# design.net
KiCad netlist of a schematic drawn in EasyEDA Pro
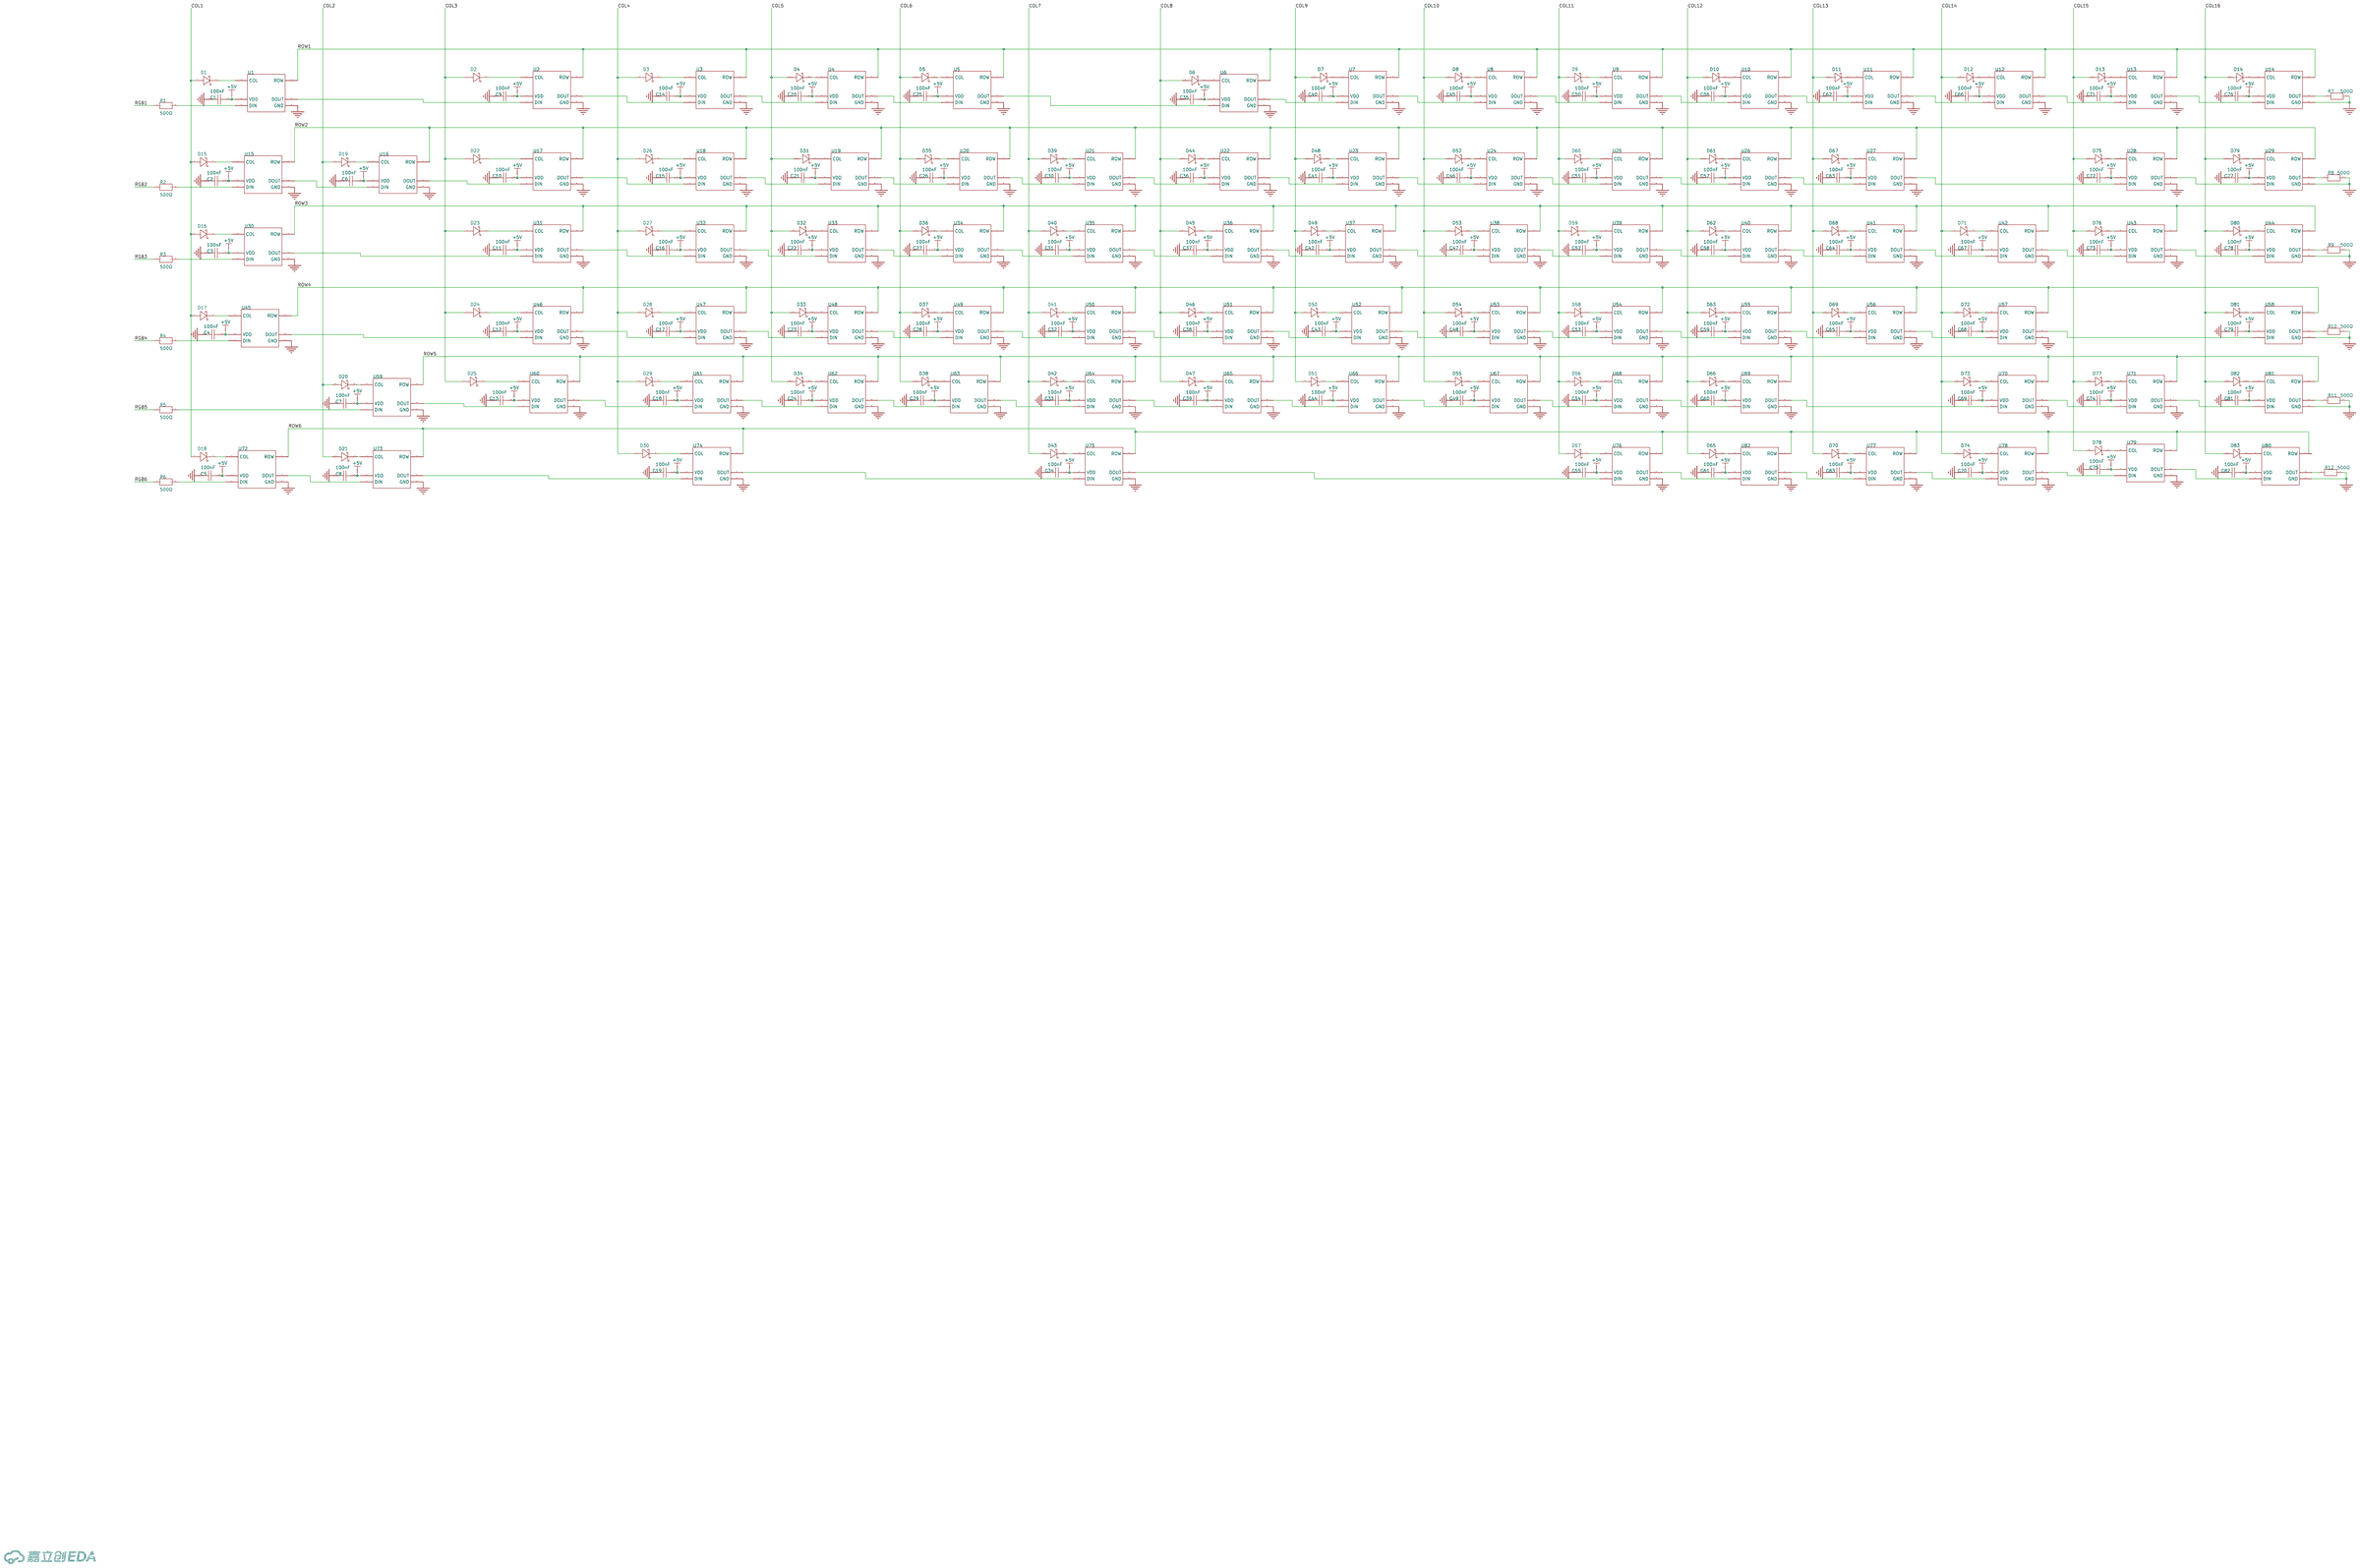
[diagram p0: 键盘按键]
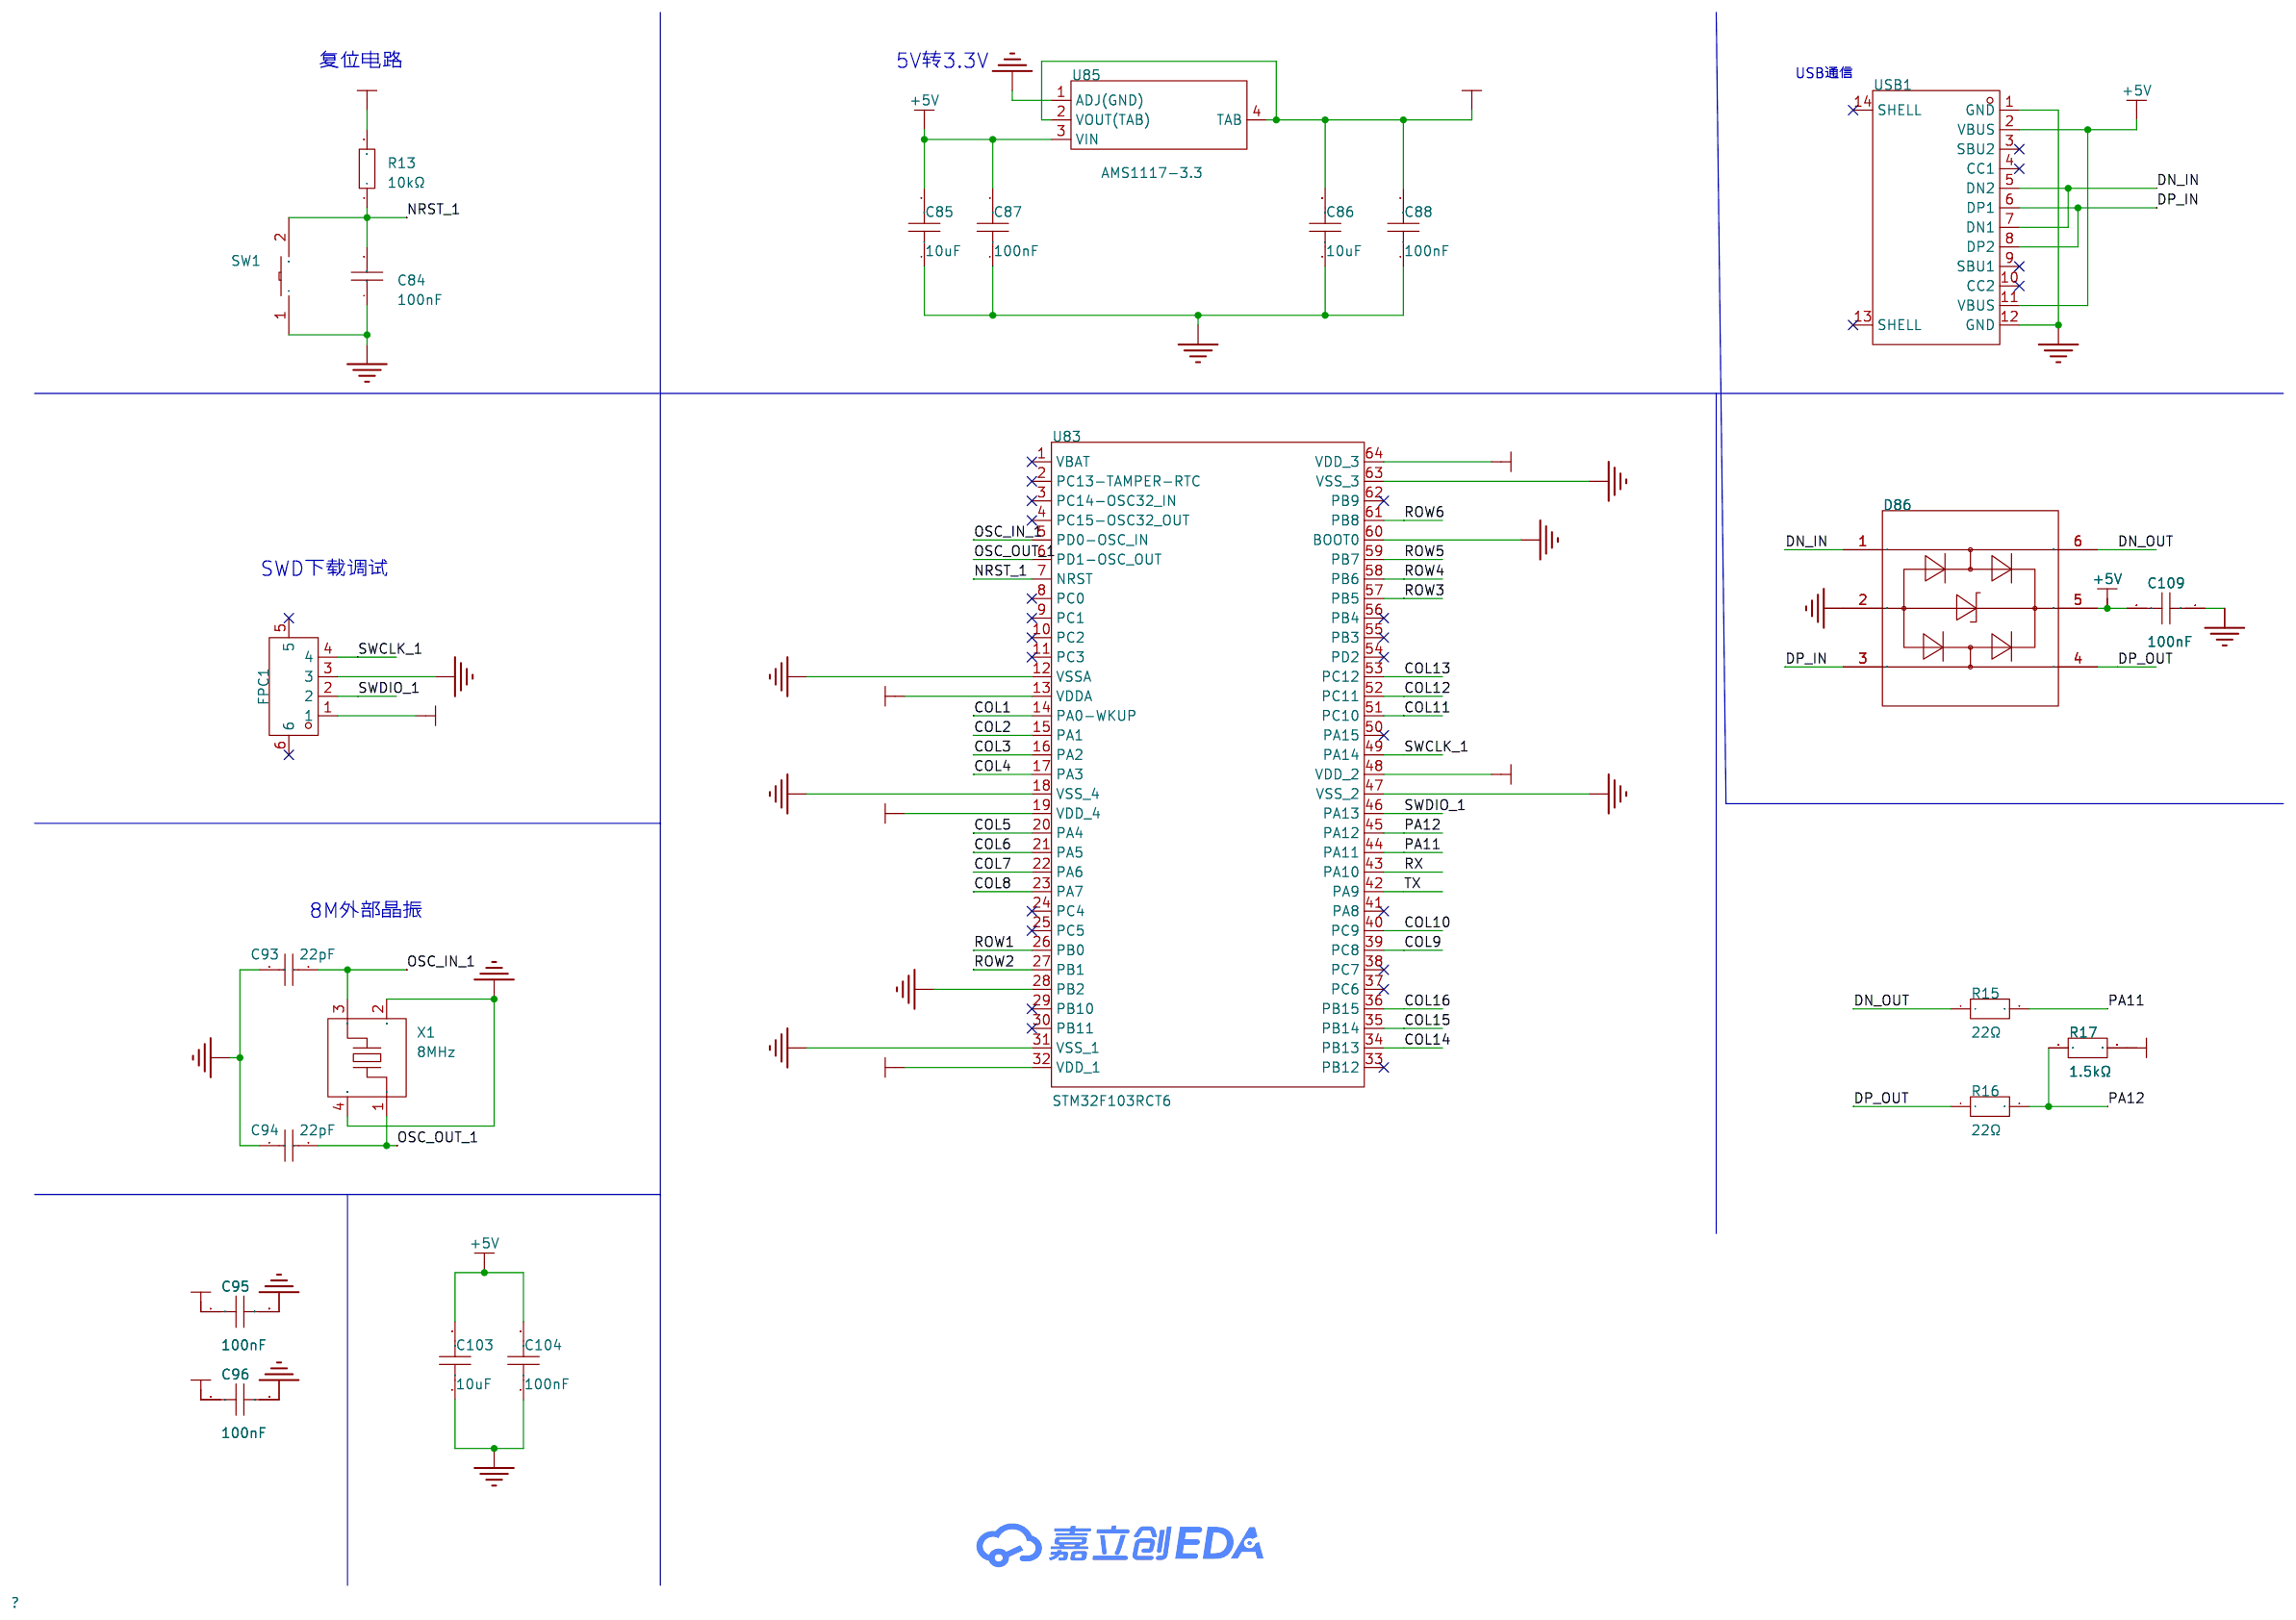
[diagram p1: 键盘主控]
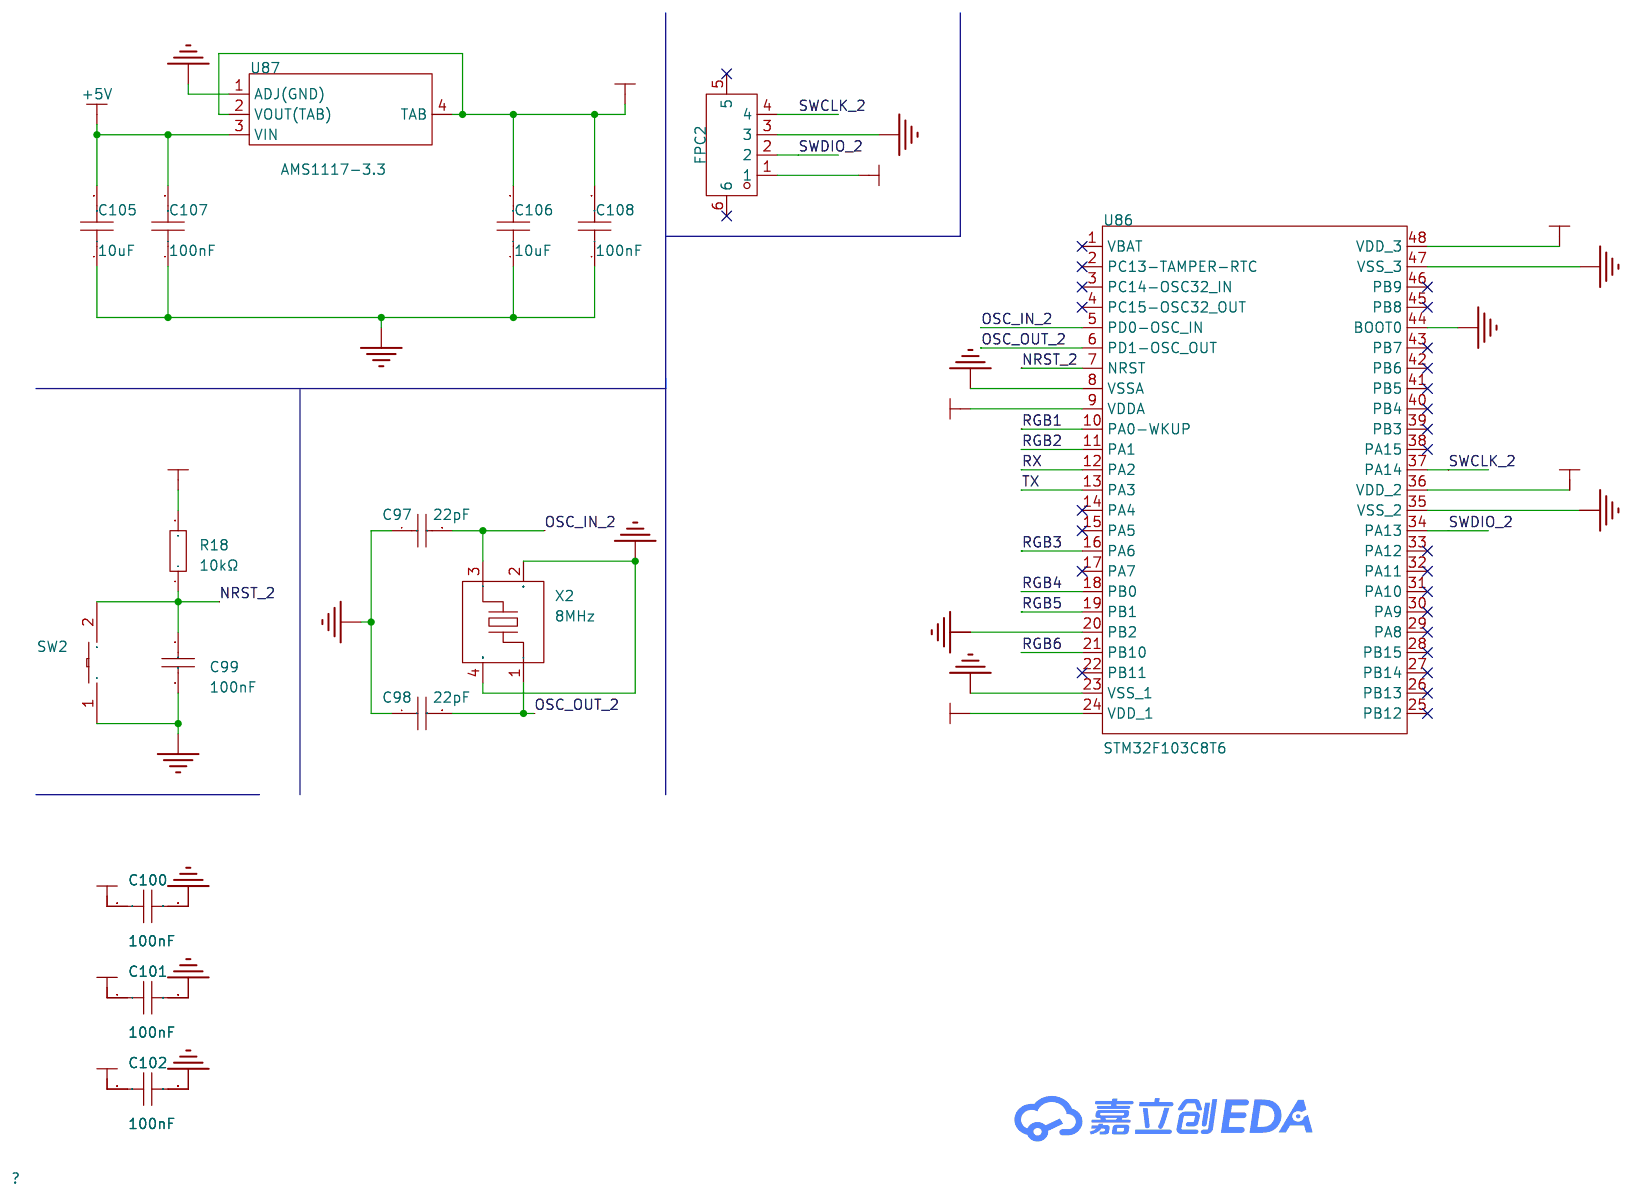
[diagram p2: 灯光主控]

(export (version "E")
  (design (tool "Eeschema 10.0.6"))
  (components
    (comp (ref "C1")
      (value "100nF")
      (footprint "easyedapro:C0805")
      (description "容值:100nF;精度:±10%;额定电压:50V;温度系数:X7R;")
      (fields
        (field (name "Manufacturer Part") "CC0805KRX7R9BB104")
        (field (name "Manufacturer") "YAGEO(国巨)")
      )
      (libsource (lib "easyedapro") (part "CC0805KRX7R9BB104"))
    )
    (comp (ref "C2")
      (value "100nF")
      (footprint "easyedapro:C0805")
      (description "容值:100nF;精度:±10%;额定电压:50V;温度系数:X7R;")
      (fields
        (field (name "Manufacturer Part") "CC0805KRX7R9BB104")
        (field (name "Manufacturer") "YAGEO(国巨)")
      )
      (libsource (lib "easyedapro") (part "CC0805KRX7R9BB104"))
    )
    (comp (ref "C3")
      (value "100nF")
      (footprint "easyedapro:C0805")
      (description "容值:100nF;精度:±10%;额定电压:50V;温度系数:X7R;")
      (fields
        (field (name "Manufacturer Part") "CC0805KRX7R9BB104")
        (field (name "Manufacturer") "YAGEO(国巨)")
      )
      (libsource (lib "easyedapro") (part "CC0805KRX7R9BB104"))
    )
    (comp (ref "C4")
      (value "100nF")
      (footprint "easyedapro:C0805")
      (description "容值:100nF;精度:±10%;额定电压:50V;温度系数:X7R;")
      (fields
        (field (name "Manufacturer Part") "CC0805KRX7R9BB104")
        (field (name "Manufacturer") "YAGEO(国巨)")
      )
      (libsource (lib "easyedapro") (part "CC0805KRX7R9BB104"))
    )
    (comp (ref "C5")
      (value "100nF")
      (footprint "easyedapro:C0805")
      (description "容值:100nF;精度:±10%;额定电压:50V;温度系数:X7R;")
      (fields
        (field (name "Manufacturer Part") "CC0805KRX7R9BB104")
        (field (name "Manufacturer") "YAGEO(国巨)")
      )
      (libsource (lib "easyedapro") (part "CC0805KRX7R9BB104"))
    )
    (comp (ref "C6")
      (value "100nF")
      (footprint "easyedapro:C0805")
      (description "容值:100nF;精度:±10%;额定电压:50V;温度系数:X7R;")
      (fields
        (field (name "Manufacturer Part") "CC0805KRX7R9BB104")
        (field (name "Manufacturer") "YAGEO(国巨)")
      )
      (libsource (lib "easyedapro") (part "CC0805KRX7R9BB104"))
    )
    (comp (ref "C7")
      (value "100nF")
      (footprint "easyedapro:C0805")
      (description "容值:100nF;精度:±10%;额定电压:50V;温度系数:X7R;")
      (fields
        (field (name "Manufacturer Part") "CC0805KRX7R9BB104")
        (field (name "Manufacturer") "YAGEO(国巨)")
      )
      (libsource (lib "easyedapro") (part "CC0805KRX7R9BB104"))
    )
    (comp (ref "C8")
      (value "100nF")
      (footprint "easyedapro:C0805")
      (description "容值:100nF;精度:±10%;额定电压:50V;温度系数:X7R;")
      (fields
        (field (name "Manufacturer Part") "CC0805KRX7R9BB104")
        (field (name "Manufacturer") "YAGEO(国巨)")
      )
      (libsource (lib "easyedapro") (part "CC0805KRX7R9BB104"))
    )
    (comp (ref "C9")
      (value "100nF")
      (footprint "easyedapro:C0805")
      (description "容值:100nF;精度:±10%;额定电压:50V;温度系数:X7R;")
      (fields
        (field (name "Manufacturer Part") "CC0805KRX7R9BB104")
        (field (name "Manufacturer") "YAGEO(国巨)")
      )
      (libsource (lib "easyedapro") (part "CC0805KRX7R9BB104"))
    )
    (comp (ref "C10")
      (value "100nF")
      (footprint "easyedapro:C0805")
      (description "容值:100nF;精度:±10%;额定电压:50V;温度系数:X7R;")
      (fields
        (field (name "Manufacturer Part") "CC0805KRX7R9BB104")
        (field (name "Manufacturer") "YAGEO(国巨)")
      )
      (libsource (lib "easyedapro") (part "CC0805KRX7R9BB104"))
    )
    (comp (ref "C11")
      (value "100nF")
      (footprint "easyedapro:C0805")
      (description "容值:100nF;精度:±10%;额定电压:50V;温度系数:X7R;")
      (fields
        (field (name "Manufacturer Part") "CC0805KRX7R9BB104")
        (field (name "Manufacturer") "YAGEO(国巨)")
      )
      (libsource (lib "easyedapro") (part "CC0805KRX7R9BB104"))
    )
    (comp (ref "C12")
      (value "100nF")
      (footprint "easyedapro:C0805")
      (description "容值:100nF;精度:±10%;额定电压:50V;温度系数:X7R;")
      (fields
        (field (name "Manufacturer Part") "CC0805KRX7R9BB104")
        (field (name "Manufacturer") "YAGEO(国巨)")
      )
      (libsource (lib "easyedapro") (part "CC0805KRX7R9BB104"))
    )
    (comp (ref "C13")
      (value "100nF")
      (footprint "easyedapro:C0805")
      (description "容值:100nF;精度:±10%;额定电压:50V;温度系数:X7R;")
      (fields
        (field (name "Manufacturer Part") "CC0805KRX7R9BB104")
        (field (name "Manufacturer") "YAGEO(国巨)")
      )
      (libsource (lib "easyedapro") (part "CC0805KRX7R9BB104"))
    )
    (comp (ref "C14")
      (value "100nF")
      (footprint "easyedapro:C0805")
      (description "容值:100nF;精度:±10%;额定电压:50V;温度系数:X7R;")
      (fields
        (field (name "Manufacturer Part") "CC0805KRX7R9BB104")
        (field (name "Manufacturer") "YAGEO(国巨)")
      )
      (libsource (lib "easyedapro") (part "CC0805KRX7R9BB104"))
    )
    (comp (ref "C15")
      (value "100nF")
      (footprint "easyedapro:C0805")
      (description "容值:100nF;精度:±10%;额定电压:50V;温度系数:X7R;")
      (fields
        (field (name "Manufacturer Part") "CC0805KRX7R9BB104")
        (field (name "Manufacturer") "YAGEO(国巨)")
      )
      (libsource (lib "easyedapro") (part "CC0805KRX7R9BB104"))
    )
    (comp (ref "C16")
      (value "100nF")
      (footprint "easyedapro:C0805")
      (description "容值:100nF;精度:±10%;额定电压:50V;温度系数:X7R;")
      (fields
        (field (name "Manufacturer Part") "CC0805KRX7R9BB104")
        (field (name "Manufacturer") "YAGEO(国巨)")
      )
      (libsource (lib "easyedapro") (part "CC0805KRX7R9BB104"))
    )
    (comp (ref "C17")
      (value "100nF")
      (footprint "easyedapro:C0805")
      (description "容值:100nF;精度:±10%;额定电压:50V;温度系数:X7R;")
      (fields
        (field (name "Manufacturer Part") "CC0805KRX7R9BB104")
        (field (name "Manufacturer") "YAGEO(国巨)")
      )
      (libsource (lib "easyedapro") (part "CC0805KRX7R9BB104"))
    )
    (comp (ref "C18")
      (value "100nF")
      (footprint "easyedapro:C0805")
      (description "容值:100nF;精度:±10%;额定电压:50V;温度系数:X7R;")
      (fields
        (field (name "Manufacturer Part") "CC0805KRX7R9BB104")
        (field (name "Manufacturer") "YAGEO(国巨)")
      )
      (libsource (lib "easyedapro") (part "CC0805KRX7R9BB104"))
    )
    (comp (ref "C19")
      (value "100nF")
      (footprint "easyedapro:C0805")
      (description "容值:100nF;精度:±10%;额定电压:50V;温度系数:X7R;")
      (fields
        (field (name "Manufacturer Part") "CC0805KRX7R9BB104")
        (field (name "Manufacturer") "YAGEO(国巨)")
      )
      (libsource (lib "easyedapro") (part "CC0805KRX7R9BB104"))
    )
    (comp (ref "C20")
      (value "100nF")
      (footprint "easyedapro:C0805")
      (description "容值:100nF;精度:±10%;额定电压:50V;温度系数:X7R;")
      (fields
        (field (name "Manufacturer Part") "CC0805KRX7R9BB104")
        (field (name "Manufacturer") "YAGEO(国巨)")
      )
      (libsource (lib "easyedapro") (part "CC0805KRX7R9BB104"))
    )
    (comp (ref "C21")
      (value "100nF")
      (footprint "easyedapro:C0805")
      (description "容值:100nF;精度:±10%;额定电压:50V;温度系数:X7R;")
      (fields
        (field (name "Manufacturer Part") "CC0805KRX7R9BB104")
        (field (name "Manufacturer") "YAGEO(国巨)")
      )
      (libsource (lib "easyedapro") (part "CC0805KRX7R9BB104"))
    )
    (comp (ref "C22")
      (value "100nF")
      (footprint "easyedapro:C0805")
      (description "容值:100nF;精度:±10%;额定电压:50V;温度系数:X7R;")
      (fields
        (field (name "Manufacturer Part") "CC0805KRX7R9BB104")
        (field (name "Manufacturer") "YAGEO(国巨)")
      )
      (libsource (lib "easyedapro") (part "CC0805KRX7R9BB104"))
    )
    (comp (ref "C23")
      (value "100nF")
      (footprint "easyedapro:C0805")
      (description "容值:100nF;精度:±10%;额定电压:50V;温度系数:X7R;")
      (fields
        (field (name "Manufacturer Part") "CC0805KRX7R9BB104")
        (field (name "Manufacturer") "YAGEO(国巨)")
      )
      (libsource (lib "easyedapro") (part "CC0805KRX7R9BB104"))
    )
    (comp (ref "C24")
      (value "100nF")
      (footprint "easyedapro:C0805")
      (description "容值:100nF;精度:±10%;额定电压:50V;温度系数:X7R;")
      (fields
        (field (name "Manufacturer Part") "CC0805KRX7R9BB104")
        (field (name "Manufacturer") "YAGEO(国巨)")
      )
      (libsource (lib "easyedapro") (part "CC0805KRX7R9BB104"))
    )
    (comp (ref "C25")
      (value "100nF")
      (footprint "easyedapro:C0805")
      (description "容值:100nF;精度:±10%;额定电压:50V;温度系数:X7R;")
      (fields
        (field (name "Manufacturer Part") "CC0805KRX7R9BB104")
        (field (name "Manufacturer") "YAGEO(国巨)")
      )
      (libsource (lib "easyedapro") (part "CC0805KRX7R9BB104"))
    )
    (comp (ref "C26")
      (value "100nF")
      (footprint "easyedapro:C0805")
      (description "容值:100nF;精度:±10%;额定电压:50V;温度系数:X7R;")
      (fields
        (field (name "Manufacturer Part") "CC0805KRX7R9BB104")
        (field (name "Manufacturer") "YAGEO(国巨)")
      )
      (libsource (lib "easyedapro") (part "CC0805KRX7R9BB104"))
    )
    (comp (ref "C27")
      (value "100nF")
      (footprint "easyedapro:C0805")
      (description "容值:100nF;精度:±10%;额定电压:50V;温度系数:X7R;")
      (fields
        (field (name "Manufacturer Part") "CC0805KRX7R9BB104")
        (field (name "Manufacturer") "YAGEO(国巨)")
      )
      (libsource (lib "easyedapro") (part "CC0805KRX7R9BB104"))
    )
    (comp (ref "C28")
      (value "100nF")
      (footprint "easyedapro:C0805")
      (description "容值:100nF;精度:±10%;额定电压:50V;温度系数:X7R;")
      (fields
        (field (name "Manufacturer Part") "CC0805KRX7R9BB104")
        (field (name "Manufacturer") "YAGEO(国巨)")
      )
      (libsource (lib "easyedapro") (part "CC0805KRX7R9BB104"))
    )
    (comp (ref "C29")
      (value "100nF")
      (footprint "easyedapro:C0805")
      (description "容值:100nF;精度:±10%;额定电压:50V;温度系数:X7R;")
      (fields
        (field (name "Manufacturer Part") "CC0805KRX7R9BB104")
        (field (name "Manufacturer") "YAGEO(国巨)")
      )
      (libsource (lib "easyedapro") (part "CC0805KRX7R9BB104"))
    )
    (comp (ref "C30")
      (value "100nF")
      (footprint "easyedapro:C0805")
      (description "容值:100nF;精度:±10%;额定电压:50V;温度系数:X7R;")
      (fields
        (field (name "Manufacturer Part") "CC0805KRX7R9BB104")
        (field (name "Manufacturer") "YAGEO(国巨)")
      )
      (libsource (lib "easyedapro") (part "CC0805KRX7R9BB104"))
    )
    (comp (ref "C31")
      (value "100nF")
      (footprint "easyedapro:C0805")
      (description "容值:100nF;精度:±10%;额定电压:50V;温度系数:X7R;")
      (fields
        (field (name "Manufacturer Part") "CC0805KRX7R9BB104")
        (field (name "Manufacturer") "YAGEO(国巨)")
      )
      (libsource (lib "easyedapro") (part "CC0805KRX7R9BB104"))
    )
    (comp (ref "C32")
      (value "100nF")
      (footprint "easyedapro:C0805")
      (description "容值:100nF;精度:±10%;额定电压:50V;温度系数:X7R;")
      (fields
        (field (name "Manufacturer Part") "CC0805KRX7R9BB104")
        (field (name "Manufacturer") "YAGEO(国巨)")
      )
      (libsource (lib "easyedapro") (part "CC0805KRX7R9BB104"))
    )
    (comp (ref "C33")
      (value "100nF")
      (footprint "easyedapro:C0805")
      (description "容值:100nF;精度:±10%;额定电压:50V;温度系数:X7R;")
      (fields
        (field (name "Manufacturer Part") "CC0805KRX7R9BB104")
        (field (name "Manufacturer") "YAGEO(国巨)")
      )
      (libsource (lib "easyedapro") (part "CC0805KRX7R9BB104"))
    )
    (comp (ref "C34")
      (value "100nF")
      (footprint "easyedapro:C0805")
      (description "容值:100nF;精度:±10%;额定电压:50V;温度系数:X7R;")
      (fields
        (field (name "Manufacturer Part") "CC0805KRX7R9BB104")
        (field (name "Manufacturer") "YAGEO(国巨)")
      )
      (libsource (lib "easyedapro") (part "CC0805KRX7R9BB104"))
    )
    (comp (ref "C35")
      (value "100nF")
      (footprint "easyedapro:C0805")
      (description "容值:100nF;精度:±10%;额定电压:50V;温度系数:X7R;")
      (fields
        (field (name "Manufacturer Part") "CC0805KRX7R9BB104")
        (field (name "Manufacturer") "YAGEO(国巨)")
      )
      (libsource (lib "easyedapro") (part "CC0805KRX7R9BB104"))
    )
    (comp (ref "C36")
      (value "100nF")
      (footprint "easyedapro:C0805")
      (description "容值:100nF;精度:±10%;额定电压:50V;温度系数:X7R;")
      (fields
        (field (name "Manufacturer Part") "CC0805KRX7R9BB104")
        (field (name "Manufacturer") "YAGEO(国巨)")
      )
      (libsource (lib "easyedapro") (part "CC0805KRX7R9BB104"))
    )
    (comp (ref "C37")
      (value "100nF")
      (footprint "easyedapro:C0805")
      (description "容值:100nF;精度:±10%;额定电压:50V;温度系数:X7R;")
      (fields
        (field (name "Manufacturer Part") "CC0805KRX7R9BB104")
        (field (name "Manufacturer") "YAGEO(国巨)")
      )
      (libsource (lib "easyedapro") (part "CC0805KRX7R9BB104"))
    )
    (comp (ref "C38")
      (value "100nF")
      (footprint "easyedapro:C0805")
      (description "容值:100nF;精度:±10%;额定电压:50V;温度系数:X7R;")
      (fields
        (field (name "Manufacturer Part") "CC0805KRX7R9BB104")
        (field (name "Manufacturer") "YAGEO(国巨)")
      )
      (libsource (lib "easyedapro") (part "CC0805KRX7R9BB104"))
    )
    (comp (ref "C39")
      (value "100nF")
      (footprint "easyedapro:C0805")
      (description "容值:100nF;精度:±10%;额定电压:50V;温度系数:X7R;")
      (fields
        (field (name "Manufacturer Part") "CC0805KRX7R9BB104")
        (field (name "Manufacturer") "YAGEO(国巨)")
      )
      (libsource (lib "easyedapro") (part "CC0805KRX7R9BB104"))
    )
    (comp (ref "C40")
      (value "100nF")
      (footprint "easyedapro:C0805")
      (description "容值:100nF;精度:±10%;额定电压:50V;温度系数:X7R;")
      (fields
        (field (name "Manufacturer Part") "CC0805KRX7R9BB104")
        (field (name "Manufacturer") "YAGEO(国巨)")
      )
      (libsource (lib "easyedapro") (part "CC0805KRX7R9BB104"))
    )
    (comp (ref "C41")
      (value "100nF")
      (footprint "easyedapro:C0805")
      (description "容值:100nF;精度:±10%;额定电压:50V;温度系数:X7R;")
      (fields
        (field (name "Manufacturer Part") "CC0805KRX7R9BB104")
        (field (name "Manufacturer") "YAGEO(国巨)")
      )
      (libsource (lib "easyedapro") (part "CC0805KRX7R9BB104"))
    )
    (comp (ref "C42")
      (value "100nF")
      (footprint "easyedapro:C0805")
      (description "容值:100nF;精度:±10%;额定电压:50V;温度系数:X7R;")
      (fields
        (field (name "Manufacturer Part") "CC0805KRX7R9BB104")
        (field (name "Manufacturer") "YAGEO(国巨)")
      )
      (libsource (lib "easyedapro") (part "CC0805KRX7R9BB104"))
    )
    (comp (ref "C43")
      (value "100nF")
      (footprint "easyedapro:C0805")
      (description "容值:100nF;精度:±10%;额定电压:50V;温度系数:X7R;")
      (fields
        (field (name "Manufacturer Part") "CC0805KRX7R9BB104")
        (field (name "Manufacturer") "YAGEO(国巨)")
      )
      (libsource (lib "easyedapro") (part "CC0805KRX7R9BB104"))
    )
    (comp (ref "C44")
      (value "100nF")
      (footprint "easyedapro:C0805")
      (description "容值:100nF;精度:±10%;额定电压:50V;温度系数:X7R;")
      (fields
        (field (name "Manufacturer Part") "CC0805KRX7R9BB104")
        (field (name "Manufacturer") "YAGEO(国巨)")
      )
      (libsource (lib "easyedapro") (part "CC0805KRX7R9BB104"))
    )
    (comp (ref "C45")
      (value "100nF")
      (footprint "easyedapro:C0805")
      (description "容值:100nF;精度:±10%;额定电压:50V;温度系数:X7R;")
      (fields
        (field (name "Manufacturer Part") "CC0805KRX7R9BB104")
        (field (name "Manufacturer") "YAGEO(国巨)")
      )
      (libsource (lib "easyedapro") (part "CC0805KRX7R9BB104"))
    )
    (comp (ref "C46")
      (value "100nF")
      (footprint "easyedapro:C0805")
      (description "容值:100nF;精度:±10%;额定电压:50V;温度系数:X7R;")
      (fields
        (field (name "Manufacturer Part") "CC0805KRX7R9BB104")
        (field (name "Manufacturer") "YAGEO(国巨)")
      )
      (libsource (lib "easyedapro") (part "CC0805KRX7R9BB104"))
    )
    (comp (ref "C47")
      (value "100nF")
      (footprint "easyedapro:C0805")
      (description "容值:100nF;精度:±10%;额定电压:50V;温度系数:X7R;")
      (fields
        (field (name "Manufacturer Part") "CC0805KRX7R9BB104")
        (field (name "Manufacturer") "YAGEO(国巨)")
      )
      (libsource (lib "easyedapro") (part "CC0805KRX7R9BB104"))
    )
    (comp (ref "C48")
      (value "100nF")
      (footprint "easyedapro:C0805")
      (description "容值:100nF;精度:±10%;额定电压:50V;温度系数:X7R;")
      (fields
        (field (name "Manufacturer Part") "CC0805KRX7R9BB104")
        (field (name "Manufacturer") "YAGEO(国巨)")
      )
      (libsource (lib "easyedapro") (part "CC0805KRX7R9BB104"))
    )
    (comp (ref "C49")
      (value "100nF")
      (footprint "easyedapro:C0805")
      (description "容值:100nF;精度:±10%;额定电压:50V;温度系数:X7R;")
      (fields
        (field (name "Manufacturer Part") "CC0805KRX7R9BB104")
        (field (name "Manufacturer") "YAGEO(国巨)")
      )
      (libsource (lib "easyedapro") (part "CC0805KRX7R9BB104"))
    )
    (comp (ref "C50")
      (value "100nF")
      (footprint "easyedapro:C0805")
      (description "容值:100nF;精度:±10%;额定电压:50V;温度系数:X7R;")
      (fields
        (field (name "Manufacturer Part") "CC0805KRX7R9BB104")
        (field (name "Manufacturer") "YAGEO(国巨)")
      )
      (libsource (lib "easyedapro") (part "CC0805KRX7R9BB104"))
    )
    (comp (ref "C51")
      (value "100nF")
      (footprint "easyedapro:C0805")
      (description "容值:100nF;精度:±10%;额定电压:50V;温度系数:X7R;")
      (fields
        (field (name "Manufacturer Part") "CC0805KRX7R9BB104")
        (field (name "Manufacturer") "YAGEO(国巨)")
      )
      (libsource (lib "easyedapro") (part "CC0805KRX7R9BB104"))
    )
    (comp (ref "C52")
      (value "100nF")
      (footprint "easyedapro:C0805")
      (description "容值:100nF;精度:±10%;额定电压:50V;温度系数:X7R;")
      (fields
        (field (name "Manufacturer Part") "CC0805KRX7R9BB104")
        (field (name "Manufacturer") "YAGEO(国巨)")
      )
      (libsource (lib "easyedapro") (part "CC0805KRX7R9BB104"))
    )
    (comp (ref "C53")
      (value "100nF")
      (footprint "easyedapro:C0805")
      (description "容值:100nF;精度:±10%;额定电压:50V;温度系数:X7R;")
      (fields
        (field (name "Manufacturer Part") "CC0805KRX7R9BB104")
        (field (name "Manufacturer") "YAGEO(国巨)")
      )
      (libsource (lib "easyedapro") (part "CC0805KRX7R9BB104"))
    )
    (comp (ref "C54")
      (value "100nF")
      (footprint "easyedapro:C0805")
      (description "容值:100nF;精度:±10%;额定电压:50V;温度系数:X7R;")
      (fields
        (field (name "Manufacturer Part") "CC0805KRX7R9BB104")
        (field (name "Manufacturer") "YAGEO(国巨)")
      )
      (libsource (lib "easyedapro") (part "CC0805KRX7R9BB104"))
    )
    (comp (ref "C55")
      (value "100nF")
      (footprint "easyedapro:C0805")
      (description "容值:100nF;精度:±10%;额定电压:50V;温度系数:X7R;")
      (fields
        (field (name "Manufacturer Part") "CC0805KRX7R9BB104")
        (field (name "Manufacturer") "YAGEO(国巨)")
      )
      (libsource (lib "easyedapro") (part "CC0805KRX7R9BB104"))
    )
    (comp (ref "C56")
      (value "100nF")
      (footprint "easyedapro:C0805")
      (description "容值:100nF;精度:±10%;额定电压:50V;温度系数:X7R;")
      (fields
        (field (name "Manufacturer Part") "CC0805KRX7R9BB104")
        (field (name "Manufacturer") "YAGEO(国巨)")
      )
      (libsource (lib "easyedapro") (part "CC0805KRX7R9BB104"))
    )
    (comp (ref "C57")
      (value "100nF")
      (footprint "easyedapro:C0805")
      (description "容值:100nF;精度:±10%;额定电压:50V;温度系数:X7R;")
      (fields
        (field (name "Manufacturer Part") "CC0805KRX7R9BB104")
        (field (name "Manufacturer") "YAGEO(国巨)")
      )
      (libsource (lib "easyedapro") (part "CC0805KRX7R9BB104"))
    )
    (comp (ref "C58")
      (value "100nF")
      (footprint "easyedapro:C0805")
      (description "容值:100nF;精度:±10%;额定电压:50V;温度系数:X7R;")
      (fields
        (field (name "Manufacturer Part") "CC0805KRX7R9BB104")
        (field (name "Manufacturer") "YAGEO(国巨)")
      )
      (libsource (lib "easyedapro") (part "CC0805KRX7R9BB104"))
    )
    (comp (ref "C59")
      (value "100nF")
      (footprint "easyedapro:C0805")
      (description "容值:100nF;精度:±10%;额定电压:50V;温度系数:X7R;")
      (fields
        (field (name "Manufacturer Part") "CC0805KRX7R9BB104")
        (field (name "Manufacturer") "YAGEO(国巨)")
      )
      (libsource (lib "easyedapro") (part "CC0805KRX7R9BB104"))
    )
    (comp (ref "C60")
      (value "100nF")
      (footprint "easyedapro:C0805")
      (description "容值:100nF;精度:±10%;额定电压:50V;温度系数:X7R;")
      (fields
        (field (name "Manufacturer Part") "CC0805KRX7R9BB104")
        (field (name "Manufacturer") "YAGEO(国巨)")
      )
      (libsource (lib "easyedapro") (part "CC0805KRX7R9BB104"))
    )
    (comp (ref "C61")
      (value "100nF")
      (footprint "easyedapro:C0805")
      (description "容值:100nF;精度:±10%;额定电压:50V;温度系数:X7R;")
      (fields
        (field (name "Manufacturer Part") "CC0805KRX7R9BB104")
        (field (name "Manufacturer") "YAGEO(国巨)")
      )
      (libsource (lib "easyedapro") (part "CC0805KRX7R9BB104"))
    )
    (comp (ref "C62")
      (value "100nF")
      (footprint "easyedapro:C0805")
      (description "容值:100nF;精度:±10%;额定电压:50V;温度系数:X7R;")
      (fields
        (field (name "Manufacturer Part") "CC0805KRX7R9BB104")
        (field (name "Manufacturer") "YAGEO(国巨)")
      )
      (libsource (lib "easyedapro") (part "CC0805KRX7R9BB104"))
    )
    (comp (ref "C63")
      (value "100nF")
      (footprint "easyedapro:C0805")
      (description "容值:100nF;精度:±10%;额定电压:50V;温度系数:X7R;")
      (fields
        (field (name "Manufacturer Part") "CC0805KRX7R9BB104")
        (field (name "Manufacturer") "YAGEO(国巨)")
      )
      (libsource (lib "easyedapro") (part "CC0805KRX7R9BB104"))
    )
    (comp (ref "C64")
      (value "100nF")
      (footprint "easyedapro:C0805")
      (description "容值:100nF;精度:±10%;额定电压:50V;温度系数:X7R;")
      (fields
        (field (name "Manufacturer Part") "CC0805KRX7R9BB104")
        (field (name "Manufacturer") "YAGEO(国巨)")
      )
      (libsource (lib "easyedapro") (part "CC0805KRX7R9BB104"))
    )
    (comp (ref "C65")
      (value "100nF")
      (footprint "easyedapro:C0805")
      (description "容值:100nF;精度:±10%;额定电压:50V;温度系数:X7R;")
      (fields
        (field (name "Manufacturer Part") "CC0805KRX7R9BB104")
        (field (name "Manufacturer") "YAGEO(国巨)")
      )
      (libsource (lib "easyedapro") (part "CC0805KRX7R9BB104"))
    )
    (comp (ref "C66")
      (value "100nF")
      (footprint "easyedapro:C0805")
      (description "容值:100nF;精度:±10%;额定电压:50V;温度系数:X7R;")
      (fields
        (field (name "Manufacturer Part") "CC0805KRX7R9BB104")
        (field (name "Manufacturer") "YAGEO(国巨)")
      )
      (libsource (lib "easyedapro") (part "CC0805KRX7R9BB104"))
    )
    (comp (ref "C67")
      (value "100nF")
      (footprint "easyedapro:C0805")
      (description "容值:100nF;精度:±10%;额定电压:50V;温度系数:X7R;")
      (fields
        (field (name "Manufacturer Part") "CC0805KRX7R9BB104")
        (field (name "Manufacturer") "YAGEO(国巨)")
      )
      (libsource (lib "easyedapro") (part "CC0805KRX7R9BB104"))
    )
    (comp (ref "C68")
      (value "100nF")
      (footprint "easyedapro:C0805")
      (description "容值:100nF;精度:±10%;额定电压:50V;温度系数:X7R;")
      (fields
        (field (name "Manufacturer Part") "CC0805KRX7R9BB104")
        (field (name "Manufacturer") "YAGEO(国巨)")
      )
      (libsource (lib "easyedapro") (part "CC0805KRX7R9BB104"))
    )
    (comp (ref "C69")
      (value "100nF")
      (footprint "easyedapro:C0805")
      (description "容值:100nF;精度:±10%;额定电压:50V;温度系数:X7R;")
      (fields
        (field (name "Manufacturer Part") "CC0805KRX7R9BB104")
        (field (name "Manufacturer") "YAGEO(国巨)")
      )
      (libsource (lib "easyedapro") (part "CC0805KRX7R9BB104"))
    )
    (comp (ref "C70")
      (value "100nF")
      (footprint "easyedapro:C0805")
      (description "容值:100nF;精度:±10%;额定电压:50V;温度系数:X7R;")
      (fields
        (field (name "Manufacturer Part") "CC0805KRX7R9BB104")
        (field (name "Manufacturer") "YAGEO(国巨)")
      )
      (libsource (lib "easyedapro") (part "CC0805KRX7R9BB104"))
    )
    (comp (ref "C71")
      (value "100nF")
      (footprint "easyedapro:C0805")
      (description "容值:100nF;精度:±10%;额定电压:50V;温度系数:X7R;")
      (fields
        (field (name "Manufacturer Part") "CC0805KRX7R9BB104")
        (field (name "Manufacturer") "YAGEO(国巨)")
      )
      (libsource (lib "easyedapro") (part "CC0805KRX7R9BB104"))
    )
    (comp (ref "C72")
      (value "100nF")
      (footprint "easyedapro:C0805")
      (description "容值:100nF;精度:±10%;额定电压:50V;温度系数:X7R;")
      (fields
        (field (name "Manufacturer Part") "CC0805KRX7R9BB104")
        (field (name "Manufacturer") "YAGEO(国巨)")
      )
      (libsource (lib "easyedapro") (part "CC0805KRX7R9BB104"))
    )
    (comp (ref "C73")
      (value "100nF")
      (footprint "easyedapro:C0805")
      (description "容值:100nF;精度:±10%;额定电压:50V;温度系数:X7R;")
      (fields
        (field (name "Manufacturer Part") "CC0805KRX7R9BB104")
        (field (name "Manufacturer") "YAGEO(国巨)")
      )
      (libsource (lib "easyedapro") (part "CC0805KRX7R9BB104"))
    )
    (comp (ref "C74")
      (value "100nF")
      (footprint "easyedapro:C0805")
      (description "容值:100nF;精度:±10%;额定电压:50V;温度系数:X7R;")
      (fields
        (field (name "Manufacturer Part") "CC0805KRX7R9BB104")
        (field (name "Manufacturer") "YAGEO(国巨)")
      )
      (libsource (lib "easyedapro") (part "CC0805KRX7R9BB104"))
    )
    (comp (ref "C75")
      (value "100nF")
      (footprint "easyedapro:C0805")
      (description "容值:100nF;精度:±10%;额定电压:50V;温度系数:X7R;")
      (fields
        (field (name "Manufacturer Part") "CC0805KRX7R9BB104")
        (field (name "Manufacturer") "YAGEO(国巨)")
      )
      (libsource (lib "easyedapro") (part "CC0805KRX7R9BB104"))
    )
    (comp (ref "C76")
      (value "100nF")
      (footprint "easyedapro:C0805")
      (description "容值:100nF;精度:±10%;额定电压:50V;温度系数:X7R;")
      (fields
        (field (name "Manufacturer Part") "CC0805KRX7R9BB104")
        (field (name "Manufacturer") "YAGEO(国巨)")
      )
      (libsource (lib "easyedapro") (part "CC0805KRX7R9BB104"))
    )
    (comp (ref "C77")
      (value "100nF")
      (footprint "easyedapro:C0805")
      (description "容值:100nF;精度:±10%;额定电压:50V;温度系数:X7R;")
      (fields
        (field (name "Manufacturer Part") "CC0805KRX7R9BB104")
        (field (name "Manufacturer") "YAGEO(国巨)")
      )
      (libsource (lib "easyedapro") (part "CC0805KRX7R9BB104"))
    )
    (comp (ref "C78")
      (value "100nF")
      (footprint "easyedapro:C0805")
      (description "容值:100nF;精度:±10%;额定电压:50V;温度系数:X7R;")
      (fields
        (field (name "Manufacturer Part") "CC0805KRX7R9BB104")
        (field (name "Manufacturer") "YAGEO(国巨)")
      )
      (libsource (lib "easyedapro") (part "CC0805KRX7R9BB104"))
    )
    (comp (ref "C79")
      (value "100nF")
      (footprint "easyedapro:C0805")
      (description "容值:100nF;精度:±10%;额定电压:50V;温度系数:X7R;")
      (fields
        (field (name "Manufacturer Part") "CC0805KRX7R9BB104")
        (field (name "Manufacturer") "YAGEO(国巨)")
      )
      (libsource (lib "easyedapro") (part "CC0805KRX7R9BB104"))
    )
    (comp (ref "C81")
      (value "100nF")
      (footprint "easyedapro:C0805")
      (description "容值:100nF;精度:±10%;额定电压:50V;温度系数:X7R;")
      (fields
        (field (name "Manufacturer Part") "CC0805KRX7R9BB104")
        (field (name "Manufacturer") "YAGEO(国巨)")
      )
      (libsource (lib "easyedapro") (part "CC0805KRX7R9BB104"))
    )
    (comp (ref "C82")
      (value "100nF")
      (footprint "easyedapro:C0805")
      (description "容值:100nF;精度:±10%;额定电压:50V;温度系数:X7R;")
      (fields
        (field (name "Manufacturer Part") "CC0805KRX7R9BB104")
        (field (name "Manufacturer") "YAGEO(国巨)")
      )
      (libsource (lib "easyedapro") (part "CC0805KRX7R9BB104"))
    )
    (comp (ref "C83")
      (value "100nF")
      (footprint "easyedapro:C0805")
      (description "容值:100nF;精度:±10%;额定电压:50V;温度系数:X7R;")
      (fields
        (field (name "Manufacturer Part") "CC0805KRX7R9BB104")
        (field (name "Manufacturer") "YAGEO(国巨)")
      )
      (libsource (lib "easyedapro") (part "CC0805KRX7R9BB104"))
    )
    (comp (ref "D1")
      (value "1N4148W")
      (footprint "easyedapro:SOD-123_L2.7-W1.6-LS3.7-FD")
      (description "二极管配置:独立式;正向压降(Vf):1.25V@150mA;直流反向耐压(Vr):100V;整流电流:150mA;反向恢复时间(Trr):4ns;")
      (fields (field (name "Manufacturer") "R+O(宏嘉诚)"))
      (libsource (lib "easyedapro") (part "1N4148W_C7420318"))
    )
    (comp (ref "D2")
      (value "1N4148W")
      (footprint "easyedapro:SOD-123_L2.7-W1.6-LS3.7-FD")
      (description "二极管配置:独立式;正向压降(Vf):1.25V@150mA;直流反向耐压(Vr):100V;整流电流:150mA;反向恢复时间(Trr):4ns;")
      (fields (field (name "Manufacturer") "R+O(宏嘉诚)"))
      (libsource (lib "easyedapro") (part "1N4148W_C7420318"))
    )
    (comp (ref "D3")
      (value "1N4148W")
      (footprint "easyedapro:SOD-123_L2.7-W1.6-LS3.7-FD")
      (description "二极管配置:独立式;正向压降(Vf):1.25V@150mA;直流反向耐压(Vr):100V;整流电流:150mA;反向恢复时间(Trr):4ns;")
      (fields (field (name "Manufacturer") "R+O(宏嘉诚)"))
      (libsource (lib "easyedapro") (part "1N4148W_C7420318"))
    )
    (comp (ref "D4")
      (value "1N4148W")
      (footprint "easyedapro:SOD-123_L2.7-W1.6-LS3.7-FD")
      (description "二极管配置:独立式;正向压降(Vf):1.25V@150mA;直流反向耐压(Vr):100V;整流电流:150mA;反向恢复时间(Trr):4ns;")
      (fields (field (name "Manufacturer") "R+O(宏嘉诚)"))
      (libsource (lib "easyedapro") (part "1N4148W_C7420318"))
    )
    (comp (ref "D5")
      (value "1N4148W")
      (footprint "easyedapro:SOD-123_L2.7-W1.6-LS3.7-FD")
      (description "二极管配置:独立式;正向压降(Vf):1.25V@150mA;直流反向耐压(Vr):100V;整流电流:150mA;反向恢复时间(Trr):4ns;")
      (fields (field (name "Manufacturer") "R+O(宏嘉诚)"))
      (libsource (lib "easyedapro") (part "1N4148W_C7420318"))
    )
    (comp (ref "D6")
      (value "1N4148W")
      (footprint "easyedapro:SOD-123_L2.7-W1.6-LS3.7-FD")
      (description "二极管配置:独立式;正向压降(Vf):1.25V@150mA;直流反向耐压(Vr):100V;整流电流:150mA;反向恢复时间(Trr):4ns;")
      (fields (field (name "Manufacturer") "R+O(宏嘉诚)"))
      (libsource (lib "easyedapro") (part "1N4148W_C7420318"))
    )
    (comp (ref "D7")
      (value "1N4148W")
      (footprint "easyedapro:SOD-123_L2.7-W1.6-LS3.7-FD")
      (description "二极管配置:独立式;正向压降(Vf):1.25V@150mA;直流反向耐压(Vr):100V;整流电流:150mA;反向恢复时间(Trr):4ns;")
      (fields (field (name "Manufacturer") "R+O(宏嘉诚)"))
      (libsource (lib "easyedapro") (part "1N4148W_C7420318"))
    )
    (comp (ref "D8")
      (value "1N4148W")
      (footprint "easyedapro:SOD-123_L2.7-W1.6-LS3.7-FD")
      (description "二极管配置:独立式;正向压降(Vf):1.25V@150mA;直流反向耐压(Vr):100V;整流电流:150mA;反向恢复时间(Trr):4ns;")
      (fields (field (name "Manufacturer") "R+O(宏嘉诚)"))
      (libsource (lib "easyedapro") (part "1N4148W_C7420318"))
    )
    (comp (ref "D9")
      (value "1N4148W")
      (footprint "easyedapro:SOD-123_L2.7-W1.6-LS3.7-FD")
      (description "二极管配置:独立式;正向压降(Vf):1.25V@150mA;直流反向耐压(Vr):100V;整流电流:150mA;反向恢复时间(Trr):4ns;")
      (fields (field (name "Manufacturer") "R+O(宏嘉诚)"))
      (libsource (lib "easyedapro") (part "1N4148W_C7420318"))
    )
    (comp (ref "D10")
      (value "1N4148W")
      (footprint "easyedapro:SOD-123_L2.7-W1.6-LS3.7-FD")
      (description "二极管配置:独立式;正向压降(Vf):1.25V@150mA;直流反向耐压(Vr):100V;整流电流:150mA;反向恢复时间(Trr):4ns;")
      (fields (field (name "Manufacturer") "R+O(宏嘉诚)"))
      (libsource (lib "easyedapro") (part "1N4148W_C7420318"))
    )
    (comp (ref "D11")
      (value "1N4148W")
      (footprint "easyedapro:SOD-123_L2.7-W1.6-LS3.7-FD")
      (description "二极管配置:独立式;正向压降(Vf):1.25V@150mA;直流反向耐压(Vr):100V;整流电流:150mA;反向恢复时间(Trr):4ns;")
      (fields (field (name "Manufacturer") "R+O(宏嘉诚)"))
      (libsource (lib "easyedapro") (part "1N4148W_C7420318"))
    )
    (comp (ref "D12")
      (value "1N4148W")
      (footprint "easyedapro:SOD-123_L2.7-W1.6-LS3.7-FD")
      (description "二极管配置:独立式;正向压降(Vf):1.25V@150mA;直流反向耐压(Vr):100V;整流电流:150mA;反向恢复时间(Trr):4ns;")
      (fields (field (name "Manufacturer") "R+O(宏嘉诚)"))
      (libsource (lib "easyedapro") (part "1N4148W_C7420318"))
    )
    (comp (ref "D13")
      (value "1N4148W")
      (footprint "easyedapro:SOD-123_L2.7-W1.6-LS3.7-FD")
      (description "二极管配置:独立式;正向压降(Vf):1.25V@150mA;直流反向耐压(Vr):100V;整流电流:150mA;反向恢复时间(Trr):4ns;")
      (fields (field (name "Manufacturer") "R+O(宏嘉诚)"))
      (libsource (lib "easyedapro") (part "1N4148W_C7420318"))
    )
    (comp (ref "D14")
      (value "1N4148W")
      (footprint "easyedapro:SOD-123_L2.7-W1.6-LS3.7-FD")
      (description "二极管配置:独立式;正向压降(Vf):1.25V@150mA;直流反向耐压(Vr):100V;整流电流:150mA;反向恢复时间(Trr):4ns;")
      (fields (field (name "Manufacturer") "R+O(宏嘉诚)"))
      (libsource (lib "easyedapro") (part "1N4148W_C7420318"))
    )
    (comp (ref "D15")
      (value "1N4148W")
      (footprint "easyedapro:SOD-123_L2.7-W1.6-LS3.7-FD")
      (description "二极管配置:独立式;正向压降(Vf):1.25V@150mA;直流反向耐压(Vr):100V;整流电流:150mA;反向恢复时间(Trr):4ns;")
      (fields (field (name "Manufacturer") "R+O(宏嘉诚)"))
      (libsource (lib "easyedapro") (part "1N4148W_C7420318"))
    )
    (comp (ref "D16")
      (value "1N4148W")
      (footprint "easyedapro:SOD-123_L2.7-W1.6-LS3.7-FD")
      (description "二极管配置:独立式;正向压降(Vf):1.25V@150mA;直流反向耐压(Vr):100V;整流电流:150mA;反向恢复时间(Trr):4ns;")
      (fields (field (name "Manufacturer") "R+O(宏嘉诚)"))
      (libsource (lib "easyedapro") (part "1N4148W_C7420318"))
    )
    (comp (ref "D17")
      (value "1N4148W")
      (footprint "easyedapro:SOD-123_L2.7-W1.6-LS3.7-FD")
      (description "二极管配置:独立式;正向压降(Vf):1.25V@150mA;直流反向耐压(Vr):100V;整流电流:150mA;反向恢复时间(Trr):4ns;")
      (fields (field (name "Manufacturer") "R+O(宏嘉诚)"))
      (libsource (lib "easyedapro") (part "1N4148W_C7420318"))
    )
    (comp (ref "D18")
      (value "1N4148W")
      (footprint "easyedapro:SOD-123_L2.7-W1.6-LS3.7-FD")
      (description "二极管配置:独立式;正向压降(Vf):1.25V@150mA;直流反向耐压(Vr):100V;整流电流:150mA;反向恢复时间(Trr):4ns;")
      (fields (field (name "Manufacturer") "R+O(宏嘉诚)"))
      (libsource (lib "easyedapro") (part "1N4148W_C7420318"))
    )
    (comp (ref "D19")
      (value "1N4148W")
      (footprint "easyedapro:SOD-123_L2.7-W1.6-LS3.7-FD")
      (description "二极管配置:独立式;正向压降(Vf):1.25V@150mA;直流反向耐压(Vr):100V;整流电流:150mA;反向恢复时间(Trr):4ns;")
      (fields (field (name "Manufacturer") "R+O(宏嘉诚)"))
      (libsource (lib "easyedapro") (part "1N4148W_C7420318"))
    )
    (comp (ref "D20")
      (value "1N4148W")
      (footprint "easyedapro:SOD-123_L2.7-W1.6-LS3.7-FD")
      (description "二极管配置:独立式;正向压降(Vf):1.25V@150mA;直流反向耐压(Vr):100V;整流电流:150mA;反向恢复时间(Trr):4ns;")
      (fields (field (name "Manufacturer") "R+O(宏嘉诚)"))
      (libsource (lib "easyedapro") (part "1N4148W_C7420318"))
    )
    (comp (ref "D21")
      (value "1N4148W")
      (footprint "easyedapro:SOD-123_L2.7-W1.6-LS3.7-FD")
      (description "二极管配置:独立式;正向压降(Vf):1.25V@150mA;直流反向耐压(Vr):100V;整流电流:150mA;反向恢复时间(Trr):4ns;")
      (fields (field (name "Manufacturer") "R+O(宏嘉诚)"))
      (libsource (lib "easyedapro") (part "1N4148W_C7420318"))
    )
    (comp (ref "D22")
      (value "1N4148W")
      (footprint "easyedapro:SOD-123_L2.7-W1.6-LS3.7-FD")
      (description "二极管配置:独立式;正向压降(Vf):1.25V@150mA;直流反向耐压(Vr):100V;整流电流:150mA;反向恢复时间(Trr):4ns;")
      (fields (field (name "Manufacturer") "R+O(宏嘉诚)"))
      (libsource (lib "easyedapro") (part "1N4148W_C7420318"))
    )
    (comp (ref "D23")
      (value "1N4148W")
      (footprint "easyedapro:SOD-123_L2.7-W1.6-LS3.7-FD")
      (description "二极管配置:独立式;正向压降(Vf):1.25V@150mA;直流反向耐压(Vr):100V;整流电流:150mA;反向恢复时间(Trr):4ns;")
      (fields (field (name "Manufacturer") "R+O(宏嘉诚)"))
      (libsource (lib "easyedapro") (part "1N4148W_C7420318"))
    )
    (comp (ref "D24")
      (value "1N4148W")
      (footprint "easyedapro:SOD-123_L2.7-W1.6-LS3.7-FD")
      (description "二极管配置:独立式;正向压降(Vf):1.25V@150mA;直流反向耐压(Vr):100V;整流电流:150mA;反向恢复时间(Trr):4ns;")
      (fields (field (name "Manufacturer") "R+O(宏嘉诚)"))
      (libsource (lib "easyedapro") (part "1N4148W_C7420318"))
    )
    (comp (ref "D25")
      (value "1N4148W")
      (footprint "easyedapro:SOD-123_L2.7-W1.6-LS3.7-FD")
      (description "二极管配置:独立式;正向压降(Vf):1.25V@150mA;直流反向耐压(Vr):100V;整流电流:150mA;反向恢复时间(Trr):4ns;")
      (fields (field (name "Manufacturer") "R+O(宏嘉诚)"))
      (libsource (lib "easyedapro") (part "1N4148W_C7420318"))
    )
    (comp (ref "D26")
      (value "1N4148W")
      (footprint "easyedapro:SOD-123_L2.7-W1.6-LS3.7-FD")
      (description "二极管配置:独立式;正向压降(Vf):1.25V@150mA;直流反向耐压(Vr):100V;整流电流:150mA;反向恢复时间(Trr):4ns;")
      (fields (field (name "Manufacturer") "R+O(宏嘉诚)"))
      (libsource (lib "easyedapro") (part "1N4148W_C7420318"))
    )
    (comp (ref "D27")
      (value "1N4148W")
      (footprint "easyedapro:SOD-123_L2.7-W1.6-LS3.7-FD")
      (description "二极管配置:独立式;正向压降(Vf):1.25V@150mA;直流反向耐压(Vr):100V;整流电流:150mA;反向恢复时间(Trr):4ns;")
      (fields (field (name "Manufacturer") "R+O(宏嘉诚)"))
      (libsource (lib "easyedapro") (part "1N4148W_C7420318"))
    )
    (comp (ref "D28")
      (value "1N4148W")
      (footprint "easyedapro:SOD-123_L2.7-W1.6-LS3.7-FD")
      (description "二极管配置:独立式;正向压降(Vf):1.25V@150mA;直流反向耐压(Vr):100V;整流电流:150mA;反向恢复时间(Trr):4ns;")
      (fields (field (name "Manufacturer") "R+O(宏嘉诚)"))
      (libsource (lib "easyedapro") (part "1N4148W_C7420318"))
    )
    (comp (ref "D29")
      (value "1N4148W")
      (footprint "easyedapro:SOD-123_L2.7-W1.6-LS3.7-FD")
      (description "二极管配置:独立式;正向压降(Vf):1.25V@150mA;直流反向耐压(Vr):100V;整流电流:150mA;反向恢复时间(Trr):4ns;")
      (fields (field (name "Manufacturer") "R+O(宏嘉诚)"))
      (libsource (lib "easyedapro") (part "1N4148W_C7420318"))
    )
    (comp (ref "D30")
      (value "1N4148W")
      (footprint "easyedapro:SOD-123_L2.7-W1.6-LS3.7-FD")
      (description "二极管配置:独立式;正向压降(Vf):1.25V@150mA;直流反向耐压(Vr):100V;整流电流:150mA;反向恢复时间(Trr):4ns;")
      (fields (field (name "Manufacturer") "R+O(宏嘉诚)"))
      (libsource (lib "easyedapro") (part "1N4148W_C7420318"))
    )
    (comp (ref "D31")
      (value "1N4148W")
      (footprint "easyedapro:SOD-123_L2.7-W1.6-LS3.7-FD")
      (description "二极管配置:独立式;正向压降(Vf):1.25V@150mA;直流反向耐压(Vr):100V;整流电流:150mA;反向恢复时间(Trr):4ns;")
      (fields (field (name "Manufacturer") "R+O(宏嘉诚)"))
      (libsource (lib "easyedapro") (part "1N4148W_C7420318"))
    )
    (comp (ref "D32")
      (value "1N4148W")
      (footprint "easyedapro:SOD-123_L2.7-W1.6-LS3.7-FD")
      (description "二极管配置:独立式;正向压降(Vf):1.25V@150mA;直流反向耐压(Vr):100V;整流电流:150mA;反向恢复时间(Trr):4ns;")
      (fields (field (name "Manufacturer") "R+O(宏嘉诚)"))
      (libsource (lib "easyedapro") (part "1N4148W_C7420318"))
    )
    (comp (ref "D33")
      (value "1N4148W")
      (footprint "easyedapro:SOD-123_L2.7-W1.6-LS3.7-FD")
      (description "二极管配置:独立式;正向压降(Vf):1.25V@150mA;直流反向耐压(Vr):100V;整流电流:150mA;反向恢复时间(Trr):4ns;")
      (fields (field (name "Manufacturer") "R+O(宏嘉诚)"))
      (libsource (lib "easyedapro") (part "1N4148W_C7420318"))
    )
    (comp (ref "D34")
      (value "1N4148W")
      (footprint "easyedapro:SOD-123_L2.7-W1.6-LS3.7-FD")
      (description "二极管配置:独立式;正向压降(Vf):1.25V@150mA;直流反向耐压(Vr):100V;整流电流:150mA;反向恢复时间(Trr):4ns;")
      (fields (field (name "Manufacturer") "R+O(宏嘉诚)"))
      (libsource (lib "easyedapro") (part "1N4148W_C7420318"))
    )
    (comp (ref "D35")
      (value "1N4148W")
      (footprint "easyedapro:SOD-123_L2.7-W1.6-LS3.7-FD")
      (description "二极管配置:独立式;正向压降(Vf):1.25V@150mA;直流反向耐压(Vr):100V;整流电流:150mA;反向恢复时间(Trr):4ns;")
      (fields (field (name "Manufacturer") "R+O(宏嘉诚)"))
      (libsource (lib "easyedapro") (part "1N4148W_C7420318"))
    )
    (comp (ref "D36")
      (value "1N4148W")
      (footprint "easyedapro:SOD-123_L2.7-W1.6-LS3.7-FD")
      (description "二极管配置:独立式;正向压降(Vf):1.25V@150mA;直流反向耐压(Vr):100V;整流电流:150mA;反向恢复时间(Trr):4ns;")
      (fields (field (name "Manufacturer") "R+O(宏嘉诚)"))
      (libsource (lib "easyedapro") (part "1N4148W_C7420318"))
    )
    (comp (ref "D37")
      (value "1N4148W")
      (footprint "easyedapro:SOD-123_L2.7-W1.6-LS3.7-FD")
      (description "二极管配置:独立式;正向压降(Vf):1.25V@150mA;直流反向耐压(Vr):100V;整流电流:150mA;反向恢复时间(Trr):4ns;")
      (fields (field (name "Manufacturer") "R+O(宏嘉诚)"))
      (libsource (lib "easyedapro") (part "1N4148W_C7420318"))
    )
    (comp (ref "D38")
      (value "1N4148W")
      (footprint "easyedapro:SOD-123_L2.7-W1.6-LS3.7-FD")
      (description "二极管配置:独立式;正向压降(Vf):1.25V@150mA;直流反向耐压(Vr):100V;整流电流:150mA;反向恢复时间(Trr):4ns;")
      (fields (field (name "Manufacturer") "R+O(宏嘉诚)"))
      (libsource (lib "easyedapro") (part "1N4148W_C7420318"))
    )
    (comp (ref "D39")
      (value "1N4148W")
      (footprint "easyedapro:SOD-123_L2.7-W1.6-LS3.7-FD")
      (description "二极管配置:独立式;正向压降(Vf):1.25V@150mA;直流反向耐压(Vr):100V;整流电流:150mA;反向恢复时间(Trr):4ns;")
      (fields (field (name "Manufacturer") "R+O(宏嘉诚)"))
      (libsource (lib "easyedapro") (part "1N4148W_C7420318"))
    )
    (comp (ref "D40")
      (value "1N4148W")
      (footprint "easyedapro:SOD-123_L2.7-W1.6-LS3.7-FD")
      (description "二极管配置:独立式;正向压降(Vf):1.25V@150mA;直流反向耐压(Vr):100V;整流电流:150mA;反向恢复时间(Trr):4ns;")
      (fields (field (name "Manufacturer") "R+O(宏嘉诚)"))
      (libsource (lib "easyedapro") (part "1N4148W_C7420318"))
    )
    (comp (ref "D41")
      (value "1N4148W")
      (footprint "easyedapro:SOD-123_L2.7-W1.6-LS3.7-FD")
      (description "二极管配置:独立式;正向压降(Vf):1.25V@150mA;直流反向耐压(Vr):100V;整流电流:150mA;反向恢复时间(Trr):4ns;")
      (fields (field (name "Manufacturer") "R+O(宏嘉诚)"))
      (libsource (lib "easyedapro") (part "1N4148W_C7420318"))
    )
    (comp (ref "D42")
      (value "1N4148W")
      (footprint "easyedapro:SOD-123_L2.7-W1.6-LS3.7-FD")
      (description "二极管配置:独立式;正向压降(Vf):1.25V@150mA;直流反向耐压(Vr):100V;整流电流:150mA;反向恢复时间(Trr):4ns;")
      (fields (field (name "Manufacturer") "R+O(宏嘉诚)"))
      (libsource (lib "easyedapro") (part "1N4148W_C7420318"))
    )
    (comp (ref "D43")
      (value "1N4148W")
      (footprint "easyedapro:SOD-123_L2.7-W1.6-LS3.7-FD")
      (description "二极管配置:独立式;正向压降(Vf):1.25V@150mA;直流反向耐压(Vr):100V;整流电流:150mA;反向恢复时间(Trr):4ns;")
      (fields (field (name "Manufacturer") "R+O(宏嘉诚)"))
      (libsource (lib "easyedapro") (part "1N4148W_C7420318"))
    )
    (comp (ref "D44")
      (value "1N4148W")
      (footprint "easyedapro:SOD-123_L2.7-W1.6-LS3.7-FD")
      (description "二极管配置:独立式;正向压降(Vf):1.25V@150mA;直流反向耐压(Vr):100V;整流电流:150mA;反向恢复时间(Trr):4ns;")
      (fields (field (name "Manufacturer") "R+O(宏嘉诚)"))
      (libsource (lib "easyedapro") (part "1N4148W_C7420318"))
    )
    (comp (ref "D45")
      (value "1N4148W")
      (footprint "easyedapro:SOD-123_L2.7-W1.6-LS3.7-FD")
      (description "二极管配置:独立式;正向压降(Vf):1.25V@150mA;直流反向耐压(Vr):100V;整流电流:150mA;反向恢复时间(Trr):4ns;")
      (fields (field (name "Manufacturer") "R+O(宏嘉诚)"))
      (libsource (lib "easyedapro") (part "1N4148W_C7420318"))
    )
    (comp (ref "D46")
      (value "1N4148W")
      (footprint "easyedapro:SOD-123_L2.7-W1.6-LS3.7-FD")
      (description "二极管配置:独立式;正向压降(Vf):1.25V@150mA;直流反向耐压(Vr):100V;整流电流:150mA;反向恢复时间(Trr):4ns;")
      (fields (field (name "Manufacturer") "R+O(宏嘉诚)"))
      (libsource (lib "easyedapro") (part "1N4148W_C7420318"))
    )
    (comp (ref "D47")
      (value "1N4148W")
      (footprint "easyedapro:SOD-123_L2.7-W1.6-LS3.7-FD")
      (description "二极管配置:独立式;正向压降(Vf):1.25V@150mA;直流反向耐压(Vr):100V;整流电流:150mA;反向恢复时间(Trr):4ns;")
      (fields (field (name "Manufacturer") "R+O(宏嘉诚)"))
      (libsource (lib "easyedapro") (part "1N4148W_C7420318"))
    )
    (comp (ref "D48")
      (value "1N4148W")
      (footprint "easyedapro:SOD-123_L2.7-W1.6-LS3.7-FD")
      (description "二极管配置:独立式;正向压降(Vf):1.25V@150mA;直流反向耐压(Vr):100V;整流电流:150mA;反向恢复时间(Trr):4ns;")
      (fields (field (name "Manufacturer") "R+O(宏嘉诚)"))
      (libsource (lib "easyedapro") (part "1N4148W_C7420318"))
    )
    (comp (ref "D49")
      (value "1N4148W")
      (footprint "easyedapro:SOD-123_L2.7-W1.6-LS3.7-FD")
      (description "二极管配置:独立式;正向压降(Vf):1.25V@150mA;直流反向耐压(Vr):100V;整流电流:150mA;反向恢复时间(Trr):4ns;")
      (fields (field (name "Manufacturer") "R+O(宏嘉诚)"))
      (libsource (lib "easyedapro") (part "1N4148W_C7420318"))
    )
    (comp (ref "D50")
      (value "1N4148W")
      (footprint "easyedapro:SOD-123_L2.7-W1.6-LS3.7-FD")
      (description "二极管配置:独立式;正向压降(Vf):1.25V@150mA;直流反向耐压(Vr):100V;整流电流:150mA;反向恢复时间(Trr):4ns;")
      (fields (field (name "Manufacturer") "R+O(宏嘉诚)"))
      (libsource (lib "easyedapro") (part "1N4148W_C7420318"))
    )
    (comp (ref "D51")
      (value "1N4148W")
      (footprint "easyedapro:SOD-123_L2.7-W1.6-LS3.7-FD")
      (description "二极管配置:独立式;正向压降(Vf):1.25V@150mA;直流反向耐压(Vr):100V;整流电流:150mA;反向恢复时间(Trr):4ns;")
      (fields (field (name "Manufacturer") "R+O(宏嘉诚)"))
      (libsource (lib "easyedapro") (part "1N4148W_C7420318"))
    )
    (comp (ref "D52")
      (value "1N4148W")
      (footprint "easyedapro:SOD-123_L2.7-W1.6-LS3.7-FD")
      (description "二极管配置:独立式;正向压降(Vf):1.25V@150mA;直流反向耐压(Vr):100V;整流电流:150mA;反向恢复时间(Trr):4ns;")
      (fields (field (name "Manufacturer") "R+O(宏嘉诚)"))
      (libsource (lib "easyedapro") (part "1N4148W_C7420318"))
    )
    (comp (ref "D53")
      (value "1N4148W")
      (footprint "easyedapro:SOD-123_L2.7-W1.6-LS3.7-FD")
      (description "二极管配置:独立式;正向压降(Vf):1.25V@150mA;直流反向耐压(Vr):100V;整流电流:150mA;反向恢复时间(Trr):4ns;")
      (fields (field (name "Manufacturer") "R+O(宏嘉诚)"))
      (libsource (lib "easyedapro") (part "1N4148W_C7420318"))
    )
    (comp (ref "D54")
      (value "1N4148W")
      (footprint "easyedapro:SOD-123_L2.7-W1.6-LS3.7-FD")
      (description "二极管配置:独立式;正向压降(Vf):1.25V@150mA;直流反向耐压(Vr):100V;整流电流:150mA;反向恢复时间(Trr):4ns;")
      (fields (field (name "Manufacturer") "R+O(宏嘉诚)"))
      (libsource (lib "easyedapro") (part "1N4148W_C7420318"))
    )
    (comp (ref "D55")
      (value "1N4148W")
      (footprint "easyedapro:SOD-123_L2.7-W1.6-LS3.7-FD")
      (description "二极管配置:独立式;正向压降(Vf):1.25V@150mA;直流反向耐压(Vr):100V;整流电流:150mA;反向恢复时间(Trr):4ns;")
      (fields (field (name "Manufacturer") "R+O(宏嘉诚)"))
      (libsource (lib "easyedapro") (part "1N4148W_C7420318"))
    )
    (comp (ref "D56")
      (value "1N4148W")
      (footprint "easyedapro:SOD-123_L2.7-W1.6-LS3.7-FD")
      (description "二极管配置:独立式;正向压降(Vf):1.25V@150mA;直流反向耐压(Vr):100V;整流电流:150mA;反向恢复时间(Trr):4ns;")
      (fields (field (name "Manufacturer") "R+O(宏嘉诚)"))
      (libsource (lib "easyedapro") (part "1N4148W_C7420318"))
    )
    (comp (ref "D57")
      (value "1N4148W")
      (footprint "easyedapro:SOD-123_L2.7-W1.6-LS3.7-FD")
      (description "二极管配置:独立式;正向压降(Vf):1.25V@150mA;直流反向耐压(Vr):100V;整流电流:150mA;反向恢复时间(Trr):4ns;")
      (fields (field (name "Manufacturer") "R+O(宏嘉诚)"))
      (libsource (lib "easyedapro") (part "1N4148W_C7420318"))
    )
    (comp (ref "D58")
      (value "1N4148W")
      (footprint "easyedapro:SOD-123_L2.7-W1.6-LS3.7-FD")
      (description "二极管配置:独立式;正向压降(Vf):1.25V@150mA;直流反向耐压(Vr):100V;整流电流:150mA;反向恢复时间(Trr):4ns;")
      (fields (field (name "Manufacturer") "R+O(宏嘉诚)"))
      (libsource (lib "easyedapro") (part "1N4148W_C7420318"))
    )
    (comp (ref "D59")
      (value "1N4148W")
      (footprint "easyedapro:SOD-123_L2.7-W1.6-LS3.7-FD")
      (description "二极管配置:独立式;正向压降(Vf):1.25V@150mA;直流反向耐压(Vr):100V;整流电流:150mA;反向恢复时间(Trr):4ns;")
      (fields (field (name "Manufacturer") "R+O(宏嘉诚)"))
      (libsource (lib "easyedapro") (part "1N4148W_C7420318"))
    )
    (comp (ref "D60")
      (value "1N4148W")
      (footprint "easyedapro:SOD-123_L2.7-W1.6-LS3.7-FD")
      (description "二极管配置:独立式;正向压降(Vf):1.25V@150mA;直流反向耐压(Vr):100V;整流电流:150mA;反向恢复时间(Trr):4ns;")
      (fields (field (name "Manufacturer") "R+O(宏嘉诚)"))
      (libsource (lib "easyedapro") (part "1N4148W_C7420318"))
    )
    (comp (ref "D61")
      (value "1N4148W")
      (footprint "easyedapro:SOD-123_L2.7-W1.6-LS3.7-FD")
      (description "二极管配置:独立式;正向压降(Vf):1.25V@150mA;直流反向耐压(Vr):100V;整流电流:150mA;反向恢复时间(Trr):4ns;")
      (fields (field (name "Manufacturer") "R+O(宏嘉诚)"))
      (libsource (lib "easyedapro") (part "1N4148W_C7420318"))
    )
    (comp (ref "D62")
      (value "1N4148W")
      (footprint "easyedapro:SOD-123_L2.7-W1.6-LS3.7-FD")
      (description "二极管配置:独立式;正向压降(Vf):1.25V@150mA;直流反向耐压(Vr):100V;整流电流:150mA;反向恢复时间(Trr):4ns;")
      (fields (field (name "Manufacturer") "R+O(宏嘉诚)"))
      (libsource (lib "easyedapro") (part "1N4148W_C7420318"))
    )
    (comp (ref "D63")
      (value "1N4148W")
      (footprint "easyedapro:SOD-123_L2.7-W1.6-LS3.7-FD")
      (description "二极管配置:独立式;正向压降(Vf):1.25V@150mA;直流反向耐压(Vr):100V;整流电流:150mA;反向恢复时间(Trr):4ns;")
      (fields (field (name "Manufacturer") "R+O(宏嘉诚)"))
      (libsource (lib "easyedapro") (part "1N4148W_C7420318"))
    )
    (comp (ref "D65")
      (value "1N4148W")
      (footprint "easyedapro:SOD-123_L2.7-W1.6-LS3.7-FD")
      (description "二极管配置:独立式;正向压降(Vf):1.25V@150mA;直流反向耐压(Vr):100V;整流电流:150mA;反向恢复时间(Trr):4ns;")
      (fields (field (name "Manufacturer") "R+O(宏嘉诚)"))
      (libsource (lib "easyedapro") (part "1N4148W_C7420318"))
    )
    (comp (ref "D66")
      (value "1N4148W")
      (footprint "easyedapro:SOD-123_L2.7-W1.6-LS3.7-FD")
      (description "二极管配置:独立式;正向压降(Vf):1.25V@150mA;直流反向耐压(Vr):100V;整流电流:150mA;反向恢复时间(Trr):4ns;")
      (fields (field (name "Manufacturer") "R+O(宏嘉诚)"))
      (libsource (lib "easyedapro") (part "1N4148W_C7420318"))
    )
    (comp (ref "D67")
      (value "1N4148W")
      (footprint "easyedapro:SOD-123_L2.7-W1.6-LS3.7-FD")
      (description "二极管配置:独立式;正向压降(Vf):1.25V@150mA;直流反向耐压(Vr):100V;整流电流:150mA;反向恢复时间(Trr):4ns;")
      (fields (field (name "Manufacturer") "R+O(宏嘉诚)"))
      (libsource (lib "easyedapro") (part "1N4148W_C7420318"))
    )
    (comp (ref "D68")
      (value "1N4148W")
      (footprint "easyedapro:SOD-123_L2.7-W1.6-LS3.7-FD")
      (description "二极管配置:独立式;正向压降(Vf):1.25V@150mA;直流反向耐压(Vr):100V;整流电流:150mA;反向恢复时间(Trr):4ns;")
      (fields (field (name "Manufacturer") "R+O(宏嘉诚)"))
      (libsource (lib "easyedapro") (part "1N4148W_C7420318"))
    )
    (comp (ref "D69")
      (value "1N4148W")
      (footprint "easyedapro:SOD-123_L2.7-W1.6-LS3.7-FD")
      (description "二极管配置:独立式;正向压降(Vf):1.25V@150mA;直流反向耐压(Vr):100V;整流电流:150mA;反向恢复时间(Trr):4ns;")
      (fields (field (name "Manufacturer") "R+O(宏嘉诚)"))
      (libsource (lib "easyedapro") (part "1N4148W_C7420318"))
    )
    (comp (ref "D70")
      (value "1N4148W")
      (footprint "easyedapro:SOD-123_L2.7-W1.6-LS3.7-FD")
      (description "二极管配置:独立式;正向压降(Vf):1.25V@150mA;直流反向耐压(Vr):100V;整流电流:150mA;反向恢复时间(Trr):4ns;")
      (fields (field (name "Manufacturer") "R+O(宏嘉诚)"))
      (libsource (lib "easyedapro") (part "1N4148W_C7420318"))
    )
    (comp (ref "D71")
      (value "1N4148W")
      (footprint "easyedapro:SOD-123_L2.7-W1.6-LS3.7-FD")
      (description "二极管配置:独立式;正向压降(Vf):1.25V@150mA;直流反向耐压(Vr):100V;整流电流:150mA;反向恢复时间(Trr):4ns;")
      (fields (field (name "Manufacturer") "R+O(宏嘉诚)"))
      (libsource (lib "easyedapro") (part "1N4148W_C7420318"))
    )
    (comp (ref "D72")
      (value "1N4148W")
      (footprint "easyedapro:SOD-123_L2.7-W1.6-LS3.7-FD")
      (description "二极管配置:独立式;正向压降(Vf):1.25V@150mA;直流反向耐压(Vr):100V;整流电流:150mA;反向恢复时间(Trr):4ns;")
      (fields (field (name "Manufacturer") "R+O(宏嘉诚)"))
      (libsource (lib "easyedapro") (part "1N4148W_C7420318"))
    )
    (comp (ref "D73")
      (value "1N4148W")
      (footprint "easyedapro:SOD-123_L2.7-W1.6-LS3.7-FD")
      (description "二极管配置:独立式;正向压降(Vf):1.25V@150mA;直流反向耐压(Vr):100V;整流电流:150mA;反向恢复时间(Trr):4ns;")
      (fields (field (name "Manufacturer") "R+O(宏嘉诚)"))
      (libsource (lib "easyedapro") (part "1N4148W_C7420318"))
    )
    (comp (ref "D74")
      (value "1N4148W")
      (footprint "easyedapro:SOD-123_L2.7-W1.6-LS3.7-FD")
      (description "二极管配置:独立式;正向压降(Vf):1.25V@150mA;直流反向耐压(Vr):100V;整流电流:150mA;反向恢复时间(Trr):4ns;")
      (fields (field (name "Manufacturer") "R+O(宏嘉诚)"))
      (libsource (lib "easyedapro") (part "1N4148W_C7420318"))
    )
    (comp (ref "D75")
      (value "1N4148W")
      (footprint "easyedapro:SOD-123_L2.7-W1.6-LS3.7-FD")
      (description "二极管配置:独立式;正向压降(Vf):1.25V@150mA;直流反向耐压(Vr):100V;整流电流:150mA;反向恢复时间(Trr):4ns;")
      (fields (field (name "Manufacturer") "R+O(宏嘉诚)"))
      (libsource (lib "easyedapro") (part "1N4148W_C7420318"))
    )
    (comp (ref "D76")
      (value "1N4148W")
      (footprint "easyedapro:SOD-123_L2.7-W1.6-LS3.7-FD")
      (description "二极管配置:独立式;正向压降(Vf):1.25V@150mA;直流反向耐压(Vr):100V;整流电流:150mA;反向恢复时间(Trr):4ns;")
      (fields (field (name "Manufacturer") "R+O(宏嘉诚)"))
      (libsource (lib "easyedapro") (part "1N4148W_C7420318"))
    )
    (comp (ref "D77")
      (value "1N4148W")
      (footprint "easyedapro:SOD-123_L2.7-W1.6-LS3.7-FD")
      (description "二极管配置:独立式;正向压降(Vf):1.25V@150mA;直流反向耐压(Vr):100V;整流电流:150mA;反向恢复时间(Trr):4ns;")
      (fields (field (name "Manufacturer") "R+O(宏嘉诚)"))
      (libsource (lib "easyedapro") (part "1N4148W_C7420318"))
    )
    (comp (ref "D78")
      (value "1N4148W")
      (footprint "easyedapro:SOD-123_L2.7-W1.6-LS3.7-FD")
      (description "二极管配置:独立式;正向压降(Vf):1.25V@150mA;直流反向耐压(Vr):100V;整流电流:150mA;反向恢复时间(Trr):4ns;")
      (fields (field (name "Manufacturer") "R+O(宏嘉诚)"))
      (libsource (lib "easyedapro") (part "1N4148W_C7420318"))
    )
    (comp (ref "D79")
      (value "1N4148W")
      (footprint "easyedapro:SOD-123_L2.7-W1.6-LS3.7-FD")
      (description "二极管配置:独立式;正向压降(Vf):1.25V@150mA;直流反向耐压(Vr):100V;整流电流:150mA;反向恢复时间(Trr):4ns;")
      (fields (field (name "Manufacturer") "R+O(宏嘉诚)"))
      (libsource (lib "easyedapro") (part "1N4148W_C7420318"))
    )
    (comp (ref "D80")
      (value "1N4148W")
      (footprint "easyedapro:SOD-123_L2.7-W1.6-LS3.7-FD")
      (description "二极管配置:独立式;正向压降(Vf):1.25V@150mA;直流反向耐压(Vr):100V;整流电流:150mA;反向恢复时间(Trr):4ns;")
      (fields (field (name "Manufacturer") "R+O(宏嘉诚)"))
      (libsource (lib "easyedapro") (part "1N4148W_C7420318"))
    )
    (comp (ref "D81")
      (value "1N4148W")
      (footprint "easyedapro:SOD-123_L2.7-W1.6-LS3.7-FD")
      (description "二极管配置:独立式;正向压降(Vf):1.25V@150mA;直流反向耐压(Vr):100V;整流电流:150mA;反向恢复时间(Trr):4ns;")
      (fields (field (name "Manufacturer") "R+O(宏嘉诚)"))
      (libsource (lib "easyedapro") (part "1N4148W_C7420318"))
    )
    (comp (ref "D82")
      (value "1N4148W")
      (footprint "easyedapro:SOD-123_L2.7-W1.6-LS3.7-FD")
      (description "二极管配置:独立式;正向压降(Vf):1.25V@150mA;直流反向耐压(Vr):100V;整流电流:150mA;反向恢复时间(Trr):4ns;")
      (fields (field (name "Manufacturer") "R+O(宏嘉诚)"))
      (libsource (lib "easyedapro") (part "1N4148W_C7420318"))
    )
    (comp (ref "D83")
      (value "1N4148W")
      (footprint "easyedapro:SOD-123_L2.7-W1.6-LS3.7-FD")
      (description "二极管配置:独立式;正向压降(Vf):1.25V@150mA;直流反向耐压(Vr):100V;整流电流:150mA;反向恢复时间(Trr):4ns;")
      (fields (field (name "Manufacturer") "R+O(宏嘉诚)"))
      (libsource (lib "easyedapro") (part "1N4148W_C7420318"))
    )
    (comp (ref "R1")
      (value "500Ω")
      (footprint "easyedapro:R0805")
      (description "电阻类型:薄膜电阻;阻值:500Ω;精度:±0.1%;功率:125mW;工作电压:150V;温度系数:±25ppm/°C;")
      (fields (field (name "Manufacturer Part") "ARG05BTC5000") (field (name "Manufacturer") "Viking(光颉)"))
      (libsource (lib "easyedapro") (part "ARG05BTC5000"))
    )
    (comp (ref "R2")
      (value "500Ω")
      (footprint "easyedapro:R0805")
      (description "电阻类型:薄膜电阻;阻值:500Ω;精度:±0.1%;功率:125mW;工作电压:150V;温度系数:±25ppm/°C;")
      (fields (field (name "Manufacturer Part") "ARG05BTC5000") (field (name "Manufacturer") "Viking(光颉)"))
      (libsource (lib "easyedapro") (part "ARG05BTC5000"))
    )
    (comp (ref "R3")
      (value "500Ω")
      (footprint "easyedapro:R0805")
      (description "电阻类型:薄膜电阻;阻值:500Ω;精度:±0.1%;功率:125mW;工作电压:150V;温度系数:±25ppm/°C;")
      (fields (field (name "Manufacturer Part") "ARG05BTC5000") (field (name "Manufacturer") "Viking(光颉)"))
      (libsource (lib "easyedapro") (part "ARG05BTC5000"))
    )
    (comp (ref "R4")
      (value "500Ω")
      (footprint "easyedapro:R0805")
      (description "电阻类型:薄膜电阻;阻值:500Ω;精度:±0.1%;功率:125mW;工作电压:150V;温度系数:±25ppm/°C;")
      (fields (field (name "Manufacturer Part") "ARG05BTC5000") (field (name "Manufacturer") "Viking(光颉)"))
      (libsource (lib "easyedapro") (part "ARG05BTC5000"))
    )
    (comp (ref "R5")
      (value "500Ω")
      (footprint "easyedapro:R0805")
      (description "电阻类型:薄膜电阻;阻值:500Ω;精度:±0.1%;功率:125mW;工作电压:150V;温度系数:±25ppm/°C;")
      (fields (field (name "Manufacturer Part") "ARG05BTC5000") (field (name "Manufacturer") "Viking(光颉)"))
      (libsource (lib "easyedapro") (part "ARG05BTC5000"))
    )
    (comp (ref "R6")
      (value "500Ω")
      (footprint "easyedapro:R0805")
      (description "电阻类型:薄膜电阻;阻值:500Ω;精度:±0.1%;功率:125mW;工作电压:150V;温度系数:±25ppm/°C;")
      (fields (field (name "Manufacturer Part") "ARG05BTC5000") (field (name "Manufacturer") "Viking(光颉)"))
      (libsource (lib "easyedapro") (part "ARG05BTC5000"))
    )
    (comp (ref "R7")
      (value "500Ω")
      (footprint "easyedapro:R0805")
      (description "电阻类型:薄膜电阻;阻值:500Ω;精度:±0.1%;功率:125mW;工作电压:150V;温度系数:±25ppm/°C;")
      (fields (field (name "Manufacturer Part") "ARG05BTC5000") (field (name "Manufacturer") "Viking(光颉)"))
      (libsource (lib "easyedapro") (part "ARG05BTC5000"))
    )
    (comp (ref "R8")
      (value "500Ω")
      (footprint "easyedapro:R0805")
      (description "电阻类型:薄膜电阻;阻值:500Ω;精度:±0.1%;功率:125mW;工作电压:150V;温度系数:±25ppm/°C;")
      (fields (field (name "Manufacturer Part") "ARG05BTC5000") (field (name "Manufacturer") "Viking(光颉)"))
      (libsource (lib "easyedapro") (part "ARG05BTC5000"))
    )
    (comp (ref "R9")
      (value "500Ω")
      (footprint "easyedapro:R0805")
      (description "电阻类型:薄膜电阻;阻值:500Ω;精度:±0.1%;功率:125mW;工作电压:150V;温度系数:±25ppm/°C;")
      (fields (field (name "Manufacturer Part") "ARG05BTC5000") (field (name "Manufacturer") "Viking(光颉)"))
      (libsource (lib "easyedapro") (part "ARG05BTC5000"))
    )
    (comp (ref "R10")
      (value "500Ω")
      (footprint "easyedapro:R0805")
      (description "电阻类型:薄膜电阻;阻值:500Ω;精度:±0.1%;功率:125mW;工作电压:150V;温度系数:±25ppm/°C;")
      (fields (field (name "Manufacturer Part") "ARG05BTC5000") (field (name "Manufacturer") "Viking(光颉)"))
      (libsource (lib "easyedapro") (part "ARG05BTC5000"))
    )
    (comp (ref "R11")
      (value "500Ω")
      (footprint "easyedapro:R0805")
      (description "电阻类型:薄膜电阻;阻值:500Ω;精度:±0.1%;功率:125mW;工作电压:150V;温度系数:±25ppm/°C;")
      (fields (field (name "Manufacturer Part") "ARG05BTC5000") (field (name "Manufacturer") "Viking(光颉)"))
      (libsource (lib "easyedapro") (part "ARG05BTC5000"))
    )
    (comp (ref "R12")
      (value "500Ω")
      (footprint "easyedapro:R0805")
      (description "电阻类型:薄膜电阻;阻值:500Ω;精度:±0.1%;功率:125mW;工作电压:150V;温度系数:±25ppm/°C;")
      (fields (field (name "Manufacturer Part") "ARG05BTC5000") (field (name "Manufacturer") "Viking(光颉)"))
      (libsource (lib "easyedapro") (part "ARG05BTC5000"))
    )
    (comp (ref "U1")
      (value "~")
      (footprint "easyedapro:凯华rgb灯")
      (libsource (lib "easyedapro") (part "凯华rgb键轴"))
    )
    (comp (ref "U2")
      (value "~")
      (footprint "easyedapro:凯华rgb灯")
      (libsource (lib "easyedapro") (part "凯华rgb键轴"))
    )
    (comp (ref "U3")
      (value "~")
      (footprint "easyedapro:凯华rgb灯")
      (libsource (lib "easyedapro") (part "凯华rgb键轴"))
    )
    (comp (ref "U4")
      (value "~")
      (footprint "easyedapro:凯华rgb灯")
      (libsource (lib "easyedapro") (part "凯华rgb键轴"))
    )
    (comp (ref "U5")
      (value "~")
      (footprint "easyedapro:凯华rgb灯")
      (libsource (lib "easyedapro") (part "凯华rgb键轴"))
    )
    (comp (ref "U6")
      (value "~")
      (footprint "easyedapro:凯华rgb灯")
      (libsource (lib "easyedapro") (part "凯华rgb键轴"))
    )
    (comp (ref "U7")
      (value "~")
      (footprint "easyedapro:凯华rgb灯")
      (libsource (lib "easyedapro") (part "凯华rgb键轴"))
    )
    (comp (ref "U8")
      (value "~")
      (footprint "easyedapro:凯华rgb灯")
      (libsource (lib "easyedapro") (part "凯华rgb键轴"))
    )
    (comp (ref "U9")
      (value "~")
      (footprint "easyedapro:凯华rgb灯")
      (libsource (lib "easyedapro") (part "凯华rgb键轴"))
    )
    (comp (ref "U10")
      (value "~")
      (footprint "easyedapro:凯华rgb灯")
      (libsource (lib "easyedapro") (part "凯华rgb键轴"))
    )
    (comp (ref "U11")
      (value "~")
      (footprint "easyedapro:凯华rgb灯")
      (libsource (lib "easyedapro") (part "凯华rgb键轴"))
    )
    (comp (ref "U12")
      (value "~")
      (footprint "easyedapro:凯华rgb灯")
      (libsource (lib "easyedapro") (part "凯华rgb键轴"))
    )
    (comp (ref "U13")
      (value "~")
      (footprint "easyedapro:凯华rgb灯")
      (libsource (lib "easyedapro") (part "凯华rgb键轴"))
    )
    (comp (ref "U14")
      (value "~")
      (footprint "easyedapro:凯华rgb灯")
      (libsource (lib "easyedapro") (part "凯华rgb键轴"))
    )
    (comp (ref "U15")
      (value "~")
      (footprint "easyedapro:凯华rgb灯")
      (libsource (lib "easyedapro") (part "凯华rgb键轴"))
    )
    (comp (ref "U16")
      (value "~")
      (footprint "easyedapro:凯华rgb灯")
      (libsource (lib "easyedapro") (part "凯华rgb键轴"))
    )
    (comp (ref "U17")
      (value "~")
      (footprint "easyedapro:凯华rgb灯")
      (libsource (lib "easyedapro") (part "凯华rgb键轴"))
    )
    (comp (ref "U18")
      (value "~")
      (footprint "easyedapro:凯华rgb灯")
      (libsource (lib "easyedapro") (part "凯华rgb键轴"))
    )
    (comp (ref "U19")
      (value "~")
      (footprint "easyedapro:凯华rgb灯")
      (libsource (lib "easyedapro") (part "凯华rgb键轴"))
    )
    (comp (ref "U20")
      (value "~")
      (footprint "easyedapro:凯华rgb灯")
      (libsource (lib "easyedapro") (part "凯华rgb键轴"))
    )
    (comp (ref "U21")
      (value "~")
      (footprint "easyedapro:凯华rgb灯")
      (libsource (lib "easyedapro") (part "凯华rgb键轴"))
    )
    (comp (ref "U22")
      (value "~")
      (footprint "easyedapro:凯华rgb灯")
      (libsource (lib "easyedapro") (part "凯华rgb键轴"))
    )
    (comp (ref "U23")
      (value "~")
      (footprint "easyedapro:凯华rgb灯")
      (libsource (lib "easyedapro") (part "凯华rgb键轴"))
    )
    (comp (ref "U24")
      (value "~")
      (footprint "easyedapro:凯华rgb灯")
      (libsource (lib "easyedapro") (part "凯华rgb键轴"))
    )
    (comp (ref "U25")
      (value "~")
      (footprint "easyedapro:凯华rgb灯")
      (libsource (lib "easyedapro") (part "凯华rgb键轴"))
    )
    (comp (ref "U26")
      (value "~")
      (footprint "easyedapro:凯华rgb灯")
      (libsource (lib "easyedapro") (part "凯华rgb键轴"))
    )
    (comp (ref "U27")
      (value "~")
      (footprint "easyedapro:凯华rgb灯")
      (libsource (lib "easyedapro") (part "凯华rgb键轴"))
    )
    (comp (ref "U28")
      (value "~")
      (footprint "easyedapro:凯华rgb灯")
      (libsource (lib "easyedapro") (part "凯华rgb键轴"))
    )
    (comp (ref "U29")
      (value "~")
      (footprint "easyedapro:凯华rgb灯")
      (libsource (lib "easyedapro") (part "凯华rgb键轴"))
    )
    (comp (ref "U30")
      (value "~")
      (footprint "easyedapro:凯华rgb灯")
      (libsource (lib "easyedapro") (part "凯华rgb键轴"))
    )
    (comp (ref "U31")
      (value "~")
      (footprint "easyedapro:凯华rgb灯")
      (libsource (lib "easyedapro") (part "凯华rgb键轴"))
    )
    (comp (ref "U32")
      (value "~")
      (footprint "easyedapro:凯华rgb灯")
      (libsource (lib "easyedapro") (part "凯华rgb键轴"))
    )
    (comp (ref "U33")
      (value "~")
      (footprint "easyedapro:凯华rgb灯")
      (libsource (lib "easyedapro") (part "凯华rgb键轴"))
    )
    (comp (ref "U34")
      (value "~")
      (footprint "easyedapro:凯华rgb灯")
      (libsource (lib "easyedapro") (part "凯华rgb键轴"))
    )
    (comp (ref "U35")
      (value "~")
      (footprint "easyedapro:凯华rgb灯")
      (libsource (lib "easyedapro") (part "凯华rgb键轴"))
    )
    (comp (ref "U36")
      (value "~")
      (footprint "easyedapro:凯华rgb灯")
      (libsource (lib "easyedapro") (part "凯华rgb键轴"))
    )
    (comp (ref "U37")
      (value "~")
      (footprint "easyedapro:凯华rgb灯")
      (libsource (lib "easyedapro") (part "凯华rgb键轴"))
    )
    (comp (ref "U38")
      (value "~")
      (footprint "easyedapro:凯华rgb灯")
      (libsource (lib "easyedapro") (part "凯华rgb键轴"))
    )
    (comp (ref "U39")
      (value "~")
      (footprint "easyedapro:凯华rgb灯")
      (libsource (lib "easyedapro") (part "凯华rgb键轴"))
    )
    (comp (ref "U40")
      (value "~")
      (footprint "easyedapro:凯华rgb灯")
      (libsource (lib "easyedapro") (part "凯华rgb键轴"))
    )
    (comp (ref "U41")
      (value "~")
      (footprint "easyedapro:凯华rgb灯")
      (libsource (lib "easyedapro") (part "凯华rgb键轴"))
    )
    (comp (ref "U42")
      (value "~")
      (footprint "easyedapro:凯华rgb灯")
      (libsource (lib "easyedapro") (part "凯华rgb键轴"))
    )
    (comp (ref "U43")
      (value "~")
      (footprint "easyedapro:凯华rgb灯")
      (libsource (lib "easyedapro") (part "凯华rgb键轴"))
    )
    (comp (ref "U44")
      (value "~")
      (footprint "easyedapro:凯华rgb灯")
      (libsource (lib "easyedapro") (part "凯华rgb键轴"))
    )
    (comp (ref "U45")
      (value "~")
      (footprint "easyedapro:凯华rgb灯")
      (libsource (lib "easyedapro") (part "凯华rgb键轴"))
    )
    (comp (ref "U46")
      (value "~")
      (footprint "easyedapro:凯华rgb灯")
      (libsource (lib "easyedapro") (part "凯华rgb键轴"))
    )
    (comp (ref "U47")
      (value "~")
      (footprint "easyedapro:凯华rgb灯")
      (libsource (lib "easyedapro") (part "凯华rgb键轴"))
    )
    (comp (ref "U48")
      (value "~")
      (footprint "easyedapro:凯华rgb灯")
      (libsource (lib "easyedapro") (part "凯华rgb键轴"))
    )
    (comp (ref "U49")
      (value "~")
      (footprint "easyedapro:凯华rgb灯")
      (libsource (lib "easyedapro") (part "凯华rgb键轴"))
    )
    (comp (ref "U50")
      (value "~")
      (footprint "easyedapro:凯华rgb灯")
      (libsource (lib "easyedapro") (part "凯华rgb键轴"))
    )
    (comp (ref "U51")
      (value "~")
      (footprint "easyedapro:凯华rgb灯")
      (libsource (lib "easyedapro") (part "凯华rgb键轴"))
    )
    (comp (ref "U52")
      (value "~")
      (footprint "easyedapro:凯华rgb灯")
      (libsource (lib "easyedapro") (part "凯华rgb键轴"))
    )
    (comp (ref "U53")
      (value "~")
      (footprint "easyedapro:凯华rgb灯")
      (libsource (lib "easyedapro") (part "凯华rgb键轴"))
    )
    (comp (ref "U54")
      (value "~")
      (footprint "easyedapro:凯华rgb灯")
      (libsource (lib "easyedapro") (part "凯华rgb键轴"))
    )
    (comp (ref "U55")
      (value "~")
      (footprint "easyedapro:凯华rgb灯")
      (libsource (lib "easyedapro") (part "凯华rgb键轴"))
    )
    (comp (ref "U56")
      (value "~")
      (footprint "easyedapro:凯华rgb灯")
      (libsource (lib "easyedapro") (part "凯华rgb键轴"))
    )
    (comp (ref "U57")
      (value "~")
      (footprint "easyedapro:凯华rgb灯")
      (libsource (lib "easyedapro") (part "凯华rgb键轴"))
    )
    (comp (ref "U58")
      (value "~")
      (footprint "easyedapro:凯华rgb灯")
      (libsource (lib "easyedapro") (part "凯华rgb键轴"))
    )
    (comp (ref "U59")
      (value "~")
      (footprint "easyedapro:凯华rgb灯")
      (libsource (lib "easyedapro") (part "凯华rgb键轴"))
    )
    (comp (ref "U60")
      (value "~")
      (footprint "easyedapro:凯华rgb灯")
      (libsource (lib "easyedapro") (part "凯华rgb键轴"))
    )
    (comp (ref "U61")
      (value "~")
      (footprint "easyedapro:凯华rgb灯")
      (libsource (lib "easyedapro") (part "凯华rgb键轴"))
    )
    (comp (ref "U62")
      (value "~")
      (footprint "easyedapro:凯华rgb灯")
      (libsource (lib "easyedapro") (part "凯华rgb键轴"))
    )
    (comp (ref "U63")
      (value "~")
      (footprint "easyedapro:凯华rgb灯")
      (libsource (lib "easyedapro") (part "凯华rgb键轴"))
    )
    (comp (ref "U64")
      (value "~")
      (footprint "easyedapro:凯华rgb灯")
      (libsource (lib "easyedapro") (part "凯华rgb键轴"))
    )
    (comp (ref "U65")
      (value "~")
      (footprint "easyedapro:凯华rgb灯")
      (libsource (lib "easyedapro") (part "凯华rgb键轴"))
    )
    (comp (ref "U66")
      (value "~")
      (footprint "easyedapro:凯华rgb灯")
      (libsource (lib "easyedapro") (part "凯华rgb键轴"))
    )
    (comp (ref "U67")
      (value "~")
      (footprint "easyedapro:凯华rgb灯")
      (libsource (lib "easyedapro") (part "凯华rgb键轴"))
    )
    (comp (ref "U68")
      (value "~")
      (footprint "easyedapro:凯华rgb灯")
      (libsource (lib "easyedapro") (part "凯华rgb键轴"))
    )
    (comp (ref "U69")
      (value "~")
      (footprint "easyedapro:凯华rgb灯")
      (libsource (lib "easyedapro") (part "凯华rgb键轴"))
    )
    (comp (ref "U70")
      (value "~")
      (footprint "easyedapro:凯华rgb灯")
      (libsource (lib "easyedapro") (part "凯华rgb键轴"))
    )
    (comp (ref "U71")
      (value "~")
      (footprint "easyedapro:凯华rgb灯")
      (libsource (lib "easyedapro") (part "凯华rgb键轴"))
    )
    (comp (ref "U72")
      (value "~")
      (footprint "easyedapro:凯华rgb灯")
      (libsource (lib "easyedapro") (part "凯华rgb键轴"))
    )
    (comp (ref "U73")
      (value "~")
      (footprint "easyedapro:凯华rgb灯")
      (libsource (lib "easyedapro") (part "凯华rgb键轴"))
    )
    (comp (ref "U74")
      (value "~")
      (footprint "easyedapro:凯华rgb灯")
      (libsource (lib "easyedapro") (part "凯华rgb键轴"))
    )
    (comp (ref "U75")
      (value "~")
      (footprint "easyedapro:凯华rgb灯")
      (libsource (lib "easyedapro") (part "凯华rgb键轴"))
    )
    (comp (ref "U76")
      (value "~")
      (footprint "easyedapro:凯华rgb灯")
      (libsource (lib "easyedapro") (part "凯华rgb键轴"))
    )
    (comp (ref "U77")
      (value "~")
      (footprint "easyedapro:凯华rgb灯")
      (libsource (lib "easyedapro") (part "凯华rgb键轴"))
    )
    (comp (ref "U78")
      (value "~")
      (footprint "easyedapro:凯华rgb灯")
      (libsource (lib "easyedapro") (part "凯华rgb键轴"))
    )
    (comp (ref "U79")
      (value "~")
      (footprint "easyedapro:凯华rgb灯")
      (libsource (lib "easyedapro") (part "凯华rgb键轴"))
    )
    (comp (ref "U80")
      (value "~")
      (footprint "easyedapro:凯华rgb灯")
      (libsource (lib "easyedapro") (part "凯华rgb键轴"))
    )
    (comp (ref "U81")
      (value "~")
      (footprint "easyedapro:凯华rgb灯")
      (libsource (lib "easyedapro") (part "凯华rgb键轴"))
    )
    (comp (ref "U82")
      (value "~")
      (footprint "easyedapro:凯华rgb灯")
      (libsource (lib "easyedapro") (part "凯华rgb键轴"))
    )
    (comp (ref "C84")
      (value "100nF")
      (footprint "easyedapro:C0805")
      (description "容值:100nF;精度:±10%;额定电压:50V;温度系数:X7R;")
      (fields
        (field (name "Manufacturer Part") "CL21B104KBCNNNC")
        (field (name "Manufacturer") "SAMSUNG(三星)")
      )
      (libsource (lib "easyedapro") (part "CL21B104KBCNNNC"))
    )
    (comp (ref "C85")
      (value "10uF")
      (footprint "easyedapro:C0805")
      (description "容值:10uF;精度:±10%;额定电压:25V;温度系数:X5R;")
      (fields
        (field (name "Manufacturer Part") "CL21A106KAYNNNE")
        (field (name "Manufacturer") "SAMSUNG(三星)")
      )
      (libsource (lib "easyedapro") (part "CL21A106KAYNNNE"))
    )
    (comp (ref "C86")
      (value "10uF")
      (footprint "easyedapro:C0805")
      (description "容值:10uF;精度:±10%;额定电压:25V;温度系数:X5R;")
      (fields
        (field (name "Manufacturer Part") "CL21A106KAYNNNE")
        (field (name "Manufacturer") "SAMSUNG(三星)")
      )
      (libsource (lib "easyedapro") (part "CL21A106KAYNNNE"))
    )
    (comp (ref "C87")
      (value "100nF")
      (footprint "easyedapro:C0805")
      (description "容值:100nF;精度:±10%;额定电压:25V;温度系数:X7R;")
      (fields
        (field (name "Manufacturer Part") "CC0805KRX7R8BB104")
        (field (name "Manufacturer") "YAGEO(国巨)")
      )
      (libsource (lib "easyedapro") (part "CC0805KRX7R8BB104"))
    )
    (comp (ref "C88")
      (value "100nF")
      (footprint "easyedapro:C0805")
      (description "容值:100nF;精度:±10%;额定电压:25V;温度系数:X7R;")
      (fields
        (field (name "Manufacturer Part") "CC0805KRX7R8BB104")
        (field (name "Manufacturer") "YAGEO(国巨)")
      )
      (libsource (lib "easyedapro") (part "CC0805KRX7R8BB104"))
    )
    (comp (ref "C93")
      (value "22pF")
      (footprint "easyedapro:C0805")
      (description "容值:22pF;精度:±5%;额定电压:50V;温度系数:C0G;")
      (fields
        (field (name "Manufacturer Part") "CL21C220JBANNNC")
        (field (name "Manufacturer") "SAMSUNG(三星)")
      )
      (libsource (lib "easyedapro") (part "CL21C220JBANNNC"))
    )
    (comp (ref "C94")
      (value "22pF")
      (footprint "easyedapro:C0805")
      (description "容值:22pF;精度:±5%;额定电压:50V;温度系数:C0G;")
      (fields
        (field (name "Manufacturer Part") "CL21C220JBANNNC")
        (field (name "Manufacturer") "SAMSUNG(三星)")
      )
      (libsource (lib "easyedapro") (part "CL21C220JBANNNC"))
    )
    (comp (ref "C95")
      (value "100nF")
      (footprint "easyedapro:C0603")
      (description "容值:100nF;精度:±20%;温度系数:X7R;")
      (fields (field (name "Manufacturer Part") "C0603C104M4RACTU") (field (name "Manufacturer") "KEMET(基美)"))
      (libsource (lib "easyedapro") (part "C0603C104M4RACTU"))
    )
    (comp (ref "C96")
      (value "100nF")
      (footprint "easyedapro:C0603")
      (description "容值:100nF;精度:±20%;温度系数:X7R;")
      (fields (field (name "Manufacturer Part") "C0603C104M4RACTU") (field (name "Manufacturer") "KEMET(基美)"))
      (libsource (lib "easyedapro") (part "C0603C104M4RACTU"))
    )
    (comp (ref "C103")
      (value "10uF")
      (footprint "easyedapro:C0805")
      (description "容值:10uF;精度:±10%;额定电压:25V;温度系数:X5R;")
      (fields
        (field (name "Manufacturer Part") "CL21A106KAYNNNE")
        (field (name "Manufacturer") "SAMSUNG(三星)")
      )
      (libsource (lib "easyedapro") (part "CL21A106KAYNNNE"))
    )
    (comp (ref "C104")
      (value "100nF")
      (footprint "easyedapro:C0805")
      (description "容值:100nF;精度:±10%;额定电压:25V;温度系数:X7R;")
      (fields
        (field (name "Manufacturer Part") "CC0805KRX7R8BB104")
        (field (name "Manufacturer") "YAGEO(国巨)")
      )
      (libsource (lib "easyedapro") (part "CC0805KRX7R8BB104"))
    )
    (comp (ref "C109")
      (value "100nF")
      (footprint "easyedapro:C0805")
      (description "容值:100nF;精度:±10%;额定电压:25V;温度系数:X7R;")
      (fields
        (field (name "Manufacturer Part") "CC0805KRX7R8BB104")
        (field (name "Manufacturer") "YAGEO(国巨)")
      )
      (libsource (lib "easyedapro") (part "CC0805KRX7R8BB104"))
    )
    (comp (ref "D86")
      (value "USBLC6-2SC6")
      (footprint "easyedapro:SOT-23-6_L2.9-W1.6-P0.95-LS2.8-BL")
      (description "极性:单向;反向截止电压(Vrwm):5.25V;钳位电压:17V;峰值脉冲电流(Ipp):5A;击穿电压:6V;")
      (fields (field (name "Manufacturer") "ST(意法半导体)"))
      (libsource (lib "easyedapro") (part "USBLC6-2SC6"))
    )
    (comp (ref "FPC1")
      (value "XW05202-040R-00")
      (footprint "easyedapro:FPC-SMD_4P-P0.50_HCTL_XW05202-040R-00")
      (description "锁定特性:翻盖式;触点类型:下接;触点数量:4P;间距:0.5mm;安装类型:卧贴;工作温度范围:-25°C~+85°C;")
      (fields (field (name "Manufacturer") "HCTL(华灿天禄)"))
      (libsource (lib "easyedapro") (part "XW05202-040R-00"))
    )
    (comp (ref "R13")
      (value "10kΩ")
      (footprint "easyedapro:R0805")
      (description "电阻类型:厚膜电阻;阻值:10kΩ;精度:±1%;功率:125mW;工作电压:150V;温度系数:±100ppm/°C;")
      (fields (field (name "Manufacturer Part") "RC0805FR-0710KL") (field (name "Manufacturer") "YAGEO(国巨)"))
      (libsource (lib "easyedapro") (part "RC0805FR-0710KL"))
    )
    (comp (ref "R15")
      (value "22Ω")
      (footprint "easyedapro:R0603")
      (description "电阻类型:厚膜电阻;阻值:22Ω;精度:±1%;功率:250mW;工作电压:150V;温度系数:±200ppm/°C;")
      (fields (field (name "Manufacturer Part") "SR0603FR-7T22RL") (field (name "Manufacturer") "YAGEO(国巨)"))
      (libsource (lib "easyedapro") (part "SR0603FR-7T22RL"))
    )
    (comp (ref "R16")
      (value "22Ω")
      (footprint "easyedapro:R0603")
      (description "电阻类型:厚膜电阻;阻值:22Ω;精度:±1%;功率:250mW;工作电压:150V;温度系数:±200ppm/°C;")
      (fields (field (name "Manufacturer Part") "SR0603FR-7T22RL") (field (name "Manufacturer") "YAGEO(国巨)"))
      (libsource (lib "easyedapro") (part "SR0603FR-7T22RL"))
    )
    (comp (ref "R17")
      (value "1.5kΩ")
      (footprint "easyedapro:R0603")
      (description "电阻类型:厚膜电阻;阻值:1.5kΩ;精度:±5%;功率:100mW;工作电压:75V;")
      (fields (field (name "Manufacturer Part") "CL0603JN1K5P") (field (name "Manufacturer") "昶龙科技"))
      (libsource (lib "easyedapro") (part "CL0603JN1K5P"))
    )
    (comp (ref "SW1")
      (value "TS-1101-C-W")
      (footprint "easyedapro:SW-SMD_L6.0-W3.3-LS8.0")
      (fields (field (name "Manufacturer") "XKB Connectivity(中国星坤)"))
      (libsource (lib "easyedapro") (part "TS-1101-C-W"))
    )
    (comp (ref "U83")
      (value "STM32F103RCT6")
      (footprint "easyedapro:LQFP-64_L10.0-W10.0-P0.50-LS12.0-BL")
      (description "CPU内核:ARM-M3;CPU最大主频:72MHz;应用领域:-;")
      (fields (field (name "Manufacturer") "ST(意法半导体)"))
      (libsource (lib "easyedapro") (part "STM32F103RCT6"))
    )
    (comp (ref "U85")
      (value "AMS1117-3.3")
      (footprint "easyedapro:SOT-223-4_L6.5-W3.5-P2.30-LS7.0-BR")
      (description "输出类型:固定;工作电压:12V;输出电压:3.3V;输出电流:1A;电源纹波抑制比(PSRR):60dB@(120Hz);输出极性:正极;")
      (fields (field (name "Manufacturer") "UMW(友台半导体)"))
      (libsource (lib "easyedapro") (part "AMS1117-3.3_C347222"))
    )
    (comp (ref "USB1")
      (value "TYPE-C 16PIN 2MD(073)")
      (footprint "easyedapro:USB-C-SMD_TYPE-C-6PIN-2MD-073")
      (description "连接器类型:Type-C;协议标准:-;公母:母;安装方式:卧贴;触点数量:16P;端口数量:1;额定电流 - 电源:3A;工作温度:-25°C~+85°C;")
      (fields (field (name "Manufacturer") "SHOU HAN(首韩)"))
      (libsource (lib "easyedapro") (part "TYPE-C 16PIN 2MD(073)"))
    )
    (comp (ref "X1")
      (value "8MHz")
      (footprint "easyedapro:CRYSTAL-SMD_4P-L3.2-W2.5-BL")
      (description "晶振类型:贴片晶振;频率:8MHz;常温频差:±10ppm;负载电容:20pF;频率稳定度:±20ppm;")
      (fields
        (field (name "Manufacturer Part") "XL2EL89CSI-KPIYLC-8M")
        (field (name "Manufacturer") "YXC(扬兴晶振)")
      )
      (libsource (lib "easyedapro") (part "XL2EL89CSI-KPIYLC-8M"))
    )
    (comp (ref "C97")
      (value "22pF")
      (footprint "easyedapro:C0805")
      (description "容值:22pF;精度:±5%;额定电压:50V;温度系数:C0G;")
      (fields
        (field (name "Manufacturer Part") "CL21C220JBANNNC")
        (field (name "Manufacturer") "SAMSUNG(三星)")
      )
      (libsource (lib "easyedapro") (part "CL21C220JBANNNC"))
    )
    (comp (ref "C98")
      (value "22pF")
      (footprint "easyedapro:C0805")
      (description "容值:22pF;精度:±5%;额定电压:50V;温度系数:C0G;")
      (fields
        (field (name "Manufacturer Part") "CL21C220JBANNNC")
        (field (name "Manufacturer") "SAMSUNG(三星)")
      )
      (libsource (lib "easyedapro") (part "CL21C220JBANNNC"))
    )
    (comp (ref "C99")
      (value "100nF")
      (footprint "easyedapro:C0805")
      (description "容值:100nF;精度:±10%;额定电压:50V;温度系数:X7R;")
      (fields
        (field (name "Manufacturer Part") "CL21B104KBCNNNC")
        (field (name "Manufacturer") "SAMSUNG(三星)")
      )
      (libsource (lib "easyedapro") (part "CL21B104KBCNNNC"))
    )
    (comp (ref "C100")
      (value "100nF")
      (footprint "easyedapro:C0603")
      (description "容值:100nF;精度:±20%;温度系数:X7R;")
      (fields (field (name "Manufacturer Part") "C0603C104M4RACTU") (field (name "Manufacturer") "KEMET(基美)"))
      (libsource (lib "easyedapro") (part "C0603C104M4RACTU"))
    )
    (comp (ref "C101")
      (value "100nF")
      (footprint "easyedapro:C0603")
      (description "容值:100nF;精度:±20%;温度系数:X7R;")
      (fields (field (name "Manufacturer Part") "C0603C104M4RACTU") (field (name "Manufacturer") "KEMET(基美)"))
      (libsource (lib "easyedapro") (part "C0603C104M4RACTU"))
    )
    (comp (ref "C102")
      (value "100nF")
      (footprint "easyedapro:C0603")
      (description "容值:100nF;精度:±20%;温度系数:X7R;")
      (fields (field (name "Manufacturer Part") "C0603C104M4RACTU") (field (name "Manufacturer") "KEMET(基美)"))
      (libsource (lib "easyedapro") (part "C0603C104M4RACTU"))
    )
    (comp (ref "C105")
      (value "10uF")
      (footprint "easyedapro:C0805")
      (description "容值:10uF;精度:±10%;额定电压:25V;温度系数:X5R;")
      (fields
        (field (name "Manufacturer Part") "CL21A106KAYNNNE")
        (field (name "Manufacturer") "SAMSUNG(三星)")
      )
      (libsource (lib "easyedapro") (part "CL21A106KAYNNNE"))
    )
    (comp (ref "C106")
      (value "10uF")
      (footprint "easyedapro:C0805")
      (description "容值:10uF;精度:±10%;额定电压:25V;温度系数:X5R;")
      (fields
        (field (name "Manufacturer Part") "CL21A106KAYNNNE")
        (field (name "Manufacturer") "SAMSUNG(三星)")
      )
      (libsource (lib "easyedapro") (part "CL21A106KAYNNNE"))
    )
    (comp (ref "C107")
      (value "100nF")
      (footprint "easyedapro:C0805")
      (description "容值:100nF;精度:±10%;额定电压:25V;温度系数:X7R;")
      (fields
        (field (name "Manufacturer Part") "CC0805KRX7R8BB104")
        (field (name "Manufacturer") "YAGEO(国巨)")
      )
      (libsource (lib "easyedapro") (part "CC0805KRX7R8BB104"))
    )
    (comp (ref "C108")
      (value "100nF")
      (footprint "easyedapro:C0805")
      (description "容值:100nF;精度:±10%;额定电压:25V;温度系数:X7R;")
      (fields
        (field (name "Manufacturer Part") "CC0805KRX7R8BB104")
        (field (name "Manufacturer") "YAGEO(国巨)")
      )
      (libsource (lib "easyedapro") (part "CC0805KRX7R8BB104"))
    )
    (comp (ref "FPC2")
      (value "XW05202-040R-00")
      (footprint "easyedapro:FPC-SMD_4P-P0.50_HCTL_XW05202-040R-00")
      (description "锁定特性:翻盖式;触点类型:下接;触点数量:4P;间距:0.5mm;安装类型:卧贴;工作温度范围:-25°C~+85°C;")
      (fields (field (name "Manufacturer") "HCTL(华灿天禄)"))
      (libsource (lib "easyedapro") (part "XW05202-040R-00"))
    )
    (comp (ref "R18")
      (value "10kΩ")
      (footprint "easyedapro:R0805")
      (description "电阻类型:厚膜电阻;阻值:10kΩ;精度:±1%;功率:125mW;工作电压:150V;温度系数:±100ppm/°C;")
      (fields (field (name "Manufacturer Part") "RC0805FR-0710KL") (field (name "Manufacturer") "YAGEO(国巨)"))
      (libsource (lib "easyedapro") (part "RC0805FR-0710KL"))
    )
    (comp (ref "SW2")
      (value "TS-1101-C-W")
      (footprint "easyedapro:SW-SMD_L6.0-W3.3-LS8.0")
      (fields (field (name "Manufacturer") "XKB Connectivity(中国星坤)"))
      (libsource (lib "easyedapro") (part "TS-1101-C-W"))
    )
    (comp (ref "U86")
      (value "STM32F103C8T6")
      (footprint "easyedapro:LQFP-48_L7.0-W7.0-P0.50-LS9.0-BL")
      (description "CPU内核:ARM-M3;CPU最大主频:72MHz;应用领域:-;")
      (fields (field (name "Manufacturer") "ST(意法半导体)"))
      (libsource (lib "easyedapro") (part "STM32F103C8T6"))
    )
    (comp (ref "U87")
      (value "AMS1117-3.3")
      (footprint "easyedapro:SOT-223-4_L6.5-W3.5-P2.30-LS7.0-BR")
      (description "输出类型:固定;工作电压:12V;输出电压:3.3V;输出电流:1A;电源纹波抑制比(PSRR):60dB@(120Hz);输出极性:正极;")
      (fields (field (name "Manufacturer") "UMW(友台半导体)"))
      (libsource (lib "easyedapro") (part "AMS1117-3.3_C347222"))
    )
    (comp (ref "X2")
      (value "8MHz")
      (footprint "easyedapro:CRYSTAL-SMD_4P-L3.2-W2.5-BL")
      (description "晶振类型:贴片晶振;频率:8MHz;常温频差:±10ppm;负载电容:20pF;频率稳定度:±20ppm;")
      (fields
        (field (name "Manufacturer Part") "XL2EL89CSI-KPIYLC-8M")
        (field (name "Manufacturer") "YXC(扬兴晶振)")
      )
      (libsource (lib "easyedapro") (part "XL2EL89CSI-KPIYLC-8M"))
    )
  )
  (nets
    (net (code "1") (name "+5V") (class "Default")
      (node (ref "C1") (pin "2") (pinfunction "2_2") (pintype "unspecified"))
      (node (ref "C10") (pin "2") (pinfunction "2_2") (pintype "unspecified"))
      (node (ref "C103") (pin "2") (pinfunction "2_2") (pintype "unspecified"))
      (node (ref "C104") (pin "2") (pinfunction "2_2") (pintype "unspecified"))
      (node (ref "C105") (pin "2") (pinfunction "2_2") (pintype "unspecified"))
      (node (ref "C107") (pin "2") (pinfunction "2_2") (pintype "unspecified"))
      (node (ref "C109") (pin "2") (pinfunction "2_2") (pintype "unspecified"))
      (node (ref "C11") (pin "2") (pinfunction "2_2") (pintype "unspecified"))
      (node (ref "C12") (pin "2") (pinfunction "2_2") (pintype "unspecified"))
      (node (ref "C13") (pin "2") (pinfunction "2_2") (pintype "unspecified"))
      (node (ref "C14") (pin "2") (pinfunction "2_2") (pintype "unspecified"))
      (node (ref "C15") (pin "2") (pinfunction "2_2") (pintype "unspecified"))
      (node (ref "C16") (pin "2") (pinfunction "2_2") (pintype "unspecified"))
      (node (ref "C17") (pin "2") (pinfunction "2_2") (pintype "unspecified"))
      (node (ref "C18") (pin "2") (pinfunction "2_2") (pintype "unspecified"))
      (node (ref "C19") (pin "2") (pinfunction "2_2") (pintype "unspecified"))
      (node (ref "C2") (pin "2") (pinfunction "2_2") (pintype "unspecified"))
      (node (ref "C20") (pin "2") (pinfunction "2_2") (pintype "unspecified"))
      (node (ref "C21") (pin "2") (pinfunction "2_2") (pintype "unspecified"))
      (node (ref "C22") (pin "2") (pinfunction "2_2") (pintype "unspecified"))
      (node (ref "C23") (pin "2") (pinfunction "2_2") (pintype "unspecified"))
      (node (ref "C24") (pin "2") (pinfunction "2_2") (pintype "unspecified"))
      (node (ref "C25") (pin "2") (pinfunction "2_2") (pintype "unspecified"))
      (node (ref "C26") (pin "2") (pinfunction "2_2") (pintype "unspecified"))
      (node (ref "C27") (pin "2") (pinfunction "2_2") (pintype "unspecified"))
      (node (ref "C28") (pin "2") (pinfunction "2_2") (pintype "unspecified"))
      (node (ref "C29") (pin "2") (pinfunction "2_2") (pintype "unspecified"))
      (node (ref "C3") (pin "2") (pinfunction "2_2") (pintype "unspecified"))
      (node (ref "C30") (pin "2") (pinfunction "2_2") (pintype "unspecified"))
      (node (ref "C31") (pin "2") (pinfunction "2_2") (pintype "unspecified"))
      (node (ref "C32") (pin "2") (pinfunction "2_2") (pintype "unspecified"))
      (node (ref "C33") (pin "2") (pinfunction "2_2") (pintype "unspecified"))
      (node (ref "C34") (pin "2") (pinfunction "2_2") (pintype "unspecified"))
      (node (ref "C35") (pin "2") (pinfunction "2_2") (pintype "unspecified"))
      (node (ref "C36") (pin "2") (pinfunction "2_2") (pintype "unspecified"))
      (node (ref "C37") (pin "2") (pinfunction "2_2") (pintype "unspecified"))
      (node (ref "C38") (pin "2") (pinfunction "2_2") (pintype "unspecified"))
      (node (ref "C39") (pin "2") (pinfunction "2_2") (pintype "unspecified"))
      (node (ref "C4") (pin "2") (pinfunction "2_2") (pintype "unspecified"))
      (node (ref "C40") (pin "2") (pinfunction "2_2") (pintype "unspecified"))
      (node (ref "C41") (pin "2") (pinfunction "2_2") (pintype "unspecified"))
      (node (ref "C42") (pin "2") (pinfunction "2_2") (pintype "unspecified"))
      (node (ref "C43") (pin "2") (pinfunction "2_2") (pintype "unspecified"))
      (node (ref "C44") (pin "2") (pinfunction "2_2") (pintype "unspecified"))
      (node (ref "C45") (pin "2") (pinfunction "2_2") (pintype "unspecified"))
      (node (ref "C46") (pin "2") (pinfunction "2_2") (pintype "unspecified"))
      (node (ref "C47") (pin "2") (pinfunction "2_2") (pintype "unspecified"))
      (node (ref "C48") (pin "2") (pinfunction "2_2") (pintype "unspecified"))
      (node (ref "C49") (pin "2") (pinfunction "2_2") (pintype "unspecified"))
      (node (ref "C5") (pin "2") (pinfunction "2_2") (pintype "unspecified"))
      (node (ref "C50") (pin "2") (pinfunction "2_2") (pintype "unspecified"))
      (node (ref "C51") (pin "2") (pinfunction "2_2") (pintype "unspecified"))
      (node (ref "C52") (pin "2") (pinfunction "2_2") (pintype "unspecified"))
      (node (ref "C53") (pin "2") (pinfunction "2_2") (pintype "unspecified"))
      (node (ref "C54") (pin "2") (pinfunction "2_2") (pintype "unspecified"))
      (node (ref "C55") (pin "2") (pinfunction "2_2") (pintype "unspecified"))
      (node (ref "C56") (pin "2") (pinfunction "2_2") (pintype "unspecified"))
      (node (ref "C57") (pin "2") (pinfunction "2_2") (pintype "unspecified"))
      (node (ref "C58") (pin "2") (pinfunction "2_2") (pintype "unspecified"))
      (node (ref "C59") (pin "2") (pinfunction "2_2") (pintype "unspecified"))
      (node (ref "C6") (pin "2") (pinfunction "2_2") (pintype "unspecified"))
      (node (ref "C60") (pin "2") (pinfunction "2_2") (pintype "unspecified"))
      (node (ref "C61") (pin "2") (pinfunction "2_2") (pintype "unspecified"))
      (node (ref "C62") (pin "2") (pinfunction "2_2") (pintype "unspecified"))
      (node (ref "C63") (pin "2") (pinfunction "2_2") (pintype "unspecified"))
      (node (ref "C64") (pin "2") (pinfunction "2_2") (pintype "unspecified"))
      (node (ref "C65") (pin "2") (pinfunction "2_2") (pintype "unspecified"))
      (node (ref "C66") (pin "2") (pinfunction "2_2") (pintype "unspecified"))
      (node (ref "C67") (pin "2") (pinfunction "2_2") (pintype "unspecified"))
      (node (ref "C68") (pin "2") (pinfunction "2_2") (pintype "unspecified"))
      (node (ref "C69") (pin "2") (pinfunction "2_2") (pintype "unspecified"))
      (node (ref "C7") (pin "2") (pinfunction "2_2") (pintype "unspecified"))
      (node (ref "C70") (pin "2") (pinfunction "2_2") (pintype "unspecified"))
      (node (ref "C71") (pin "2") (pinfunction "2_2") (pintype "unspecified"))
      (node (ref "C72") (pin "2") (pinfunction "2_2") (pintype "unspecified"))
      (node (ref "C73") (pin "2") (pinfunction "2_2") (pintype "unspecified"))
      (node (ref "C74") (pin "2") (pinfunction "2_2") (pintype "unspecified"))
      (node (ref "C75") (pin "2") (pinfunction "2_2") (pintype "unspecified"))
      (node (ref "C76") (pin "2") (pinfunction "2_2") (pintype "unspecified"))
      (node (ref "C77") (pin "2") (pinfunction "2_2") (pintype "unspecified"))
      (node (ref "C78") (pin "2") (pinfunction "2_2") (pintype "unspecified"))
      (node (ref "C79") (pin "2") (pinfunction "2_2") (pintype "unspecified"))
      (node (ref "C8") (pin "2") (pinfunction "2_2") (pintype "unspecified"))
      (node (ref "C81") (pin "2") (pinfunction "2_2") (pintype "unspecified"))
      (node (ref "C82") (pin "2") (pinfunction "2_2") (pintype "unspecified"))
      (node (ref "C83") (pin "2") (pinfunction "2_2") (pintype "unspecified"))
      (node (ref "C85") (pin "2") (pinfunction "2_2") (pintype "unspecified"))
      (node (ref "C87") (pin "2") (pinfunction "2_2") (pintype "unspecified"))
      (node (ref "C9") (pin "2") (pinfunction "2_2") (pintype "unspecified"))
      (node (ref "D86") (pin "5") (pinfunction "5_5") (pintype "input"))
      (node (ref "U1") (pin "3") (pinfunction "VDD_3") (pintype "input"))
      (node (ref "U10") (pin "3") (pinfunction "VDD_3") (pintype "input"))
      (node (ref "U11") (pin "3") (pinfunction "VDD_3") (pintype "input"))
      (node (ref "U12") (pin "3") (pinfunction "VDD_3") (pintype "input"))
      (node (ref "U13") (pin "3") (pinfunction "VDD_3") (pintype "input"))
      (node (ref "U14") (pin "3") (pinfunction "VDD_3") (pintype "input"))
      (node (ref "U15") (pin "3") (pinfunction "VDD_3") (pintype "input"))
      (node (ref "U16") (pin "3") (pinfunction "VDD_3") (pintype "input"))
      (node (ref "U17") (pin "3") (pinfunction "VDD_3") (pintype "input"))
      (node (ref "U18") (pin "3") (pinfunction "VDD_3") (pintype "input"))
      (node (ref "U19") (pin "3") (pinfunction "VDD_3") (pintype "input"))
      (node (ref "U2") (pin "3") (pinfunction "VDD_3") (pintype "input"))
      (node (ref "U20") (pin "3") (pinfunction "VDD_3") (pintype "input"))
      (node (ref "U21") (pin "3") (pinfunction "VDD_3") (pintype "input"))
      (node (ref "U22") (pin "3") (pinfunction "VDD_3") (pintype "input"))
      (node (ref "U23") (pin "3") (pinfunction "VDD_3") (pintype "input"))
      (node (ref "U24") (pin "3") (pinfunction "VDD_3") (pintype "input"))
      (node (ref "U25") (pin "3") (pinfunction "VDD_3") (pintype "input"))
      (node (ref "U26") (pin "3") (pinfunction "VDD_3") (pintype "input"))
      (node (ref "U27") (pin "3") (pinfunction "VDD_3") (pintype "input"))
      (node (ref "U28") (pin "3") (pinfunction "VDD_3") (pintype "input"))
      (node (ref "U29") (pin "3") (pinfunction "VDD_3") (pintype "input"))
      (node (ref "U3") (pin "3") (pinfunction "VDD_3") (pintype "input"))
      (node (ref "U30") (pin "3") (pinfunction "VDD_3") (pintype "input"))
      (node (ref "U31") (pin "3") (pinfunction "VDD_3") (pintype "input"))
      (node (ref "U32") (pin "3") (pinfunction "VDD_3") (pintype "input"))
      (node (ref "U33") (pin "3") (pinfunction "VDD_3") (pintype "input"))
      (node (ref "U34") (pin "3") (pinfunction "VDD_3") (pintype "input"))
      (node (ref "U35") (pin "3") (pinfunction "VDD_3") (pintype "input"))
      (node (ref "U36") (pin "3") (pinfunction "VDD_3") (pintype "input"))
      (node (ref "U37") (pin "3") (pinfunction "VDD_3") (pintype "input"))
      (node (ref "U38") (pin "3") (pinfunction "VDD_3") (pintype "input"))
      (node (ref "U39") (pin "3") (pinfunction "VDD_3") (pintype "input"))
      (node (ref "U4") (pin "3") (pinfunction "VDD_3") (pintype "input"))
      (node (ref "U40") (pin "3") (pinfunction "VDD_3") (pintype "input"))
      (node (ref "U41") (pin "3") (pinfunction "VDD_3") (pintype "input"))
      (node (ref "U42") (pin "3") (pinfunction "VDD_3") (pintype "input"))
      (node (ref "U43") (pin "3") (pinfunction "VDD_3") (pintype "input"))
      (node (ref "U44") (pin "3") (pinfunction "VDD_3") (pintype "input"))
      (node (ref "U45") (pin "3") (pinfunction "VDD_3") (pintype "input"))
      (node (ref "U46") (pin "3") (pinfunction "VDD_3") (pintype "input"))
      (node (ref "U47") (pin "3") (pinfunction "VDD_3") (pintype "input"))
      (node (ref "U48") (pin "3") (pinfunction "VDD_3") (pintype "input"))
      (node (ref "U49") (pin "3") (pinfunction "VDD_3") (pintype "input"))
      (node (ref "U5") (pin "3") (pinfunction "VDD_3") (pintype "input"))
      (node (ref "U50") (pin "3") (pinfunction "VDD_3") (pintype "input"))
      (node (ref "U51") (pin "3") (pinfunction "VDD_3") (pintype "input"))
      (node (ref "U52") (pin "3") (pinfunction "VDD_3") (pintype "input"))
      (node (ref "U53") (pin "3") (pinfunction "VDD_3") (pintype "input"))
      (node (ref "U54") (pin "3") (pinfunction "VDD_3") (pintype "input"))
      (node (ref "U55") (pin "3") (pinfunction "VDD_3") (pintype "input"))
      (node (ref "U56") (pin "3") (pinfunction "VDD_3") (pintype "input"))
      (node (ref "U57") (pin "3") (pinfunction "VDD_3") (pintype "input"))
      (node (ref "U58") (pin "3") (pinfunction "VDD_3") (pintype "input"))
      (node (ref "U59") (pin "3") (pinfunction "VDD_3") (pintype "input"))
      (node (ref "U6") (pin "3") (pinfunction "VDD_3") (pintype "input"))
      (node (ref "U60") (pin "3") (pinfunction "VDD_3") (pintype "input"))
      (node (ref "U61") (pin "3") (pinfunction "VDD_3") (pintype "input"))
      (node (ref "U62") (pin "3") (pinfunction "VDD_3") (pintype "input"))
      (node (ref "U63") (pin "3") (pinfunction "VDD_3") (pintype "input"))
      (node (ref "U64") (pin "3") (pinfunction "VDD_3") (pintype "input"))
      (node (ref "U65") (pin "3") (pinfunction "VDD_3") (pintype "input"))
      (node (ref "U66") (pin "3") (pinfunction "VDD_3") (pintype "input"))
      (node (ref "U67") (pin "3") (pinfunction "VDD_3") (pintype "input"))
      (node (ref "U68") (pin "3") (pinfunction "VDD_3") (pintype "input"))
      (node (ref "U69") (pin "3") (pinfunction "VDD_3") (pintype "input"))
      (node (ref "U7") (pin "3") (pinfunction "VDD_3") (pintype "input"))
      (node (ref "U70") (pin "3") (pinfunction "VDD_3") (pintype "input"))
      (node (ref "U71") (pin "3") (pinfunction "VDD_3") (pintype "input"))
      (node (ref "U72") (pin "3") (pinfunction "VDD_3") (pintype "input"))
      (node (ref "U73") (pin "3") (pinfunction "VDD_3") (pintype "input"))
      (node (ref "U74") (pin "3") (pinfunction "VDD_3") (pintype "input"))
      (node (ref "U75") (pin "3") (pinfunction "VDD_3") (pintype "input"))
      (node (ref "U76") (pin "3") (pinfunction "VDD_3") (pintype "input"))
      (node (ref "U77") (pin "3") (pinfunction "VDD_3") (pintype "input"))
      (node (ref "U78") (pin "3") (pinfunction "VDD_3") (pintype "input"))
      (node (ref "U79") (pin "3") (pinfunction "VDD_3") (pintype "input"))
      (node (ref "U8") (pin "3") (pinfunction "VDD_3") (pintype "input"))
      (node (ref "U80") (pin "3") (pinfunction "VDD_3") (pintype "input"))
      (node (ref "U81") (pin "3") (pinfunction "VDD_3") (pintype "input"))
      (node (ref "U82") (pin "3") (pinfunction "VDD_3") (pintype "input"))
      (node (ref "U85") (pin "3") (pinfunction "VIN_3") (pintype "unspecified"))
      (node (ref "U87") (pin "3") (pinfunction "VIN_3") (pintype "unspecified"))
      (node (ref "U9") (pin "3") (pinfunction "VDD_3") (pintype "input"))
      (node (ref "USB1") (pin "11") (pinfunction "VBUS_11") (pintype "unspecified"))
      (node (ref "USB1") (pin "2") (pinfunction "VBUS_2") (pintype "unspecified"))
    )
    (net (code "2") (name "3V3_1") (class "Default")
      (node (ref "C86") (pin "2") (pinfunction "2_2") (pintype "unspecified"))
      (node (ref "C88") (pin "2") (pinfunction "2_2") (pintype "unspecified"))
      (node (ref "C95") (pin "1") (pinfunction "1_1") (pintype "unspecified"))
      (node (ref "C96") (pin "1") (pinfunction "1_1") (pintype "unspecified"))
      (node (ref "FPC1") (pin "1") (pinfunction "1_1") (pintype "unspecified"))
      (node (ref "R13") (pin "2") (pinfunction "2_2") (pintype "input"))
      (node (ref "R17") (pin "2") (pinfunction "2_2") (pintype "unspecified"))
      (node (ref "U83") (pin "13") (pinfunction "VDDA_13") (pintype "unspecified"))
      (node (ref "U83") (pin "19") (pinfunction "VDD_4_19") (pintype "unspecified"))
      (node (ref "U83") (pin "32") (pinfunction "VDD_1_32") (pintype "unspecified"))
      (node (ref "U83") (pin "48") (pinfunction "VDD_2_48") (pintype "unspecified"))
      (node (ref "U83") (pin "64") (pinfunction "VDD_3_64") (pintype "unspecified"))
      (node (ref "U85") (pin "2") (pinfunction "VOUT(TAB)_2") (pintype "unspecified"))
      (node (ref "U85") (pin "4") (pinfunction "TAB_4") (pintype "unspecified"))
    )
    (net (code "3") (name "3V3_2") (class "Default")
      (node (ref "C100") (pin "1") (pinfunction "1_1") (pintype "unspecified"))
      (node (ref "C101") (pin "1") (pinfunction "1_1") (pintype "unspecified"))
      (node (ref "C102") (pin "1") (pinfunction "1_1") (pintype "unspecified"))
      (node (ref "C106") (pin "2") (pinfunction "2_2") (pintype "unspecified"))
      (node (ref "C108") (pin "2") (pinfunction "2_2") (pintype "unspecified"))
      (node (ref "FPC2") (pin "1") (pinfunction "1_1") (pintype "unspecified"))
      (node (ref "R18") (pin "2") (pinfunction "2_2") (pintype "input"))
      (node (ref "U86") (pin "24") (pinfunction "VDD_1_24") (pintype "unspecified"))
      (node (ref "U86") (pin "36") (pinfunction "VDD_2_36") (pintype "unspecified"))
      (node (ref "U86") (pin "48") (pinfunction "VDD_3_48") (pintype "unspecified"))
      (node (ref "U86") (pin "9") (pinfunction "VDDA_9") (pintype "unspecified"))
      (node (ref "U87") (pin "2") (pinfunction "VOUT(TAB)_2") (pintype "unspecified"))
      (node (ref "U87") (pin "4") (pinfunction "TAB_4") (pintype "unspecified"))
    )
    (net (code "4") (name "COL1") (class "Default")
      (node (ref "D1") (pin "1") (pinfunction "A_1") (pintype "unspecified"))
      (node (ref "D15") (pin "1") (pinfunction "A_1") (pintype "unspecified"))
      (node (ref "D16") (pin "1") (pinfunction "A_1") (pintype "unspecified"))
      (node (ref "D17") (pin "1") (pinfunction "A_1") (pintype "unspecified"))
      (node (ref "D18") (pin "1") (pinfunction "A_1") (pintype "unspecified"))
      (node (ref "U83") (pin "14") (pinfunction "PA0-WKUP_14") (pintype "unspecified"))
    )
    (net (code "5") (name "COL2") (class "Default")
      (node (ref "D19") (pin "1") (pinfunction "A_1") (pintype "unspecified"))
      (node (ref "D20") (pin "1") (pinfunction "A_1") (pintype "unspecified"))
      (node (ref "D21") (pin "1") (pinfunction "A_1") (pintype "unspecified"))
      (node (ref "U83") (pin "15") (pinfunction "PA1_15") (pintype "unspecified"))
    )
    (net (code "6") (name "COL3") (class "Default")
      (node (ref "D2") (pin "1") (pinfunction "A_1") (pintype "unspecified"))
      (node (ref "D22") (pin "1") (pinfunction "A_1") (pintype "unspecified"))
      (node (ref "D23") (pin "1") (pinfunction "A_1") (pintype "unspecified"))
      (node (ref "D24") (pin "1") (pinfunction "A_1") (pintype "unspecified"))
      (node (ref "D25") (pin "1") (pinfunction "A_1") (pintype "unspecified"))
      (node (ref "U83") (pin "16") (pinfunction "PA2_16") (pintype "unspecified"))
    )
    (net (code "7") (name "COL4") (class "Default")
      (node (ref "D26") (pin "1") (pinfunction "A_1") (pintype "unspecified"))
      (node (ref "D27") (pin "1") (pinfunction "A_1") (pintype "unspecified"))
      (node (ref "D28") (pin "1") (pinfunction "A_1") (pintype "unspecified"))
      (node (ref "D29") (pin "1") (pinfunction "A_1") (pintype "unspecified"))
      (node (ref "D3") (pin "1") (pinfunction "A_1") (pintype "unspecified"))
      (node (ref "D30") (pin "1") (pinfunction "A_1") (pintype "unspecified"))
      (node (ref "U83") (pin "17") (pinfunction "PA3_17") (pintype "unspecified"))
    )
    (net (code "8") (name "COL5") (class "Default")
      (node (ref "D31") (pin "1") (pinfunction "A_1") (pintype "unspecified"))
      (node (ref "D32") (pin "1") (pinfunction "A_1") (pintype "unspecified"))
      (node (ref "D33") (pin "1") (pinfunction "A_1") (pintype "unspecified"))
      (node (ref "D34") (pin "1") (pinfunction "A_1") (pintype "unspecified"))
      (node (ref "D4") (pin "1") (pinfunction "A_1") (pintype "unspecified"))
      (node (ref "U83") (pin "20") (pinfunction "PA4_20") (pintype "unspecified"))
    )
    (net (code "9") (name "COL6") (class "Default")
      (node (ref "D35") (pin "1") (pinfunction "A_1") (pintype "unspecified"))
      (node (ref "D36") (pin "1") (pinfunction "A_1") (pintype "unspecified"))
      (node (ref "D37") (pin "1") (pinfunction "A_1") (pintype "unspecified"))
      (node (ref "D38") (pin "1") (pinfunction "A_1") (pintype "unspecified"))
      (node (ref "D5") (pin "1") (pinfunction "A_1") (pintype "unspecified"))
      (node (ref "U83") (pin "21") (pinfunction "PA5_21") (pintype "unspecified"))
    )
    (net (code "10") (name "COL7") (class "Default")
      (node (ref "D39") (pin "1") (pinfunction "A_1") (pintype "unspecified"))
      (node (ref "D40") (pin "1") (pinfunction "A_1") (pintype "unspecified"))
      (node (ref "D41") (pin "1") (pinfunction "A_1") (pintype "unspecified"))
      (node (ref "D42") (pin "1") (pinfunction "A_1") (pintype "unspecified"))
      (node (ref "D43") (pin "1") (pinfunction "A_1") (pintype "unspecified"))
      (node (ref "U83") (pin "22") (pinfunction "PA6_22") (pintype "unspecified"))
    )
    (net (code "11") (name "COL8") (class "Default")
      (node (ref "D44") (pin "1") (pinfunction "A_1") (pintype "unspecified"))
      (node (ref "D45") (pin "1") (pinfunction "A_1") (pintype "unspecified"))
      (node (ref "D46") (pin "1") (pinfunction "A_1") (pintype "unspecified"))
      (node (ref "D47") (pin "1") (pinfunction "A_1") (pintype "unspecified"))
      (node (ref "D6") (pin "1") (pinfunction "A_1") (pintype "unspecified"))
      (node (ref "U83") (pin "23") (pinfunction "PA7_23") (pintype "unspecified"))
    )
    (net (code "12") (name "COL9") (class "Default")
      (node (ref "D48") (pin "1") (pinfunction "A_1") (pintype "unspecified"))
      (node (ref "D49") (pin "1") (pinfunction "A_1") (pintype "unspecified"))
      (node (ref "D50") (pin "1") (pinfunction "A_1") (pintype "unspecified"))
      (node (ref "D51") (pin "1") (pinfunction "A_1") (pintype "unspecified"))
      (node (ref "D7") (pin "1") (pinfunction "A_1") (pintype "unspecified"))
      (node (ref "U83") (pin "39") (pinfunction "PC8_39") (pintype "unspecified"))
    )
    (net (code "13") (name "COL10") (class "Default")
      (node (ref "D52") (pin "1") (pinfunction "A_1") (pintype "unspecified"))
      (node (ref "D53") (pin "1") (pinfunction "A_1") (pintype "unspecified"))
      (node (ref "D54") (pin "1") (pinfunction "A_1") (pintype "unspecified"))
      (node (ref "D55") (pin "1") (pinfunction "A_1") (pintype "unspecified"))
      (node (ref "D8") (pin "1") (pinfunction "A_1") (pintype "unspecified"))
      (node (ref "U83") (pin "40") (pinfunction "PC9_40") (pintype "unspecified"))
    )
    (net (code "14") (name "COL11") (class "Default")
      (node (ref "D56") (pin "1") (pinfunction "A_1") (pintype "unspecified"))
      (node (ref "D57") (pin "1") (pinfunction "A_1") (pintype "unspecified"))
      (node (ref "D58") (pin "1") (pinfunction "A_1") (pintype "unspecified"))
      (node (ref "D59") (pin "1") (pinfunction "A_1") (pintype "unspecified"))
      (node (ref "D60") (pin "1") (pinfunction "A_1") (pintype "unspecified"))
      (node (ref "D9") (pin "1") (pinfunction "A_1") (pintype "unspecified"))
      (node (ref "U83") (pin "51") (pinfunction "PC10_51") (pintype "unspecified"))
    )
    (net (code "15") (name "COL12") (class "Default")
      (node (ref "D10") (pin "1") (pinfunction "A_1") (pintype "unspecified"))
      (node (ref "D61") (pin "1") (pinfunction "A_1") (pintype "unspecified"))
      (node (ref "D62") (pin "1") (pinfunction "A_1") (pintype "unspecified"))
      (node (ref "D63") (pin "1") (pinfunction "A_1") (pintype "unspecified"))
      (node (ref "D65") (pin "1") (pinfunction "A_1") (pintype "unspecified"))
      (node (ref "D66") (pin "1") (pinfunction "A_1") (pintype "unspecified"))
      (node (ref "U83") (pin "52") (pinfunction "PC11_52") (pintype "unspecified"))
    )
    (net (code "16") (name "COL13") (class "Default")
      (node (ref "D11") (pin "1") (pinfunction "A_1") (pintype "unspecified"))
      (node (ref "D67") (pin "1") (pinfunction "A_1") (pintype "unspecified"))
      (node (ref "D68") (pin "1") (pinfunction "A_1") (pintype "unspecified"))
      (node (ref "D69") (pin "1") (pinfunction "A_1") (pintype "unspecified"))
      (node (ref "D70") (pin "1") (pinfunction "A_1") (pintype "unspecified"))
      (node (ref "U83") (pin "53") (pinfunction "PC12_53") (pintype "unspecified"))
    )
    (net (code "17") (name "COL14") (class "Default")
      (node (ref "D12") (pin "1") (pinfunction "A_1") (pintype "unspecified"))
      (node (ref "D71") (pin "1") (pinfunction "A_1") (pintype "unspecified"))
      (node (ref "D72") (pin "1") (pinfunction "A_1") (pintype "unspecified"))
      (node (ref "D73") (pin "1") (pinfunction "A_1") (pintype "unspecified"))
      (node (ref "D74") (pin "1") (pinfunction "A_1") (pintype "unspecified"))
      (node (ref "U83") (pin "34") (pinfunction "PB13_34") (pintype "unspecified"))
    )
    (net (code "18") (name "COL15") (class "Default")
      (node (ref "D13") (pin "1") (pinfunction "A_1") (pintype "unspecified"))
      (node (ref "D75") (pin "1") (pinfunction "A_1") (pintype "unspecified"))
      (node (ref "D76") (pin "1") (pinfunction "A_1") (pintype "unspecified"))
      (node (ref "D77") (pin "1") (pinfunction "A_1") (pintype "unspecified"))
      (node (ref "D78") (pin "1") (pinfunction "A_1") (pintype "unspecified"))
      (node (ref "U83") (pin "35") (pinfunction "PB14_35") (pintype "unspecified"))
    )
    (net (code "19") (name "COL16") (class "Default")
      (node (ref "D14") (pin "1") (pinfunction "A_1") (pintype "unspecified"))
      (node (ref "D79") (pin "1") (pinfunction "A_1") (pintype "unspecified"))
      (node (ref "D80") (pin "1") (pinfunction "A_1") (pintype "unspecified"))
      (node (ref "D81") (pin "1") (pinfunction "A_1") (pintype "unspecified"))
      (node (ref "D82") (pin "1") (pinfunction "A_1") (pintype "unspecified"))
      (node (ref "D83") (pin "1") (pinfunction "A_1") (pintype "unspecified"))
      (node (ref "U83") (pin "36") (pinfunction "PB15_36") (pintype "unspecified"))
    )
    (net (code "20") (name "DN_IN") (class "Default")
      (node (ref "D86") (pin "1") (pinfunction "1_1") (pintype "input"))
      (node (ref "USB1") (pin "5") (pinfunction "DN2_5") (pintype "unspecified"))
      (node (ref "USB1") (pin "7") (pinfunction "DN1_7") (pintype "unspecified"))
    )
    (net (code "21") (name "DN_OUT") (class "Default")
      (node (ref "D86") (pin "6") (pinfunction "6_6") (pintype "input"))
      (node (ref "R15") (pin "1") (pinfunction "1_1") (pintype "unspecified"))
    )
    (net (code "22") (name "DP_IN") (class "Default")
      (node (ref "D86") (pin "3") (pinfunction "3_3") (pintype "input"))
      (node (ref "USB1") (pin "6") (pinfunction "DP1_6") (pintype "unspecified"))
      (node (ref "USB1") (pin "8") (pinfunction "DP2_8") (pintype "unspecified"))
    )
    (net (code "23") (name "DP_OUT") (class "Default")
      (node (ref "D86") (pin "4") (pinfunction "4_4") (pintype "input"))
      (node (ref "R16") (pin "1") (pinfunction "1_1") (pintype "unspecified"))
    )
    (net (code "24") (name "GND") (class "Default")
      (node (ref "C1") (pin "1") (pinfunction "1_1") (pintype "unspecified"))
      (node (ref "C10") (pin "1") (pinfunction "1_1") (pintype "unspecified"))
      (node (ref "C100") (pin "2") (pinfunction "2_2") (pintype "unspecified"))
      (node (ref "C101") (pin "2") (pinfunction "2_2") (pintype "unspecified"))
      (node (ref "C102") (pin "2") (pinfunction "2_2") (pintype "unspecified"))
      (node (ref "C103") (pin "1") (pinfunction "1_1") (pintype "unspecified"))
      (node (ref "C104") (pin "1") (pinfunction "1_1") (pintype "unspecified"))
      (node (ref "C105") (pin "1") (pinfunction "1_1") (pintype "unspecified"))
      (node (ref "C106") (pin "1") (pinfunction "1_1") (pintype "unspecified"))
      (node (ref "C107") (pin "1") (pinfunction "1_1") (pintype "unspecified"))
      (node (ref "C108") (pin "1") (pinfunction "1_1") (pintype "unspecified"))
      (node (ref "C109") (pin "1") (pinfunction "1_1") (pintype "unspecified"))
      (node (ref "C11") (pin "1") (pinfunction "1_1") (pintype "unspecified"))
      (node (ref "C12") (pin "1") (pinfunction "1_1") (pintype "unspecified"))
      (node (ref "C13") (pin "1") (pinfunction "1_1") (pintype "unspecified"))
      (node (ref "C14") (pin "1") (pinfunction "1_1") (pintype "unspecified"))
      (node (ref "C15") (pin "1") (pinfunction "1_1") (pintype "unspecified"))
      (node (ref "C16") (pin "1") (pinfunction "1_1") (pintype "unspecified"))
      (node (ref "C17") (pin "1") (pinfunction "1_1") (pintype "unspecified"))
      (node (ref "C18") (pin "1") (pinfunction "1_1") (pintype "unspecified"))
      (node (ref "C19") (pin "1") (pinfunction "1_1") (pintype "unspecified"))
      (node (ref "C2") (pin "1") (pinfunction "1_1") (pintype "unspecified"))
      (node (ref "C20") (pin "1") (pinfunction "1_1") (pintype "unspecified"))
      (node (ref "C21") (pin "1") (pinfunction "1_1") (pintype "unspecified"))
      (node (ref "C22") (pin "1") (pinfunction "1_1") (pintype "unspecified"))
      (node (ref "C23") (pin "1") (pinfunction "1_1") (pintype "unspecified"))
      (node (ref "C24") (pin "1") (pinfunction "1_1") (pintype "unspecified"))
      (node (ref "C25") (pin "1") (pinfunction "1_1") (pintype "unspecified"))
      (node (ref "C26") (pin "1") (pinfunction "1_1") (pintype "unspecified"))
      (node (ref "C27") (pin "1") (pinfunction "1_1") (pintype "unspecified"))
      (node (ref "C28") (pin "1") (pinfunction "1_1") (pintype "unspecified"))
      (node (ref "C29") (pin "1") (pinfunction "1_1") (pintype "unspecified"))
      (node (ref "C3") (pin "1") (pinfunction "1_1") (pintype "unspecified"))
      (node (ref "C30") (pin "1") (pinfunction "1_1") (pintype "unspecified"))
      (node (ref "C31") (pin "1") (pinfunction "1_1") (pintype "unspecified"))
      (node (ref "C32") (pin "1") (pinfunction "1_1") (pintype "unspecified"))
      (node (ref "C33") (pin "1") (pinfunction "1_1") (pintype "unspecified"))
      (node (ref "C34") (pin "1") (pinfunction "1_1") (pintype "unspecified"))
      (node (ref "C35") (pin "1") (pinfunction "1_1") (pintype "unspecified"))
      (node (ref "C36") (pin "1") (pinfunction "1_1") (pintype "unspecified"))
      (node (ref "C37") (pin "1") (pinfunction "1_1") (pintype "unspecified"))
      (node (ref "C38") (pin "1") (pinfunction "1_1") (pintype "unspecified"))
      (node (ref "C39") (pin "1") (pinfunction "1_1") (pintype "unspecified"))
      (node (ref "C4") (pin "1") (pinfunction "1_1") (pintype "unspecified"))
      (node (ref "C40") (pin "1") (pinfunction "1_1") (pintype "unspecified"))
      (node (ref "C41") (pin "1") (pinfunction "1_1") (pintype "unspecified"))
      (node (ref "C42") (pin "1") (pinfunction "1_1") (pintype "unspecified"))
      (node (ref "C43") (pin "1") (pinfunction "1_1") (pintype "unspecified"))
      (node (ref "C44") (pin "1") (pinfunction "1_1") (pintype "unspecified"))
      (node (ref "C45") (pin "1") (pinfunction "1_1") (pintype "unspecified"))
      (node (ref "C46") (pin "1") (pinfunction "1_1") (pintype "unspecified"))
      (node (ref "C47") (pin "1") (pinfunction "1_1") (pintype "unspecified"))
      (node (ref "C48") (pin "1") (pinfunction "1_1") (pintype "unspecified"))
      (node (ref "C49") (pin "1") (pinfunction "1_1") (pintype "unspecified"))
      (node (ref "C5") (pin "1") (pinfunction "1_1") (pintype "unspecified"))
      (node (ref "C50") (pin "1") (pinfunction "1_1") (pintype "unspecified"))
      (node (ref "C51") (pin "1") (pinfunction "1_1") (pintype "unspecified"))
      (node (ref "C52") (pin "1") (pinfunction "1_1") (pintype "unspecified"))
      (node (ref "C53") (pin "1") (pinfunction "1_1") (pintype "unspecified"))
      (node (ref "C54") (pin "1") (pinfunction "1_1") (pintype "unspecified"))
      (node (ref "C55") (pin "1") (pinfunction "1_1") (pintype "unspecified"))
      (node (ref "C56") (pin "1") (pinfunction "1_1") (pintype "unspecified"))
      (node (ref "C57") (pin "1") (pinfunction "1_1") (pintype "unspecified"))
      (node (ref "C58") (pin "1") (pinfunction "1_1") (pintype "unspecified"))
      (node (ref "C59") (pin "1") (pinfunction "1_1") (pintype "unspecified"))
      (node (ref "C6") (pin "1") (pinfunction "1_1") (pintype "unspecified"))
      (node (ref "C60") (pin "1") (pinfunction "1_1") (pintype "unspecified"))
      (node (ref "C61") (pin "1") (pinfunction "1_1") (pintype "unspecified"))
      (node (ref "C62") (pin "1") (pinfunction "1_1") (pintype "unspecified"))
      (node (ref "C63") (pin "1") (pinfunction "1_1") (pintype "unspecified"))
      (node (ref "C64") (pin "1") (pinfunction "1_1") (pintype "unspecified"))
      (node (ref "C65") (pin "1") (pinfunction "1_1") (pintype "unspecified"))
      (node (ref "C66") (pin "1") (pinfunction "1_1") (pintype "unspecified"))
      (node (ref "C67") (pin "1") (pinfunction "1_1") (pintype "unspecified"))
      (node (ref "C68") (pin "1") (pinfunction "1_1") (pintype "unspecified"))
      (node (ref "C69") (pin "1") (pinfunction "1_1") (pintype "unspecified"))
      (node (ref "C7") (pin "1") (pinfunction "1_1") (pintype "unspecified"))
      (node (ref "C70") (pin "1") (pinfunction "1_1") (pintype "unspecified"))
      (node (ref "C71") (pin "1") (pinfunction "1_1") (pintype "unspecified"))
      (node (ref "C72") (pin "1") (pinfunction "1_1") (pintype "unspecified"))
      (node (ref "C73") (pin "1") (pinfunction "1_1") (pintype "unspecified"))
      (node (ref "C74") (pin "1") (pinfunction "1_1") (pintype "unspecified"))
      (node (ref "C75") (pin "1") (pinfunction "1_1") (pintype "unspecified"))
      (node (ref "C76") (pin "1") (pinfunction "1_1") (pintype "unspecified"))
      (node (ref "C77") (pin "1") (pinfunction "1_1") (pintype "unspecified"))
      (node (ref "C78") (pin "1") (pinfunction "1_1") (pintype "unspecified"))
      (node (ref "C79") (pin "1") (pinfunction "1_1") (pintype "unspecified"))
      (node (ref "C8") (pin "1") (pinfunction "1_1") (pintype "unspecified"))
      (node (ref "C81") (pin "1") (pinfunction "1_1") (pintype "unspecified"))
      (node (ref "C82") (pin "1") (pinfunction "1_1") (pintype "unspecified"))
      (node (ref "C83") (pin "1") (pinfunction "1_1") (pintype "unspecified"))
      (node (ref "C84") (pin "1") (pinfunction "1_1") (pintype "input"))
      (node (ref "C85") (pin "1") (pinfunction "1_1") (pintype "unspecified"))
      (node (ref "C86") (pin "1") (pinfunction "1_1") (pintype "unspecified"))
      (node (ref "C87") (pin "1") (pinfunction "1_1") (pintype "unspecified"))
      (node (ref "C88") (pin "1") (pinfunction "1_1") (pintype "unspecified"))
      (node (ref "C9") (pin "1") (pinfunction "1_1") (pintype "unspecified"))
      (node (ref "C93") (pin "1") (pinfunction "1_1") (pintype "input"))
      (node (ref "C94") (pin "1") (pinfunction "1_1") (pintype "input"))
      (node (ref "C95") (pin "2") (pinfunction "2_2") (pintype "unspecified"))
      (node (ref "C96") (pin "2") (pinfunction "2_2") (pintype "unspecified"))
      (node (ref "C97") (pin "1") (pinfunction "1_1") (pintype "input"))
      (node (ref "C98") (pin "1") (pinfunction "1_1") (pintype "input"))
      (node (ref "C99") (pin "1") (pinfunction "1_1") (pintype "input"))
      (node (ref "D86") (pin "2") (pinfunction "2_2") (pintype "input"))
      (node (ref "FPC1") (pin "3") (pinfunction "3_3") (pintype "unspecified"))
      (node (ref "FPC2") (pin "3") (pinfunction "3_3") (pintype "unspecified"))
      (node (ref "R10") (pin "2") (pinfunction "2_2") (pintype "unspecified"))
      (node (ref "R11") (pin "2") (pinfunction "2_2") (pintype "unspecified"))
      (node (ref "R12") (pin "2") (pinfunction "2_2") (pintype "unspecified"))
      (node (ref "R7") (pin "2") (pinfunction "2_2") (pintype "unspecified"))
      (node (ref "R8") (pin "2") (pinfunction "2_2") (pintype "unspecified"))
      (node (ref "R9") (pin "2") (pinfunction "2_2") (pintype "unspecified"))
      (node (ref "SW1") (pin "1") (pinfunction "1_1") (pintype "unspecified"))
      (node (ref "SW2") (pin "1") (pinfunction "1_1") (pintype "unspecified"))
      (node (ref "U1") (pin "6") (pinfunction "GND_6") (pintype "input"))
      (node (ref "U10") (pin "6") (pinfunction "GND_6") (pintype "input"))
      (node (ref "U11") (pin "6") (pinfunction "GND_6") (pintype "input"))
      (node (ref "U12") (pin "6") (pinfunction "GND_6") (pintype "input"))
      (node (ref "U13") (pin "6") (pinfunction "GND_6") (pintype "input"))
      (node (ref "U14") (pin "6") (pinfunction "GND_6") (pintype "input"))
      (node (ref "U15") (pin "6") (pinfunction "GND_6") (pintype "input"))
      (node (ref "U16") (pin "6") (pinfunction "GND_6") (pintype "input"))
      (node (ref "U17") (pin "6") (pinfunction "GND_6") (pintype "input"))
      (node (ref "U18") (pin "6") (pinfunction "GND_6") (pintype "input"))
      (node (ref "U19") (pin "6") (pinfunction "GND_6") (pintype "input"))
      (node (ref "U2") (pin "6") (pinfunction "GND_6") (pintype "input"))
      (node (ref "U20") (pin "6") (pinfunction "GND_6") (pintype "input"))
      (node (ref "U21") (pin "6") (pinfunction "GND_6") (pintype "input"))
      (node (ref "U22") (pin "6") (pinfunction "GND_6") (pintype "input"))
      (node (ref "U23") (pin "6") (pinfunction "GND_6") (pintype "input"))
      (node (ref "U24") (pin "6") (pinfunction "GND_6") (pintype "input"))
      (node (ref "U25") (pin "6") (pinfunction "GND_6") (pintype "input"))
      (node (ref "U26") (pin "6") (pinfunction "GND_6") (pintype "input"))
      (node (ref "U27") (pin "6") (pinfunction "GND_6") (pintype "input"))
      (node (ref "U28") (pin "6") (pinfunction "GND_6") (pintype "input"))
      (node (ref "U29") (pin "6") (pinfunction "GND_6") (pintype "input"))
      (node (ref "U3") (pin "6") (pinfunction "GND_6") (pintype "input"))
      (node (ref "U30") (pin "6") (pinfunction "GND_6") (pintype "input"))
      (node (ref "U31") (pin "6") (pinfunction "GND_6") (pintype "input"))
      (node (ref "U32") (pin "6") (pinfunction "GND_6") (pintype "input"))
      (node (ref "U33") (pin "6") (pinfunction "GND_6") (pintype "input"))
      (node (ref "U34") (pin "6") (pinfunction "GND_6") (pintype "input"))
      (node (ref "U35") (pin "6") (pinfunction "GND_6") (pintype "input"))
      (node (ref "U36") (pin "6") (pinfunction "GND_6") (pintype "input"))
      (node (ref "U37") (pin "6") (pinfunction "GND_6") (pintype "input"))
      (node (ref "U38") (pin "6") (pinfunction "GND_6") (pintype "input"))
      (node (ref "U39") (pin "6") (pinfunction "GND_6") (pintype "input"))
      (node (ref "U4") (pin "6") (pinfunction "GND_6") (pintype "input"))
      (node (ref "U40") (pin "6") (pinfunction "GND_6") (pintype "input"))
      (node (ref "U41") (pin "6") (pinfunction "GND_6") (pintype "input"))
      (node (ref "U42") (pin "6") (pinfunction "GND_6") (pintype "input"))
      (node (ref "U43") (pin "6") (pinfunction "GND_6") (pintype "input"))
      (node (ref "U44") (pin "6") (pinfunction "GND_6") (pintype "input"))
      (node (ref "U45") (pin "6") (pinfunction "GND_6") (pintype "input"))
      (node (ref "U46") (pin "6") (pinfunction "GND_6") (pintype "input"))
      (node (ref "U47") (pin "6") (pinfunction "GND_6") (pintype "input"))
      (node (ref "U48") (pin "6") (pinfunction "GND_6") (pintype "input"))
      (node (ref "U49") (pin "6") (pinfunction "GND_6") (pintype "input"))
      (node (ref "U5") (pin "6") (pinfunction "GND_6") (pintype "input"))
      (node (ref "U50") (pin "6") (pinfunction "GND_6") (pintype "input"))
      (node (ref "U51") (pin "6") (pinfunction "GND_6") (pintype "input"))
      (node (ref "U52") (pin "6") (pinfunction "GND_6") (pintype "input"))
      (node (ref "U53") (pin "6") (pinfunction "GND_6") (pintype "input"))
      (node (ref "U54") (pin "6") (pinfunction "GND_6") (pintype "input"))
      (node (ref "U55") (pin "6") (pinfunction "GND_6") (pintype "input"))
      (node (ref "U56") (pin "6") (pinfunction "GND_6") (pintype "input"))
      (node (ref "U57") (pin "6") (pinfunction "GND_6") (pintype "input"))
      (node (ref "U58") (pin "6") (pinfunction "GND_6") (pintype "input"))
      (node (ref "U59") (pin "6") (pinfunction "GND_6") (pintype "input"))
      (node (ref "U6") (pin "6") (pinfunction "GND_6") (pintype "input"))
      (node (ref "U60") (pin "6") (pinfunction "GND_6") (pintype "input"))
      (node (ref "U61") (pin "6") (pinfunction "GND_6") (pintype "input"))
      (node (ref "U62") (pin "6") (pinfunction "GND_6") (pintype "input"))
      (node (ref "U63") (pin "6") (pinfunction "GND_6") (pintype "input"))
      (node (ref "U64") (pin "6") (pinfunction "GND_6") (pintype "input"))
      (node (ref "U65") (pin "6") (pinfunction "GND_6") (pintype "input"))
      (node (ref "U66") (pin "6") (pinfunction "GND_6") (pintype "input"))
      (node (ref "U67") (pin "6") (pinfunction "GND_6") (pintype "input"))
      (node (ref "U68") (pin "6") (pinfunction "GND_6") (pintype "input"))
      (node (ref "U69") (pin "6") (pinfunction "GND_6") (pintype "input"))
      (node (ref "U7") (pin "6") (pinfunction "GND_6") (pintype "input"))
      (node (ref "U70") (pin "6") (pinfunction "GND_6") (pintype "input"))
      (node (ref "U71") (pin "6") (pinfunction "GND_6") (pintype "input"))
      (node (ref "U72") (pin "6") (pinfunction "GND_6") (pintype "input"))
      (node (ref "U73") (pin "6") (pinfunction "GND_6") (pintype "input"))
      (node (ref "U74") (pin "6") (pinfunction "GND_6") (pintype "input"))
      (node (ref "U75") (pin "6") (pinfunction "GND_6") (pintype "input"))
      (node (ref "U76") (pin "6") (pinfunction "GND_6") (pintype "input"))
      (node (ref "U77") (pin "6") (pinfunction "GND_6") (pintype "input"))
      (node (ref "U78") (pin "6") (pinfunction "GND_6") (pintype "input"))
      (node (ref "U79") (pin "6") (pinfunction "GND_6") (pintype "input"))
      (node (ref "U8") (pin "6") (pinfunction "GND_6") (pintype "input"))
      (node (ref "U80") (pin "6") (pinfunction "GND_6") (pintype "input"))
      (node (ref "U81") (pin "6") (pinfunction "GND_6") (pintype "input"))
      (node (ref "U82") (pin "6") (pinfunction "GND_6") (pintype "input"))
      (node (ref "U83") (pin "12") (pinfunction "VSSA_12") (pintype "unspecified"))
      (node (ref "U83") (pin "18") (pinfunction "VSS_4_18") (pintype "unspecified"))
      (node (ref "U83") (pin "28") (pinfunction "PB2_28") (pintype "unspecified"))
      (node (ref "U83") (pin "31") (pinfunction "VSS_1_31") (pintype "unspecified"))
      (node (ref "U83") (pin "47") (pinfunction "VSS_2_47") (pintype "unspecified"))
      (node (ref "U83") (pin "60") (pinfunction "BOOT0_60") (pintype "unspecified"))
      (node (ref "U83") (pin "63") (pinfunction "VSS_3_63") (pintype "unspecified"))
      (node (ref "U85") (pin "1") (pinfunction "ADJ(GND)_1") (pintype "unspecified"))
      (node (ref "U86") (pin "20") (pinfunction "PB2_20") (pintype "unspecified"))
      (node (ref "U86") (pin "23") (pinfunction "VSS_1_23") (pintype "unspecified"))
      (node (ref "U86") (pin "35") (pinfunction "VSS_2_35") (pintype "unspecified"))
      (node (ref "U86") (pin "44") (pinfunction "BOOT0_44") (pintype "unspecified"))
      (node (ref "U86") (pin "47") (pinfunction "VSS_3_47") (pintype "unspecified"))
      (node (ref "U86") (pin "8") (pinfunction "VSSA_8") (pintype "unspecified"))
      (node (ref "U87") (pin "1") (pinfunction "ADJ(GND)_1") (pintype "unspecified"))
      (node (ref "U9") (pin "6") (pinfunction "GND_6") (pintype "input"))
      (node (ref "USB1") (pin "1") (pinfunction "GND_1") (pintype "unspecified"))
      (node (ref "USB1") (pin "12") (pinfunction "GND_12") (pintype "unspecified"))
      (node (ref "X1") (pin "2") (pinfunction "GND_2") (pintype "input"))
      (node (ref "X1") (pin "4") (pinfunction "GND_4") (pintype "input"))
      (node (ref "X2") (pin "2") (pinfunction "GND_2") (pintype "input"))
      (node (ref "X2") (pin "4") (pinfunction "GND_4") (pintype "input"))
    )
    (net (code "25") (name "NRST_1") (class "Default")
      (node (ref "C84") (pin "2") (pinfunction "2_2") (pintype "input"))
      (node (ref "R13") (pin "1") (pinfunction "1_1") (pintype "input"))
      (node (ref "SW1") (pin "2") (pinfunction "2_2") (pintype "unspecified"))
      (node (ref "U83") (pin "7") (pinfunction "NRST_7") (pintype "unspecified"))
    )
    (net (code "26") (name "NRST_2") (class "Default")
      (node (ref "C99") (pin "2") (pinfunction "2_2") (pintype "input"))
      (node (ref "R18") (pin "1") (pinfunction "1_1") (pintype "input"))
      (node (ref "SW2") (pin "2") (pinfunction "2_2") (pintype "unspecified"))
      (node (ref "U86") (pin "7") (pinfunction "NRST_7") (pintype "unspecified"))
    )
    (net (code "27") (name "Net-(D1-K)") (class "Default")
      (node (ref "D1") (pin "2") (pinfunction "K_2") (pintype "unspecified"))
      (node (ref "U1") (pin "2") (pinfunction "COL_2") (pintype "input"))
    )
    (net (code "28") (name "Net-(D2-K)") (class "Default")
      (node (ref "D2") (pin "2") (pinfunction "K_2") (pintype "unspecified"))
      (node (ref "U2") (pin "2") (pinfunction "COL_2") (pintype "input"))
    )
    (net (code "29") (name "Net-(D3-K)") (class "Default")
      (node (ref "D3") (pin "2") (pinfunction "K_2") (pintype "unspecified"))
      (node (ref "U3") (pin "2") (pinfunction "COL_2") (pintype "input"))
    )
    (net (code "30") (name "Net-(D4-K)") (class "Default")
      (node (ref "D4") (pin "2") (pinfunction "K_2") (pintype "unspecified"))
      (node (ref "U4") (pin "2") (pinfunction "COL_2") (pintype "input"))
    )
    (net (code "31") (name "Net-(D5-K)") (class "Default")
      (node (ref "D5") (pin "2") (pinfunction "K_2") (pintype "unspecified"))
      (node (ref "U5") (pin "2") (pinfunction "COL_2") (pintype "input"))
    )
    (net (code "32") (name "Net-(D6-K)") (class "Default")
      (node (ref "D6") (pin "2") (pinfunction "K_2") (pintype "unspecified"))
      (node (ref "U6") (pin "2") (pinfunction "COL_2") (pintype "input"))
    )
    (net (code "33") (name "Net-(D7-K)") (class "Default")
      (node (ref "D7") (pin "2") (pinfunction "K_2") (pintype "unspecified"))
      (node (ref "U7") (pin "2") (pinfunction "COL_2") (pintype "input"))
    )
    (net (code "34") (name "Net-(D8-K)") (class "Default")
      (node (ref "D8") (pin "2") (pinfunction "K_2") (pintype "unspecified"))
      (node (ref "U8") (pin "2") (pinfunction "COL_2") (pintype "input"))
    )
    (net (code "35") (name "Net-(D9-K)") (class "Default")
      (node (ref "D9") (pin "2") (pinfunction "K_2") (pintype "unspecified"))
      (node (ref "U9") (pin "2") (pinfunction "COL_2") (pintype "input"))
    )
    (net (code "36") (name "Net-(D10-K)") (class "Default")
      (node (ref "D10") (pin "2") (pinfunction "K_2") (pintype "unspecified"))
      (node (ref "U10") (pin "2") (pinfunction "COL_2") (pintype "input"))
    )
    (net (code "37") (name "Net-(D11-K)") (class "Default")
      (node (ref "D11") (pin "2") (pinfunction "K_2") (pintype "unspecified"))
      (node (ref "U11") (pin "2") (pinfunction "COL_2") (pintype "input"))
    )
    (net (code "38") (name "Net-(D12-K)") (class "Default")
      (node (ref "D12") (pin "2") (pinfunction "K_2") (pintype "unspecified"))
      (node (ref "U12") (pin "2") (pinfunction "COL_2") (pintype "input"))
    )
    (net (code "39") (name "Net-(D13-K)") (class "Default")
      (node (ref "D13") (pin "2") (pinfunction "K_2") (pintype "unspecified"))
      (node (ref "U13") (pin "2") (pinfunction "COL_2") (pintype "input"))
    )
    (net (code "40") (name "Net-(D14-K)") (class "Default")
      (node (ref "D14") (pin "2") (pinfunction "K_2") (pintype "unspecified"))
      (node (ref "U14") (pin "2") (pinfunction "COL_2") (pintype "input"))
    )
    (net (code "41") (name "Net-(D15-K)") (class "Default")
      (node (ref "D15") (pin "2") (pinfunction "K_2") (pintype "unspecified"))
      (node (ref "U15") (pin "2") (pinfunction "COL_2") (pintype "input"))
    )
    (net (code "42") (name "Net-(D16-K)") (class "Default")
      (node (ref "D16") (pin "2") (pinfunction "K_2") (pintype "unspecified"))
      (node (ref "U30") (pin "2") (pinfunction "COL_2") (pintype "input"))
    )
    (net (code "43") (name "Net-(D17-K)") (class "Default")
      (node (ref "D17") (pin "2") (pinfunction "K_2") (pintype "unspecified"))
      (node (ref "U45") (pin "2") (pinfunction "COL_2") (pintype "input"))
    )
    (net (code "44") (name "Net-(D18-K)") (class "Default")
      (node (ref "D18") (pin "2") (pinfunction "K_2") (pintype "unspecified"))
      (node (ref "U72") (pin "2") (pinfunction "COL_2") (pintype "input"))
    )
    (net (code "45") (name "Net-(D19-K)") (class "Default")
      (node (ref "D19") (pin "2") (pinfunction "K_2") (pintype "unspecified"))
      (node (ref "U16") (pin "2") (pinfunction "COL_2") (pintype "input"))
    )
    (net (code "46") (name "Net-(D20-K)") (class "Default")
      (node (ref "D20") (pin "2") (pinfunction "K_2") (pintype "unspecified"))
      (node (ref "U59") (pin "2") (pinfunction "COL_2") (pintype "input"))
    )
    (net (code "47") (name "Net-(D21-K)") (class "Default")
      (node (ref "D21") (pin "2") (pinfunction "K_2") (pintype "unspecified"))
      (node (ref "U73") (pin "2") (pinfunction "COL_2") (pintype "input"))
    )
    (net (code "48") (name "Net-(D22-K)") (class "Default")
      (node (ref "D22") (pin "2") (pinfunction "K_2") (pintype "unspecified"))
      (node (ref "U17") (pin "2") (pinfunction "COL_2") (pintype "input"))
    )
    (net (code "49") (name "Net-(D23-K)") (class "Default")
      (node (ref "D23") (pin "2") (pinfunction "K_2") (pintype "unspecified"))
      (node (ref "U31") (pin "2") (pinfunction "COL_2") (pintype "input"))
    )
    (net (code "50") (name "Net-(D24-K)") (class "Default")
      (node (ref "D24") (pin "2") (pinfunction "K_2") (pintype "unspecified"))
      (node (ref "U46") (pin "2") (pinfunction "COL_2") (pintype "input"))
    )
    (net (code "51") (name "Net-(D25-K)") (class "Default")
      (node (ref "D25") (pin "2") (pinfunction "K_2") (pintype "unspecified"))
      (node (ref "U60") (pin "2") (pinfunction "COL_2") (pintype "input"))
    )
    (net (code "52") (name "Net-(D26-K)") (class "Default")
      (node (ref "D26") (pin "2") (pinfunction "K_2") (pintype "unspecified"))
      (node (ref "U18") (pin "2") (pinfunction "COL_2") (pintype "input"))
    )
    (net (code "53") (name "Net-(D27-K)") (class "Default")
      (node (ref "D27") (pin "2") (pinfunction "K_2") (pintype "unspecified"))
      (node (ref "U32") (pin "2") (pinfunction "COL_2") (pintype "input"))
    )
    (net (code "54") (name "Net-(D28-K)") (class "Default")
      (node (ref "D28") (pin "2") (pinfunction "K_2") (pintype "unspecified"))
      (node (ref "U47") (pin "2") (pinfunction "COL_2") (pintype "input"))
    )
    (net (code "55") (name "Net-(D29-K)") (class "Default")
      (node (ref "D29") (pin "2") (pinfunction "K_2") (pintype "unspecified"))
      (node (ref "U61") (pin "2") (pinfunction "COL_2") (pintype "input"))
    )
    (net (code "56") (name "Net-(D30-K)") (class "Default")
      (node (ref "D30") (pin "2") (pinfunction "K_2") (pintype "unspecified"))
      (node (ref "U74") (pin "2") (pinfunction "COL_2") (pintype "input"))
    )
    (net (code "57") (name "Net-(D31-K)") (class "Default")
      (node (ref "D31") (pin "2") (pinfunction "K_2") (pintype "unspecified"))
      (node (ref "U19") (pin "2") (pinfunction "COL_2") (pintype "input"))
    )
    (net (code "58") (name "Net-(D32-K)") (class "Default")
      (node (ref "D32") (pin "2") (pinfunction "K_2") (pintype "unspecified"))
      (node (ref "U33") (pin "2") (pinfunction "COL_2") (pintype "input"))
    )
    (net (code "59") (name "Net-(D33-K)") (class "Default")
      (node (ref "D33") (pin "2") (pinfunction "K_2") (pintype "unspecified"))
      (node (ref "U48") (pin "2") (pinfunction "COL_2") (pintype "input"))
    )
    (net (code "60") (name "Net-(D34-K)") (class "Default")
      (node (ref "D34") (pin "2") (pinfunction "K_2") (pintype "unspecified"))
      (node (ref "U62") (pin "2") (pinfunction "COL_2") (pintype "input"))
    )
    (net (code "61") (name "Net-(D35-K)") (class "Default")
      (node (ref "D35") (pin "2") (pinfunction "K_2") (pintype "unspecified"))
      (node (ref "U20") (pin "2") (pinfunction "COL_2") (pintype "input"))
    )
    (net (code "62") (name "Net-(D36-K)") (class "Default")
      (node (ref "D36") (pin "2") (pinfunction "K_2") (pintype "unspecified"))
      (node (ref "U34") (pin "2") (pinfunction "COL_2") (pintype "input"))
    )
    (net (code "63") (name "Net-(D37-K)") (class "Default")
      (node (ref "D37") (pin "2") (pinfunction "K_2") (pintype "unspecified"))
      (node (ref "U49") (pin "2") (pinfunction "COL_2") (pintype "input"))
    )
    (net (code "64") (name "Net-(D38-K)") (class "Default")
      (node (ref "D38") (pin "2") (pinfunction "K_2") (pintype "unspecified"))
      (node (ref "U63") (pin "2") (pinfunction "COL_2") (pintype "input"))
    )
    (net (code "65") (name "Net-(D39-K)") (class "Default")
      (node (ref "D39") (pin "2") (pinfunction "K_2") (pintype "unspecified"))
      (node (ref "U21") (pin "2") (pinfunction "COL_2") (pintype "input"))
    )
    (net (code "66") (name "Net-(D40-K)") (class "Default")
      (node (ref "D40") (pin "2") (pinfunction "K_2") (pintype "unspecified"))
      (node (ref "U35") (pin "2") (pinfunction "COL_2") (pintype "input"))
    )
    (net (code "67") (name "Net-(D41-K)") (class "Default")
      (node (ref "D41") (pin "2") (pinfunction "K_2") (pintype "unspecified"))
      (node (ref "U50") (pin "2") (pinfunction "COL_2") (pintype "input"))
    )
    (net (code "68") (name "Net-(D42-K)") (class "Default")
      (node (ref "D42") (pin "2") (pinfunction "K_2") (pintype "unspecified"))
      (node (ref "U64") (pin "2") (pinfunction "COL_2") (pintype "input"))
    )
    (net (code "69") (name "Net-(D43-K)") (class "Default")
      (node (ref "D43") (pin "2") (pinfunction "K_2") (pintype "unspecified"))
      (node (ref "U75") (pin "2") (pinfunction "COL_2") (pintype "input"))
    )
    (net (code "70") (name "Net-(D44-K)") (class "Default")
      (node (ref "D44") (pin "2") (pinfunction "K_2") (pintype "unspecified"))
      (node (ref "U22") (pin "2") (pinfunction "COL_2") (pintype "input"))
    )
    (net (code "71") (name "Net-(D45-K)") (class "Default")
      (node (ref "D45") (pin "2") (pinfunction "K_2") (pintype "unspecified"))
      (node (ref "U36") (pin "2") (pinfunction "COL_2") (pintype "input"))
    )
    (net (code "72") (name "Net-(D46-K)") (class "Default")
      (node (ref "D46") (pin "2") (pinfunction "K_2") (pintype "unspecified"))
      (node (ref "U51") (pin "2") (pinfunction "COL_2") (pintype "input"))
    )
    (net (code "73") (name "Net-(D47-K)") (class "Default")
      (node (ref "D47") (pin "2") (pinfunction "K_2") (pintype "unspecified"))
      (node (ref "U65") (pin "2") (pinfunction "COL_2") (pintype "input"))
    )
    (net (code "74") (name "Net-(D48-K)") (class "Default")
      (node (ref "D48") (pin "2") (pinfunction "K_2") (pintype "unspecified"))
      (node (ref "U23") (pin "2") (pinfunction "COL_2") (pintype "input"))
    )
    (net (code "75") (name "Net-(D49-K)") (class "Default")
      (node (ref "D49") (pin "2") (pinfunction "K_2") (pintype "unspecified"))
      (node (ref "U37") (pin "2") (pinfunction "COL_2") (pintype "input"))
    )
    (net (code "76") (name "Net-(D50-K)") (class "Default")
      (node (ref "D50") (pin "2") (pinfunction "K_2") (pintype "unspecified"))
      (node (ref "U52") (pin "2") (pinfunction "COL_2") (pintype "input"))
    )
    (net (code "77") (name "Net-(D51-K)") (class "Default")
      (node (ref "D51") (pin "2") (pinfunction "K_2") (pintype "unspecified"))
      (node (ref "U66") (pin "2") (pinfunction "COL_2") (pintype "input"))
    )
    (net (code "78") (name "Net-(D52-K)") (class "Default")
      (node (ref "D52") (pin "2") (pinfunction "K_2") (pintype "unspecified"))
      (node (ref "U24") (pin "2") (pinfunction "COL_2") (pintype "input"))
    )
    (net (code "79") (name "Net-(D53-K)") (class "Default")
      (node (ref "D53") (pin "2") (pinfunction "K_2") (pintype "unspecified"))
      (node (ref "U38") (pin "2") (pinfunction "COL_2") (pintype "input"))
    )
    (net (code "80") (name "Net-(D54-K)") (class "Default")
      (node (ref "D54") (pin "2") (pinfunction "K_2") (pintype "unspecified"))
      (node (ref "U53") (pin "2") (pinfunction "COL_2") (pintype "input"))
    )
    (net (code "81") (name "Net-(D55-K)") (class "Default")
      (node (ref "D55") (pin "2") (pinfunction "K_2") (pintype "unspecified"))
      (node (ref "U67") (pin "2") (pinfunction "COL_2") (pintype "input"))
    )
    (net (code "82") (name "Net-(D56-K)") (class "Default")
      (node (ref "D56") (pin "2") (pinfunction "K_2") (pintype "unspecified"))
      (node (ref "U68") (pin "2") (pinfunction "COL_2") (pintype "input"))
    )
    (net (code "83") (name "Net-(D57-K)") (class "Default")
      (node (ref "D57") (pin "2") (pinfunction "K_2") (pintype "unspecified"))
      (node (ref "U76") (pin "2") (pinfunction "COL_2") (pintype "input"))
    )
    (net (code "84") (name "Net-(D58-K)") (class "Default")
      (node (ref "D58") (pin "2") (pinfunction "K_2") (pintype "unspecified"))
      (node (ref "U54") (pin "2") (pinfunction "COL_2") (pintype "input"))
    )
    (net (code "85") (name "Net-(D59-K)") (class "Default")
      (node (ref "D59") (pin "2") (pinfunction "K_2") (pintype "unspecified"))
      (node (ref "U39") (pin "2") (pinfunction "COL_2") (pintype "input"))
    )
    (net (code "86") (name "Net-(D60-K)") (class "Default")
      (node (ref "D60") (pin "2") (pinfunction "K_2") (pintype "unspecified"))
      (node (ref "U25") (pin "2") (pinfunction "COL_2") (pintype "input"))
    )
    (net (code "87") (name "Net-(D61-K)") (class "Default")
      (node (ref "D61") (pin "2") (pinfunction "K_2") (pintype "unspecified"))
      (node (ref "U26") (pin "2") (pinfunction "COL_2") (pintype "input"))
    )
    (net (code "88") (name "Net-(D62-K)") (class "Default")
      (node (ref "D62") (pin "2") (pinfunction "K_2") (pintype "unspecified"))
      (node (ref "U40") (pin "2") (pinfunction "COL_2") (pintype "input"))
    )
    (net (code "89") (name "Net-(D63-K)") (class "Default")
      (node (ref "D63") (pin "2") (pinfunction "K_2") (pintype "unspecified"))
      (node (ref "U55") (pin "2") (pinfunction "COL_2") (pintype "input"))
    )
    (net (code "90") (name "Net-(D65-K)") (class "Default")
      (node (ref "D65") (pin "2") (pinfunction "K_2") (pintype "unspecified"))
      (node (ref "U82") (pin "2") (pinfunction "COL_2") (pintype "input"))
    )
    (net (code "91") (name "Net-(D66-K)") (class "Default")
      (node (ref "D66") (pin "2") (pinfunction "K_2") (pintype "unspecified"))
      (node (ref "U69") (pin "2") (pinfunction "COL_2") (pintype "input"))
    )
    (net (code "92") (name "Net-(D67-K)") (class "Default")
      (node (ref "D67") (pin "2") (pinfunction "K_2") (pintype "unspecified"))
      (node (ref "U27") (pin "2") (pinfunction "COL_2") (pintype "input"))
    )
    (net (code "93") (name "Net-(D68-K)") (class "Default")
      (node (ref "D68") (pin "2") (pinfunction "K_2") (pintype "unspecified"))
      (node (ref "U41") (pin "2") (pinfunction "COL_2") (pintype "input"))
    )
    (net (code "94") (name "Net-(D69-K)") (class "Default")
      (node (ref "D69") (pin "2") (pinfunction "K_2") (pintype "unspecified"))
      (node (ref "U56") (pin "2") (pinfunction "COL_2") (pintype "input"))
    )
    (net (code "95") (name "Net-(D70-K)") (class "Default")
      (node (ref "D70") (pin "2") (pinfunction "K_2") (pintype "unspecified"))
      (node (ref "U77") (pin "2") (pinfunction "COL_2") (pintype "input"))
    )
    (net (code "96") (name "Net-(D71-K)") (class "Default")
      (node (ref "D71") (pin "2") (pinfunction "K_2") (pintype "unspecified"))
      (node (ref "U42") (pin "2") (pinfunction "COL_2") (pintype "input"))
    )
    (net (code "97") (name "Net-(D72-K)") (class "Default")
      (node (ref "D72") (pin "2") (pinfunction "K_2") (pintype "unspecified"))
      (node (ref "U57") (pin "2") (pinfunction "COL_2") (pintype "input"))
    )
    (net (code "98") (name "Net-(D73-K)") (class "Default")
      (node (ref "D73") (pin "2") (pinfunction "K_2") (pintype "unspecified"))
      (node (ref "U70") (pin "2") (pinfunction "COL_2") (pintype "input"))
    )
    (net (code "99") (name "Net-(D74-K)") (class "Default")
      (node (ref "D74") (pin "2") (pinfunction "K_2") (pintype "unspecified"))
      (node (ref "U78") (pin "2") (pinfunction "COL_2") (pintype "input"))
    )
    (net (code "100") (name "Net-(D75-K)") (class "Default")
      (node (ref "D75") (pin "2") (pinfunction "K_2") (pintype "unspecified"))
      (node (ref "U28") (pin "2") (pinfunction "COL_2") (pintype "input"))
    )
    (net (code "101") (name "Net-(D76-K)") (class "Default")
      (node (ref "D76") (pin "2") (pinfunction "K_2") (pintype "unspecified"))
      (node (ref "U43") (pin "2") (pinfunction "COL_2") (pintype "input"))
    )
    (net (code "102") (name "Net-(D77-K)") (class "Default")
      (node (ref "D77") (pin "2") (pinfunction "K_2") (pintype "unspecified"))
      (node (ref "U71") (pin "2") (pinfunction "COL_2") (pintype "input"))
    )
    (net (code "103") (name "Net-(D78-K)") (class "Default")
      (node (ref "D78") (pin "2") (pinfunction "K_2") (pintype "unspecified"))
      (node (ref "U79") (pin "2") (pinfunction "COL_2") (pintype "input"))
    )
    (net (code "104") (name "Net-(D79-K)") (class "Default")
      (node (ref "D79") (pin "2") (pinfunction "K_2") (pintype "unspecified"))
      (node (ref "U29") (pin "2") (pinfunction "COL_2") (pintype "input"))
    )
    (net (code "105") (name "Net-(D80-K)") (class "Default")
      (node (ref "D80") (pin "2") (pinfunction "K_2") (pintype "unspecified"))
      (node (ref "U44") (pin "2") (pinfunction "COL_2") (pintype "input"))
    )
    (net (code "106") (name "Net-(D81-K)") (class "Default")
      (node (ref "D81") (pin "2") (pinfunction "K_2") (pintype "unspecified"))
      (node (ref "U58") (pin "2") (pinfunction "COL_2") (pintype "input"))
    )
    (net (code "107") (name "Net-(D82-K)") (class "Default")
      (node (ref "D82") (pin "2") (pinfunction "K_2") (pintype "unspecified"))
      (node (ref "U81") (pin "2") (pinfunction "COL_2") (pintype "input"))
    )
    (net (code "108") (name "Net-(D83-K)") (class "Default")
      (node (ref "D83") (pin "2") (pinfunction "K_2") (pintype "unspecified"))
      (node (ref "U80") (pin "2") (pinfunction "COL_2") (pintype "input"))
    )
    (net (code "109") (name "Net-(U1-DIN)") (class "Default")
      (node (ref "R1") (pin "2") (pinfunction "2_2") (pintype "unspecified"))
      (node (ref "U1") (pin "4") (pinfunction "DIN_4") (pintype "input"))
    )
    (net (code "110") (name "Net-(U1-DOUT)") (class "Default")
      (node (ref "U1") (pin "5") (pinfunction "DOUT_5") (pintype "input"))
      (node (ref "U2") (pin "4") (pinfunction "DIN_4") (pintype "input"))
    )
    (net (code "111") (name "Net-(U2-DOUT)") (class "Default")
      (node (ref "U2") (pin "5") (pinfunction "DOUT_5") (pintype "input"))
      (node (ref "U3") (pin "4") (pinfunction "DIN_4") (pintype "input"))
    )
    (net (code "112") (name "Net-(U3-DOUT)") (class "Default")
      (node (ref "U3") (pin "5") (pinfunction "DOUT_5") (pintype "input"))
      (node (ref "U4") (pin "4") (pinfunction "DIN_4") (pintype "input"))
    )
    (net (code "113") (name "Net-(U4-DOUT)") (class "Default")
      (node (ref "U4") (pin "5") (pinfunction "DOUT_5") (pintype "input"))
      (node (ref "U5") (pin "4") (pinfunction "DIN_4") (pintype "input"))
    )
    (net (code "114") (name "Net-(U5-DOUT)") (class "Default")
      (node (ref "U5") (pin "5") (pinfunction "DOUT_5") (pintype "input"))
      (node (ref "U6") (pin "4") (pinfunction "DIN_4") (pintype "input"))
    )
    (net (code "115") (name "Net-(U6-DOUT)") (class "Default")
      (node (ref "U6") (pin "5") (pinfunction "DOUT_5") (pintype "input"))
      (node (ref "U7") (pin "4") (pinfunction "DIN_4") (pintype "input"))
    )
    (net (code "116") (name "Net-(U7-DOUT)") (class "Default")
      (node (ref "U7") (pin "5") (pinfunction "DOUT_5") (pintype "input"))
      (node (ref "U8") (pin "4") (pinfunction "DIN_4") (pintype "input"))
    )
    (net (code "117") (name "Net-(U8-DOUT)") (class "Default")
      (node (ref "U8") (pin "5") (pinfunction "DOUT_5") (pintype "input"))
      (node (ref "U9") (pin "4") (pinfunction "DIN_4") (pintype "input"))
    )
    (net (code "118") (name "Net-(U10-DIN)") (class "Default")
      (node (ref "U10") (pin "4") (pinfunction "DIN_4") (pintype "input"))
      (node (ref "U9") (pin "5") (pinfunction "DOUT_5") (pintype "input"))
    )
    (net (code "119") (name "Net-(U10-DOUT)") (class "Default")
      (node (ref "U10") (pin "5") (pinfunction "DOUT_5") (pintype "input"))
      (node (ref "U11") (pin "4") (pinfunction "DIN_4") (pintype "input"))
    )
    (net (code "120") (name "Net-(U11-DOUT)") (class "Default")
      (node (ref "U11") (pin "5") (pinfunction "DOUT_5") (pintype "input"))
      (node (ref "U12") (pin "4") (pinfunction "DIN_4") (pintype "input"))
    )
    (net (code "121") (name "Net-(U12-DOUT)") (class "Default")
      (node (ref "U12") (pin "5") (pinfunction "DOUT_5") (pintype "input"))
      (node (ref "U13") (pin "4") (pinfunction "DIN_4") (pintype "input"))
    )
    (net (code "122") (name "Net-(U13-DOUT)") (class "Default")
      (node (ref "U13") (pin "5") (pinfunction "DOUT_5") (pintype "input"))
      (node (ref "U14") (pin "4") (pinfunction "DIN_4") (pintype "input"))
    )
    (net (code "123") (name "Net-(U14-DOUT)") (class "Default")
      (node (ref "R7") (pin "1") (pinfunction "1_1") (pintype "unspecified"))
      (node (ref "U14") (pin "5") (pinfunction "DOUT_5") (pintype "input"))
    )
    (net (code "124") (name "Net-(U15-DIN)") (class "Default")
      (node (ref "R2") (pin "2") (pinfunction "2_2") (pintype "unspecified"))
      (node (ref "U15") (pin "4") (pinfunction "DIN_4") (pintype "input"))
    )
    (net (code "125") (name "Net-(U15-DOUT)") (class "Default")
      (node (ref "U15") (pin "5") (pinfunction "DOUT_5") (pintype "input"))
      (node (ref "U16") (pin "4") (pinfunction "DIN_4") (pintype "input"))
    )
    (net (code "126") (name "Net-(U16-DOUT)") (class "Default")
      (node (ref "U16") (pin "5") (pinfunction "DOUT_5") (pintype "input"))
      (node (ref "U17") (pin "4") (pinfunction "DIN_4") (pintype "input"))
    )
    (net (code "127") (name "Net-(U17-DOUT)") (class "Default")
      (node (ref "U17") (pin "5") (pinfunction "DOUT_5") (pintype "input"))
      (node (ref "U18") (pin "4") (pinfunction "DIN_4") (pintype "input"))
    )
    (net (code "128") (name "Net-(U18-DOUT)") (class "Default")
      (node (ref "U18") (pin "5") (pinfunction "DOUT_5") (pintype "input"))
      (node (ref "U19") (pin "4") (pinfunction "DIN_4") (pintype "input"))
    )
    (net (code "129") (name "Net-(U19-DOUT)") (class "Default")
      (node (ref "U19") (pin "5") (pinfunction "DOUT_5") (pintype "input"))
      (node (ref "U20") (pin "4") (pinfunction "DIN_4") (pintype "input"))
    )
    (net (code "130") (name "Net-(U20-DOUT)") (class "Default")
      (node (ref "U20") (pin "5") (pinfunction "DOUT_5") (pintype "input"))
      (node (ref "U21") (pin "4") (pinfunction "DIN_4") (pintype "input"))
    )
    (net (code "131") (name "Net-(U21-DOUT)") (class "Default")
      (node (ref "U21") (pin "5") (pinfunction "DOUT_5") (pintype "input"))
      (node (ref "U22") (pin "4") (pinfunction "DIN_4") (pintype "input"))
    )
    (net (code "132") (name "Net-(U22-DOUT)") (class "Default")
      (node (ref "U22") (pin "5") (pinfunction "DOUT_5") (pintype "input"))
      (node (ref "U23") (pin "4") (pinfunction "DIN_4") (pintype "input"))
    )
    (net (code "133") (name "Net-(U23-DOUT)") (class "Default")
      (node (ref "U23") (pin "5") (pinfunction "DOUT_5") (pintype "input"))
      (node (ref "U24") (pin "4") (pinfunction "DIN_4") (pintype "input"))
    )
    (net (code "134") (name "Net-(U24-DOUT)") (class "Default")
      (node (ref "U24") (pin "5") (pinfunction "DOUT_5") (pintype "input"))
      (node (ref "U25") (pin "4") (pinfunction "DIN_4") (pintype "input"))
    )
    (net (code "135") (name "Net-(U25-DOUT)") (class "Default")
      (node (ref "U25") (pin "5") (pinfunction "DOUT_5") (pintype "input"))
      (node (ref "U26") (pin "4") (pinfunction "DIN_4") (pintype "input"))
    )
    (net (code "136") (name "Net-(U26-DOUT)") (class "Default")
      (node (ref "U26") (pin "5") (pinfunction "DOUT_5") (pintype "input"))
      (node (ref "U27") (pin "4") (pinfunction "DIN_4") (pintype "input"))
    )
    (net (code "137") (name "Net-(U27-DOUT)") (class "Default")
      (node (ref "U27") (pin "5") (pinfunction "DOUT_5") (pintype "input"))
      (node (ref "U28") (pin "4") (pinfunction "DIN_4") (pintype "input"))
    )
    (net (code "138") (name "Net-(U28-DOUT)") (class "Default")
      (node (ref "U28") (pin "5") (pinfunction "DOUT_5") (pintype "input"))
      (node (ref "U29") (pin "4") (pinfunction "DIN_4") (pintype "input"))
    )
    (net (code "139") (name "Net-(U29-DOUT)") (class "Default")
      (node (ref "R8") (pin "1") (pinfunction "1_1") (pintype "unspecified"))
      (node (ref "U29") (pin "5") (pinfunction "DOUT_5") (pintype "input"))
    )
    (net (code "140") (name "Net-(U30-DIN)") (class "Default")
      (node (ref "R3") (pin "2") (pinfunction "2_2") (pintype "unspecified"))
      (node (ref "U30") (pin "4") (pinfunction "DIN_4") (pintype "input"))
    )
    (net (code "141") (name "Net-(U30-DOUT)") (class "Default")
      (node (ref "U30") (pin "5") (pinfunction "DOUT_5") (pintype "input"))
      (node (ref "U31") (pin "4") (pinfunction "DIN_4") (pintype "input"))
    )
    (net (code "142") (name "Net-(U31-DOUT)") (class "Default")
      (node (ref "U31") (pin "5") (pinfunction "DOUT_5") (pintype "input"))
      (node (ref "U32") (pin "4") (pinfunction "DIN_4") (pintype "input"))
    )
    (net (code "143") (name "Net-(U32-DOUT)") (class "Default")
      (node (ref "U32") (pin "5") (pinfunction "DOUT_5") (pintype "input"))
      (node (ref "U33") (pin "4") (pinfunction "DIN_4") (pintype "input"))
    )
    (net (code "144") (name "Net-(U33-DOUT)") (class "Default")
      (node (ref "U33") (pin "5") (pinfunction "DOUT_5") (pintype "input"))
      (node (ref "U34") (pin "4") (pinfunction "DIN_4") (pintype "input"))
    )
    (net (code "145") (name "Net-(U34-DOUT)") (class "Default")
      (node (ref "U34") (pin "5") (pinfunction "DOUT_5") (pintype "input"))
      (node (ref "U35") (pin "4") (pinfunction "DIN_4") (pintype "input"))
    )
    (net (code "146") (name "Net-(U35-DOUT)") (class "Default")
      (node (ref "U35") (pin "5") (pinfunction "DOUT_5") (pintype "input"))
      (node (ref "U36") (pin "4") (pinfunction "DIN_4") (pintype "input"))
    )
    (net (code "147") (name "Net-(U36-DOUT)") (class "Default")
      (node (ref "U36") (pin "5") (pinfunction "DOUT_5") (pintype "input"))
      (node (ref "U37") (pin "4") (pinfunction "DIN_4") (pintype "input"))
    )
    (net (code "148") (name "Net-(U37-DOUT)") (class "Default")
      (node (ref "U37") (pin "5") (pinfunction "DOUT_5") (pintype "input"))
      (node (ref "U38") (pin "4") (pinfunction "DIN_4") (pintype "input"))
    )
    (net (code "149") (name "Net-(U38-DOUT)") (class "Default")
      (node (ref "U38") (pin "5") (pinfunction "DOUT_5") (pintype "input"))
      (node (ref "U39") (pin "4") (pinfunction "DIN_4") (pintype "input"))
    )
    (net (code "150") (name "Net-(U39-DOUT)") (class "Default")
      (node (ref "U39") (pin "5") (pinfunction "DOUT_5") (pintype "input"))
      (node (ref "U40") (pin "4") (pinfunction "DIN_4") (pintype "input"))
    )
    (net (code "151") (name "Net-(U40-DOUT)") (class "Default")
      (node (ref "U40") (pin "5") (pinfunction "DOUT_5") (pintype "input"))
      (node (ref "U41") (pin "4") (pinfunction "DIN_4") (pintype "input"))
    )
    (net (code "152") (name "Net-(U41-DOUT)") (class "Default")
      (node (ref "U41") (pin "5") (pinfunction "DOUT_5") (pintype "input"))
      (node (ref "U42") (pin "4") (pinfunction "DIN_4") (pintype "input"))
    )
    (net (code "153") (name "Net-(U42-DOUT)") (class "Default")
      (node (ref "U42") (pin "5") (pinfunction "DOUT_5") (pintype "input"))
      (node (ref "U43") (pin "4") (pinfunction "DIN_4") (pintype "input"))
    )
    (net (code "154") (name "Net-(U43-DOUT)") (class "Default")
      (node (ref "U43") (pin "5") (pinfunction "DOUT_5") (pintype "input"))
      (node (ref "U44") (pin "4") (pinfunction "DIN_4") (pintype "input"))
    )
    (net (code "155") (name "Net-(U44-DOUT)") (class "Default")
      (node (ref "R9") (pin "1") (pinfunction "1_1") (pintype "unspecified"))
      (node (ref "U44") (pin "5") (pinfunction "DOUT_5") (pintype "input"))
    )
    (net (code "156") (name "Net-(U45-DIN)") (class "Default")
      (node (ref "R4") (pin "2") (pinfunction "2_2") (pintype "unspecified"))
      (node (ref "U45") (pin "4") (pinfunction "DIN_4") (pintype "input"))
    )
    (net (code "157") (name "Net-(U45-DOUT)") (class "Default")
      (node (ref "U45") (pin "5") (pinfunction "DOUT_5") (pintype "input"))
      (node (ref "U46") (pin "4") (pinfunction "DIN_4") (pintype "input"))
    )
    (net (code "158") (name "Net-(U46-DOUT)") (class "Default")
      (node (ref "U46") (pin "5") (pinfunction "DOUT_5") (pintype "input"))
      (node (ref "U47") (pin "4") (pinfunction "DIN_4") (pintype "input"))
    )
    (net (code "159") (name "Net-(U47-DOUT)") (class "Default")
      (node (ref "U47") (pin "5") (pinfunction "DOUT_5") (pintype "input"))
      (node (ref "U48") (pin "4") (pinfunction "DIN_4") (pintype "input"))
    )
    (net (code "160") (name "Net-(U48-DOUT)") (class "Default")
      (node (ref "U48") (pin "5") (pinfunction "DOUT_5") (pintype "input"))
      (node (ref "U49") (pin "4") (pinfunction "DIN_4") (pintype "input"))
    )
    (net (code "161") (name "Net-(U49-DOUT)") (class "Default")
      (node (ref "U49") (pin "5") (pinfunction "DOUT_5") (pintype "input"))
      (node (ref "U50") (pin "4") (pinfunction "DIN_4") (pintype "input"))
    )
    (net (code "162") (name "Net-(U50-DOUT)") (class "Default")
      (node (ref "U50") (pin "5") (pinfunction "DOUT_5") (pintype "input"))
      (node (ref "U51") (pin "4") (pinfunction "DIN_4") (pintype "input"))
    )
    (net (code "163") (name "Net-(U51-DOUT)") (class "Default")
      (node (ref "U51") (pin "5") (pinfunction "DOUT_5") (pintype "input"))
      (node (ref "U52") (pin "4") (pinfunction "DIN_4") (pintype "input"))
    )
    (net (code "164") (name "Net-(U52-DOUT)") (class "Default")
      (node (ref "U52") (pin "5") (pinfunction "DOUT_5") (pintype "input"))
      (node (ref "U53") (pin "4") (pinfunction "DIN_4") (pintype "input"))
    )
    (net (code "165") (name "Net-(U53-DOUT)") (class "Default")
      (node (ref "U53") (pin "5") (pinfunction "DOUT_5") (pintype "input"))
      (node (ref "U54") (pin "4") (pinfunction "DIN_4") (pintype "input"))
    )
    (net (code "166") (name "Net-(U54-DOUT)") (class "Default")
      (node (ref "U54") (pin "5") (pinfunction "DOUT_5") (pintype "input"))
      (node (ref "U55") (pin "4") (pinfunction "DIN_4") (pintype "input"))
    )
    (net (code "167") (name "Net-(U55-DOUT)") (class "Default")
      (node (ref "U55") (pin "5") (pinfunction "DOUT_5") (pintype "input"))
      (node (ref "U56") (pin "4") (pinfunction "DIN_4") (pintype "input"))
    )
    (net (code "168") (name "Net-(U56-DOUT)") (class "Default")
      (node (ref "U56") (pin "5") (pinfunction "DOUT_5") (pintype "input"))
      (node (ref "U57") (pin "4") (pinfunction "DIN_4") (pintype "input"))
    )
    (net (code "169") (name "Net-(U57-DOUT)") (class "Default")
      (node (ref "U57") (pin "5") (pinfunction "DOUT_5") (pintype "input"))
      (node (ref "U58") (pin "4") (pinfunction "DIN_4") (pintype "input"))
    )
    (net (code "170") (name "Net-(U58-DOUT)") (class "Default")
      (node (ref "R10") (pin "1") (pinfunction "1_1") (pintype "unspecified"))
      (node (ref "U58") (pin "5") (pinfunction "DOUT_5") (pintype "input"))
    )
    (net (code "171") (name "Net-(U59-DIN)") (class "Default")
      (node (ref "R5") (pin "2") (pinfunction "2_2") (pintype "unspecified"))
      (node (ref "U59") (pin "4") (pinfunction "DIN_4") (pintype "input"))
    )
    (net (code "172") (name "Net-(U59-DOUT)") (class "Default")
      (node (ref "U59") (pin "5") (pinfunction "DOUT_5") (pintype "input"))
      (node (ref "U60") (pin "4") (pinfunction "DIN_4") (pintype "input"))
    )
    (net (code "173") (name "Net-(U60-DOUT)") (class "Default")
      (node (ref "U60") (pin "5") (pinfunction "DOUT_5") (pintype "input"))
      (node (ref "U61") (pin "4") (pinfunction "DIN_4") (pintype "input"))
    )
    (net (code "174") (name "Net-(U61-DOUT)") (class "Default")
      (node (ref "U61") (pin "5") (pinfunction "DOUT_5") (pintype "input"))
      (node (ref "U62") (pin "4") (pinfunction "DIN_4") (pintype "input"))
    )
    (net (code "175") (name "Net-(U62-DOUT)") (class "Default")
      (node (ref "U62") (pin "5") (pinfunction "DOUT_5") (pintype "input"))
      (node (ref "U63") (pin "4") (pinfunction "DIN_4") (pintype "input"))
    )
    (net (code "176") (name "Net-(U63-DOUT)") (class "Default")
      (node (ref "U63") (pin "5") (pinfunction "DOUT_5") (pintype "input"))
      (node (ref "U64") (pin "4") (pinfunction "DIN_4") (pintype "input"))
    )
    (net (code "177") (name "Net-(U64-DOUT)") (class "Default")
      (node (ref "U64") (pin "5") (pinfunction "DOUT_5") (pintype "input"))
      (node (ref "U65") (pin "4") (pinfunction "DIN_4") (pintype "input"))
    )
    (net (code "178") (name "Net-(U65-DOUT)") (class "Default")
      (node (ref "U65") (pin "5") (pinfunction "DOUT_5") (pintype "input"))
      (node (ref "U66") (pin "4") (pinfunction "DIN_4") (pintype "input"))
    )
    (net (code "179") (name "Net-(U66-DOUT)") (class "Default")
      (node (ref "U66") (pin "5") (pinfunction "DOUT_5") (pintype "input"))
      (node (ref "U67") (pin "4") (pinfunction "DIN_4") (pintype "input"))
    )
    (net (code "180") (name "Net-(U67-DOUT)") (class "Default")
      (node (ref "U67") (pin "5") (pinfunction "DOUT_5") (pintype "input"))
      (node (ref "U68") (pin "4") (pinfunction "DIN_4") (pintype "input"))
    )
    (net (code "181") (name "Net-(U68-DOUT)") (class "Default")
      (node (ref "U68") (pin "5") (pinfunction "DOUT_5") (pintype "input"))
      (node (ref "U69") (pin "4") (pinfunction "DIN_4") (pintype "input"))
    )
    (net (code "182") (name "Net-(U69-DOUT)") (class "Default")
      (node (ref "U69") (pin "5") (pinfunction "DOUT_5") (pintype "input"))
      (node (ref "U70") (pin "4") (pinfunction "DIN_4") (pintype "input"))
    )
    (net (code "183") (name "Net-(U70-DOUT)") (class "Default")
      (node (ref "U70") (pin "5") (pinfunction "DOUT_5") (pintype "input"))
      (node (ref "U71") (pin "4") (pinfunction "DIN_4") (pintype "input"))
    )
    (net (code "184") (name "Net-(U71-DOUT)") (class "Default")
      (node (ref "U71") (pin "5") (pinfunction "DOUT_5") (pintype "input"))
      (node (ref "U81") (pin "4") (pinfunction "DIN_4") (pintype "input"))
    )
    (net (code "185") (name "Net-(U72-DIN)") (class "Default")
      (node (ref "R6") (pin "2") (pinfunction "2_2") (pintype "unspecified"))
      (node (ref "U72") (pin "4") (pinfunction "DIN_4") (pintype "input"))
    )
    (net (code "186") (name "Net-(U72-DOUT)") (class "Default")
      (node (ref "U72") (pin "5") (pinfunction "DOUT_5") (pintype "input"))
      (node (ref "U73") (pin "4") (pinfunction "DIN_4") (pintype "input"))
    )
    (net (code "187") (name "Net-(U73-DOUT)") (class "Default")
      (node (ref "U73") (pin "5") (pinfunction "DOUT_5") (pintype "input"))
      (node (ref "U74") (pin "4") (pinfunction "DIN_4") (pintype "input"))
    )
    (net (code "188") (name "Net-(U74-DOUT)") (class "Default")
      (node (ref "U74") (pin "5") (pinfunction "DOUT_5") (pintype "input"))
      (node (ref "U75") (pin "4") (pinfunction "DIN_4") (pintype "input"))
    )
    (net (code "189") (name "Net-(U75-DOUT)") (class "Default")
      (node (ref "U75") (pin "5") (pinfunction "DOUT_5") (pintype "input"))
      (node (ref "U76") (pin "4") (pinfunction "DIN_4") (pintype "input"))
    )
    (net (code "190") (name "Net-(U76-DOUT)") (class "Default")
      (node (ref "U76") (pin "5") (pinfunction "DOUT_5") (pintype "input"))
      (node (ref "U82") (pin "4") (pinfunction "DIN_4") (pintype "input"))
    )
    (net (code "191") (name "Net-(U77-DIN)") (class "Default")
      (node (ref "U77") (pin "4") (pinfunction "DIN_4") (pintype "input"))
      (node (ref "U82") (pin "5") (pinfunction "DOUT_5") (pintype "input"))
    )
    (net (code "192") (name "Net-(U77-DOUT)") (class "Default")
      (node (ref "U77") (pin "5") (pinfunction "DOUT_5") (pintype "input"))
      (node (ref "U78") (pin "4") (pinfunction "DIN_4") (pintype "input"))
    )
    (net (code "193") (name "Net-(U78-DOUT)") (class "Default")
      (node (ref "U78") (pin "5") (pinfunction "DOUT_5") (pintype "input"))
      (node (ref "U79") (pin "4") (pinfunction "DIN_4") (pintype "input"))
    )
    (net (code "194") (name "Net-(U79-DOUT)") (class "Default")
      (node (ref "U79") (pin "5") (pinfunction "DOUT_5") (pintype "input"))
      (node (ref "U80") (pin "4") (pinfunction "DIN_4") (pintype "input"))
    )
    (net (code "195") (name "Net-(U80-DOUT)") (class "Default")
      (node (ref "R12") (pin "1") (pinfunction "1_1") (pintype "unspecified"))
      (node (ref "U80") (pin "5") (pinfunction "DOUT_5") (pintype "input"))
    )
    (net (code "196") (name "Net-(U81-DOUT)") (class "Default")
      (node (ref "R11") (pin "1") (pinfunction "1_1") (pintype "unspecified"))
      (node (ref "U81") (pin "5") (pinfunction "DOUT_5") (pintype "input"))
    )
    (net (code "197") (name "OSC_IN_1") (class "Default")
      (node (ref "C93") (pin "2") (pinfunction "2_2") (pintype "input"))
      (node (ref "U83") (pin "5") (pinfunction "PD0-OSC_IN_5") (pintype "unspecified"))
      (node (ref "X1") (pin "3") (pinfunction "3_3") (pintype "input"))
    )
    (net (code "198") (name "OSC_IN_2") (class "Default")
      (node (ref "C97") (pin "2") (pinfunction "2_2") (pintype "input"))
      (node (ref "U86") (pin "5") (pinfunction "PD0-OSC_IN_5") (pintype "unspecified"))
      (node (ref "X2") (pin "3") (pinfunction "3_3") (pintype "input"))
    )
    (net (code "199") (name "OSC_OUT_1") (class "Default")
      (node (ref "C94") (pin "2") (pinfunction "2_2") (pintype "input"))
      (node (ref "U83") (pin "6") (pinfunction "PD1-OSC_OUT_6") (pintype "unspecified"))
      (node (ref "X1") (pin "1") (pinfunction "1_1") (pintype "input"))
    )
    (net (code "200") (name "OSC_OUT_2") (class "Default")
      (node (ref "C98") (pin "2") (pinfunction "2_2") (pintype "input"))
      (node (ref "U86") (pin "6") (pinfunction "PD1-OSC_OUT_6") (pintype "unspecified"))
      (node (ref "X2") (pin "1") (pinfunction "1_1") (pintype "input"))
    )
    (net (code "201") (name "PA11") (class "Default")
      (node (ref "R15") (pin "2") (pinfunction "2_2") (pintype "unspecified"))
      (node (ref "U83") (pin "44") (pinfunction "PA11_44") (pintype "unspecified"))
    )
    (net (code "202") (name "PA12") (class "Default")
      (node (ref "R16") (pin "2") (pinfunction "2_2") (pintype "unspecified"))
      (node (ref "R17") (pin "1") (pinfunction "1_1") (pintype "unspecified"))
      (node (ref "U83") (pin "45") (pinfunction "PA12_45") (pintype "unspecified"))
    )
    (net (code "203") (name "RGB1") (class "Default")
      (node (ref "R1") (pin "1") (pinfunction "1_1") (pintype "unspecified"))
      (node (ref "U86") (pin "10") (pinfunction "PA0-WKUP_10") (pintype "unspecified"))
    )
    (net (code "204") (name "RGB2") (class "Default")
      (node (ref "R2") (pin "1") (pinfunction "1_1") (pintype "unspecified"))
      (node (ref "U86") (pin "11") (pinfunction "PA1_11") (pintype "unspecified"))
    )
    (net (code "205") (name "RGB3") (class "Default")
      (node (ref "R3") (pin "1") (pinfunction "1_1") (pintype "unspecified"))
      (node (ref "U86") (pin "16") (pinfunction "PA6_16") (pintype "unspecified"))
    )
    (net (code "206") (name "RGB4") (class "Default")
      (node (ref "R4") (pin "1") (pinfunction "1_1") (pintype "unspecified"))
      (node (ref "U86") (pin "18") (pinfunction "PB0_18") (pintype "unspecified"))
    )
    (net (code "207") (name "RGB5") (class "Default")
      (node (ref "R5") (pin "1") (pinfunction "1_1") (pintype "unspecified"))
      (node (ref "U86") (pin "19") (pinfunction "PB1_19") (pintype "unspecified"))
    )
    (net (code "208") (name "RGB6") (class "Default")
      (node (ref "R6") (pin "1") (pinfunction "1_1") (pintype "unspecified"))
      (node (ref "U86") (pin "21") (pinfunction "PB10_21") (pintype "unspecified"))
    )
    (net (code "209") (name "ROW1") (class "Default")
      (node (ref "U1") (pin "1") (pinfunction "ROW_1") (pintype "input"))
      (node (ref "U10") (pin "1") (pinfunction "ROW_1") (pintype "input"))
      (node (ref "U11") (pin "1") (pinfunction "ROW_1") (pintype "input"))
      (node (ref "U12") (pin "1") (pinfunction "ROW_1") (pintype "input"))
      (node (ref "U13") (pin "1") (pinfunction "ROW_1") (pintype "input"))
      (node (ref "U14") (pin "1") (pinfunction "ROW_1") (pintype "input"))
      (node (ref "U2") (pin "1") (pinfunction "ROW_1") (pintype "input"))
      (node (ref "U3") (pin "1") (pinfunction "ROW_1") (pintype "input"))
      (node (ref "U4") (pin "1") (pinfunction "ROW_1") (pintype "input"))
      (node (ref "U5") (pin "1") (pinfunction "ROW_1") (pintype "input"))
      (node (ref "U6") (pin "1") (pinfunction "ROW_1") (pintype "input"))
      (node (ref "U7") (pin "1") (pinfunction "ROW_1") (pintype "input"))
      (node (ref "U8") (pin "1") (pinfunction "ROW_1") (pintype "input"))
      (node (ref "U83") (pin "26") (pinfunction "PB0_26") (pintype "unspecified"))
      (node (ref "U9") (pin "1") (pinfunction "ROW_1") (pintype "input"))
    )
    (net (code "210") (name "ROW2") (class "Default")
      (node (ref "U15") (pin "1") (pinfunction "ROW_1") (pintype "input"))
      (node (ref "U16") (pin "1") (pinfunction "ROW_1") (pintype "input"))
      (node (ref "U17") (pin "1") (pinfunction "ROW_1") (pintype "input"))
      (node (ref "U18") (pin "1") (pinfunction "ROW_1") (pintype "input"))
      (node (ref "U19") (pin "1") (pinfunction "ROW_1") (pintype "input"))
      (node (ref "U20") (pin "1") (pinfunction "ROW_1") (pintype "input"))
      (node (ref "U21") (pin "1") (pinfunction "ROW_1") (pintype "input"))
      (node (ref "U22") (pin "1") (pinfunction "ROW_1") (pintype "input"))
      (node (ref "U23") (pin "1") (pinfunction "ROW_1") (pintype "input"))
      (node (ref "U24") (pin "1") (pinfunction "ROW_1") (pintype "input"))
      (node (ref "U25") (pin "1") (pinfunction "ROW_1") (pintype "input"))
      (node (ref "U26") (pin "1") (pinfunction "ROW_1") (pintype "input"))
      (node (ref "U27") (pin "1") (pinfunction "ROW_1") (pintype "input"))
      (node (ref "U28") (pin "1") (pinfunction "ROW_1") (pintype "input"))
      (node (ref "U29") (pin "1") (pinfunction "ROW_1") (pintype "input"))
      (node (ref "U83") (pin "27") (pinfunction "PB1_27") (pintype "unspecified"))
    )
    (net (code "211") (name "ROW3") (class "Default")
      (node (ref "U30") (pin "1") (pinfunction "ROW_1") (pintype "input"))
      (node (ref "U31") (pin "1") (pinfunction "ROW_1") (pintype "input"))
      (node (ref "U32") (pin "1") (pinfunction "ROW_1") (pintype "input"))
      (node (ref "U33") (pin "1") (pinfunction "ROW_1") (pintype "input"))
      (node (ref "U34") (pin "1") (pinfunction "ROW_1") (pintype "input"))
      (node (ref "U35") (pin "1") (pinfunction "ROW_1") (pintype "input"))
      (node (ref "U36") (pin "1") (pinfunction "ROW_1") (pintype "input"))
      (node (ref "U37") (pin "1") (pinfunction "ROW_1") (pintype "input"))
      (node (ref "U38") (pin "1") (pinfunction "ROW_1") (pintype "input"))
      (node (ref "U39") (pin "1") (pinfunction "ROW_1") (pintype "input"))
      (node (ref "U40") (pin "1") (pinfunction "ROW_1") (pintype "input"))
      (node (ref "U41") (pin "1") (pinfunction "ROW_1") (pintype "input"))
      (node (ref "U42") (pin "1") (pinfunction "ROW_1") (pintype "input"))
      (node (ref "U43") (pin "1") (pinfunction "ROW_1") (pintype "input"))
      (node (ref "U44") (pin "1") (pinfunction "ROW_1") (pintype "input"))
      (node (ref "U83") (pin "57") (pinfunction "PB5_57") (pintype "unspecified"))
    )
    (net (code "212") (name "ROW4") (class "Default")
      (node (ref "U45") (pin "1") (pinfunction "ROW_1") (pintype "input"))
      (node (ref "U46") (pin "1") (pinfunction "ROW_1") (pintype "input"))
      (node (ref "U47") (pin "1") (pinfunction "ROW_1") (pintype "input"))
      (node (ref "U48") (pin "1") (pinfunction "ROW_1") (pintype "input"))
      (node (ref "U49") (pin "1") (pinfunction "ROW_1") (pintype "input"))
      (node (ref "U50") (pin "1") (pinfunction "ROW_1") (pintype "input"))
      (node (ref "U51") (pin "1") (pinfunction "ROW_1") (pintype "input"))
      (node (ref "U52") (pin "1") (pinfunction "ROW_1") (pintype "input"))
      (node (ref "U53") (pin "1") (pinfunction "ROW_1") (pintype "input"))
      (node (ref "U54") (pin "1") (pinfunction "ROW_1") (pintype "input"))
      (node (ref "U55") (pin "1") (pinfunction "ROW_1") (pintype "input"))
      (node (ref "U56") (pin "1") (pinfunction "ROW_1") (pintype "input"))
      (node (ref "U57") (pin "1") (pinfunction "ROW_1") (pintype "input"))
      (node (ref "U58") (pin "1") (pinfunction "ROW_1") (pintype "input"))
      (node (ref "U83") (pin "58") (pinfunction "PB6_58") (pintype "unspecified"))
    )
    (net (code "213") (name "ROW5") (class "Default")
      (node (ref "U59") (pin "1") (pinfunction "ROW_1") (pintype "input"))
      (node (ref "U60") (pin "1") (pinfunction "ROW_1") (pintype "input"))
      (node (ref "U61") (pin "1") (pinfunction "ROW_1") (pintype "input"))
      (node (ref "U62") (pin "1") (pinfunction "ROW_1") (pintype "input"))
      (node (ref "U63") (pin "1") (pinfunction "ROW_1") (pintype "input"))
      (node (ref "U64") (pin "1") (pinfunction "ROW_1") (pintype "input"))
      (node (ref "U65") (pin "1") (pinfunction "ROW_1") (pintype "input"))
      (node (ref "U66") (pin "1") (pinfunction "ROW_1") (pintype "input"))
      (node (ref "U67") (pin "1") (pinfunction "ROW_1") (pintype "input"))
      (node (ref "U68") (pin "1") (pinfunction "ROW_1") (pintype "input"))
      (node (ref "U69") (pin "1") (pinfunction "ROW_1") (pintype "input"))
      (node (ref "U70") (pin "1") (pinfunction "ROW_1") (pintype "input"))
      (node (ref "U71") (pin "1") (pinfunction "ROW_1") (pintype "input"))
      (node (ref "U81") (pin "1") (pinfunction "ROW_1") (pintype "input"))
      (node (ref "U83") (pin "59") (pinfunction "PB7_59") (pintype "unspecified"))
    )
    (net (code "214") (name "ROW6") (class "Default")
      (node (ref "U72") (pin "1") (pinfunction "ROW_1") (pintype "input"))
      (node (ref "U73") (pin "1") (pinfunction "ROW_1") (pintype "input"))
      (node (ref "U74") (pin "1") (pinfunction "ROW_1") (pintype "input"))
      (node (ref "U75") (pin "1") (pinfunction "ROW_1") (pintype "input"))
      (node (ref "U76") (pin "1") (pinfunction "ROW_1") (pintype "input"))
      (node (ref "U77") (pin "1") (pinfunction "ROW_1") (pintype "input"))
      (node (ref "U78") (pin "1") (pinfunction "ROW_1") (pintype "input"))
      (node (ref "U79") (pin "1") (pinfunction "ROW_1") (pintype "input"))
      (node (ref "U80") (pin "1") (pinfunction "ROW_1") (pintype "input"))
      (node (ref "U82") (pin "1") (pinfunction "ROW_1") (pintype "input"))
      (node (ref "U83") (pin "61") (pinfunction "PB8_61") (pintype "unspecified"))
    )
    (net (code "215") (name "RX") (class "Default")
      (node (ref "U83") (pin "43") (pinfunction "PA10_43") (pintype "unspecified"))
      (node (ref "U86") (pin "12") (pinfunction "PA2_12") (pintype "unspecified"))
    )
    (net (code "216") (name "SWCLK_1") (class "Default")
      (node (ref "FPC1") (pin "4") (pinfunction "4_4") (pintype "unspecified"))
      (node (ref "U83") (pin "49") (pinfunction "PA14_49") (pintype "unspecified"))
    )
    (net (code "217") (name "SWCLK_2") (class "Default")
      (node (ref "FPC2") (pin "4") (pinfunction "4_4") (pintype "unspecified"))
      (node (ref "U86") (pin "37") (pinfunction "PA14_37") (pintype "unspecified"))
    )
    (net (code "218") (name "SWDIO_1") (class "Default")
      (node (ref "FPC1") (pin "2") (pinfunction "2_2") (pintype "unspecified"))
      (node (ref "U83") (pin "46") (pinfunction "PA13_46") (pintype "unspecified"))
    )
    (net (code "219") (name "SWDIO_2") (class "Default")
      (node (ref "FPC2") (pin "2") (pinfunction "2_2") (pintype "unspecified"))
      (node (ref "U86") (pin "34") (pinfunction "PA13_34") (pintype "unspecified"))
    )
    (net (code "220") (name "TX") (class "Default")
      (node (ref "U83") (pin "42") (pinfunction "PA9_42") (pintype "unspecified"))
      (node (ref "U86") (pin "13") (pinfunction "PA3_13") (pintype "unspecified"))
    )
    (net (code "221") (name "unconnected-(FPC1-Pad5)") (class "Default")
      (node (ref "FPC1") (pin "5") (pinfunction "5_5") (pintype "unspecified+no_connect"))
    )
    (net (code "222") (name "unconnected-(FPC1-Pad6)") (class "Default")
      (node (ref "FPC1") (pin "6") (pinfunction "6_6") (pintype "unspecified+no_connect"))
    )
    (net (code "223") (name "unconnected-(FPC2-Pad5)") (class "Default")
      (node (ref "FPC2") (pin "5") (pinfunction "5_5") (pintype "unspecified+no_connect"))
    )
    (net (code "224") (name "unconnected-(FPC2-Pad6)") (class "Default")
      (node (ref "FPC2") (pin "6") (pinfunction "6_6") (pintype "unspecified+no_connect"))
    )
    (net (code "225") (name "unconnected-(U83-PA8-Pad41)") (class "Default")
      (node (ref "U83") (pin "41") (pinfunction "PA8_41") (pintype "unspecified+no_connect"))
    )
    (net (code "226") (name "unconnected-(U83-PA15-Pad50)") (class "Default")
      (node (ref "U83") (pin "50") (pinfunction "PA15_50") (pintype "unspecified+no_connect"))
    )
    (net (code "227") (name "unconnected-(U83-PB3-Pad55)") (class "Default")
      (node (ref "U83") (pin "55") (pinfunction "PB3_55") (pintype "unspecified+no_connect"))
    )
    (net (code "228") (name "unconnected-(U83-PB4-Pad56)") (class "Default")
      (node (ref "U83") (pin "56") (pinfunction "PB4_56") (pintype "unspecified+no_connect"))
    )
    (net (code "229") (name "unconnected-(U83-PB9-Pad62)") (class "Default")
      (node (ref "U83") (pin "62") (pinfunction "PB9_62") (pintype "unspecified+no_connect"))
    )
    (net (code "230") (name "unconnected-(U83-PB10-Pad29)") (class "Default")
      (node (ref "U83") (pin "29") (pinfunction "PB10_29") (pintype "unspecified+no_connect"))
    )
    (net (code "231") (name "unconnected-(U83-PB11-Pad30)") (class "Default")
      (node (ref "U83") (pin "30") (pinfunction "PB11_30") (pintype "unspecified+no_connect"))
    )
    (net (code "232") (name "unconnected-(U83-PB12-Pad33)") (class "Default")
      (node (ref "U83") (pin "33") (pinfunction "PB12_33") (pintype "unspecified+no_connect"))
    )
    (net (code "233") (name "unconnected-(U83-PC0-Pad8)") (class "Default")
      (node (ref "U83") (pin "8") (pinfunction "PC0_8") (pintype "unspecified+no_connect"))
    )
    (net (code "234") (name "unconnected-(U83-PC1-Pad9)") (class "Default")
      (node (ref "U83") (pin "9") (pinfunction "PC1_9") (pintype "unspecified+no_connect"))
    )
    (net (code "235") (name "unconnected-(U83-PC2-Pad10)") (class "Default")
      (node (ref "U83") (pin "10") (pinfunction "PC2_10") (pintype "unspecified+no_connect"))
    )
    (net (code "236") (name "unconnected-(U83-PC3-Pad11)") (class "Default")
      (node (ref "U83") (pin "11") (pinfunction "PC3_11") (pintype "unspecified+no_connect"))
    )
    (net (code "237") (name "unconnected-(U83-PC4-Pad24)") (class "Default")
      (node (ref "U83") (pin "24") (pinfunction "PC4_24") (pintype "unspecified+no_connect"))
    )
    (net (code "238") (name "unconnected-(U83-PC5-Pad25)") (class "Default")
      (node (ref "U83") (pin "25") (pinfunction "PC5_25") (pintype "unspecified+no_connect"))
    )
    (net (code "239") (name "unconnected-(U83-PC6-Pad37)") (class "Default")
      (node (ref "U83") (pin "37") (pinfunction "PC6_37") (pintype "unspecified+no_connect"))
    )
    (net (code "240") (name "unconnected-(U83-PC7-Pad38)") (class "Default")
      (node (ref "U83") (pin "38") (pinfunction "PC7_38") (pintype "unspecified+no_connect"))
    )
    (net (code "241") (name "unconnected-(U83-PC13-TAMPER-RTC-Pad2)") (class "Default")
      (node (ref "U83") (pin "2") (pinfunction "PC13-TAMPER-RTC_2") (pintype "unspecified+no_connect"))
    )
    (net (code "242") (name "unconnected-(U83-PC14-OSC32_IN-Pad3)") (class "Default")
      (node (ref "U83") (pin "3") (pinfunction "PC14-OSC32_IN_3") (pintype "unspecified+no_connect"))
    )
    (net (code "243") (name "unconnected-(U83-PC15-OSC32_OUT-Pad4)") (class "Default")
      (node (ref "U83") (pin "4") (pinfunction "PC15-OSC32_OUT_4") (pintype "unspecified+no_connect"))
    )
    (net (code "244") (name "unconnected-(U83-PD2-Pad54)") (class "Default")
      (node (ref "U83") (pin "54") (pinfunction "PD2_54") (pintype "unspecified+no_connect"))
    )
    (net (code "245") (name "unconnected-(U83-VBAT-Pad1)") (class "Default")
      (node (ref "U83") (pin "1") (pinfunction "VBAT_1") (pintype "unspecified+no_connect"))
    )
    (net (code "246") (name "unconnected-(U86-PA4-Pad14)") (class "Default")
      (node (ref "U86") (pin "14") (pinfunction "PA4_14") (pintype "unspecified+no_connect"))
    )
    (net (code "247") (name "unconnected-(U86-PA5-Pad15)") (class "Default")
      (node (ref "U86") (pin "15") (pinfunction "PA5_15") (pintype "unspecified+no_connect"))
    )
    (net (code "248") (name "unconnected-(U86-PA7-Pad17)") (class "Default")
      (node (ref "U86") (pin "17") (pinfunction "PA7_17") (pintype "unspecified+no_connect"))
    )
    (net (code "249") (name "unconnected-(U86-PA8-Pad29)") (class "Default")
      (node (ref "U86") (pin "29") (pinfunction "PA8_29") (pintype "unspecified+no_connect"))
    )
    (net (code "250") (name "unconnected-(U86-PA9-Pad30)") (class "Default")
      (node (ref "U86") (pin "30") (pinfunction "PA9_30") (pintype "unspecified+no_connect"))
    )
    (net (code "251") (name "unconnected-(U86-PA10-Pad31)") (class "Default")
      (node (ref "U86") (pin "31") (pinfunction "PA10_31") (pintype "unspecified+no_connect"))
    )
    (net (code "252") (name "unconnected-(U86-PA11-Pad32)") (class "Default")
      (node (ref "U86") (pin "32") (pinfunction "PA11_32") (pintype "unspecified+no_connect"))
    )
    (net (code "253") (name "unconnected-(U86-PA12-Pad33)") (class "Default")
      (node (ref "U86") (pin "33") (pinfunction "PA12_33") (pintype "unspecified+no_connect"))
    )
    (net (code "254") (name "unconnected-(U86-PA15-Pad38)") (class "Default")
      (node (ref "U86") (pin "38") (pinfunction "PA15_38") (pintype "unspecified+no_connect"))
    )
    (net (code "255") (name "unconnected-(U86-PB3-Pad39)") (class "Default")
      (node (ref "U86") (pin "39") (pinfunction "PB3_39") (pintype "unspecified+no_connect"))
    )
    (net (code "256") (name "unconnected-(U86-PB4-Pad40)") (class "Default")
      (node (ref "U86") (pin "40") (pinfunction "PB4_40") (pintype "unspecified+no_connect"))
    )
    (net (code "257") (name "unconnected-(U86-PB5-Pad41)") (class "Default")
      (node (ref "U86") (pin "41") (pinfunction "PB5_41") (pintype "unspecified+no_connect"))
    )
    (net (code "258") (name "unconnected-(U86-PB6-Pad42)") (class "Default")
      (node (ref "U86") (pin "42") (pinfunction "PB6_42") (pintype "unspecified+no_connect"))
    )
    (net (code "259") (name "unconnected-(U86-PB7-Pad43)") (class "Default")
      (node (ref "U86") (pin "43") (pinfunction "PB7_43") (pintype "unspecified+no_connect"))
    )
    (net (code "260") (name "unconnected-(U86-PB8-Pad45)") (class "Default")
      (node (ref "U86") (pin "45") (pinfunction "PB8_45") (pintype "unspecified+no_connect"))
    )
    (net (code "261") (name "unconnected-(U86-PB9-Pad46)") (class "Default")
      (node (ref "U86") (pin "46") (pinfunction "PB9_46") (pintype "unspecified+no_connect"))
    )
    (net (code "262") (name "unconnected-(U86-PB11-Pad22)") (class "Default")
      (node (ref "U86") (pin "22") (pinfunction "PB11_22") (pintype "unspecified+no_connect"))
    )
    (net (code "263") (name "unconnected-(U86-PB12-Pad25)") (class "Default")
      (node (ref "U86") (pin "25") (pinfunction "PB12_25") (pintype "unspecified+no_connect"))
    )
    (net (code "264") (name "unconnected-(U86-PB13-Pad26)") (class "Default")
      (node (ref "U86") (pin "26") (pinfunction "PB13_26") (pintype "unspecified+no_connect"))
    )
    (net (code "265") (name "unconnected-(U86-PB14-Pad27)") (class "Default")
      (node (ref "U86") (pin "27") (pinfunction "PB14_27") (pintype "unspecified+no_connect"))
    )
    (net (code "266") (name "unconnected-(U86-PB15-Pad28)") (class "Default")
      (node (ref "U86") (pin "28") (pinfunction "PB15_28") (pintype "unspecified+no_connect"))
    )
    (net (code "267") (name "unconnected-(U86-PC13-TAMPER-RTC-Pad2)") (class "Default")
      (node (ref "U86") (pin "2") (pinfunction "PC13-TAMPER-RTC_2") (pintype "unspecified+no_connect"))
    )
    (net (code "268") (name "unconnected-(U86-PC14-OSC32_IN-Pad3)") (class "Default")
      (node (ref "U86") (pin "3") (pinfunction "PC14-OSC32_IN_3") (pintype "unspecified+no_connect"))
    )
    (net (code "269") (name "unconnected-(U86-PC15-OSC32_OUT-Pad4)") (class "Default")
      (node (ref "U86") (pin "4") (pinfunction "PC15-OSC32_OUT_4") (pintype "unspecified+no_connect"))
    )
    (net (code "270") (name "unconnected-(U86-VBAT-Pad1)") (class "Default")
      (node (ref "U86") (pin "1") (pinfunction "VBAT_1") (pintype "unspecified+no_connect"))
    )
    (net (code "271") (name "unconnected-(USB1-CC1-Pad4)") (class "Default")
      (node (ref "USB1") (pin "4") (pinfunction "CC1_4") (pintype "unspecified+no_connect"))
    )
    (net (code "272") (name "unconnected-(USB1-CC2-Pad10)") (class "Default")
      (node (ref "USB1") (pin "10") (pinfunction "CC2_10") (pintype "unspecified+no_connect"))
    )
    (net (code "273") (name "unconnected-(USB1-SBU1-Pad9)") (class "Default")
      (node (ref "USB1") (pin "9") (pinfunction "SBU1_9") (pintype "unspecified+no_connect"))
    )
    (net (code "274") (name "unconnected-(USB1-SBU2-Pad3)") (class "Default")
      (node (ref "USB1") (pin "3") (pinfunction "SBU2_3") (pintype "unspecified+no_connect"))
    )
    (net (code "275") (name "unconnected-(USB1-SHELL-Pad13)") (class "Default")
      (node (ref "USB1") (pin "13") (pinfunction "SHELL_13") (pintype "unspecified+no_connect"))
    )
    (net (code "276") (name "unconnected-(USB1-SHELL-Pad14)") (class "Default")
      (node (ref "USB1") (pin "14") (pinfunction "SHELL_14") (pintype "unspecified+no_connect"))
    )
  )
)
